# serv_open8_rohm.net
KiCad netlist of a schematic drawn in EAGLE
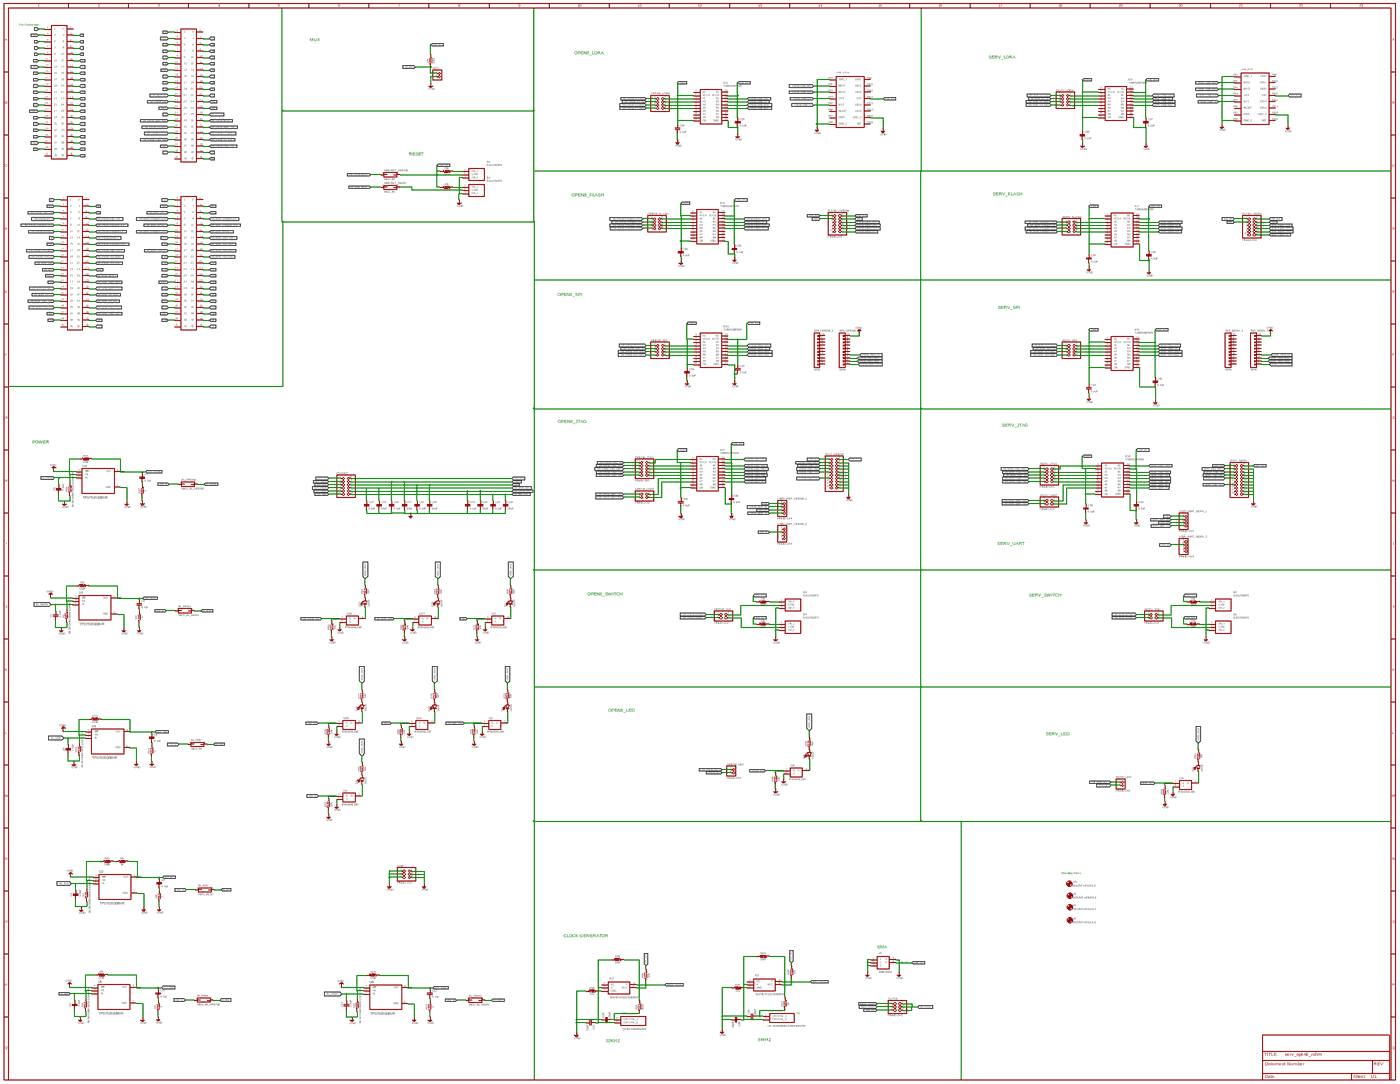
[diagram p0: schematic, sheet 1, overview]
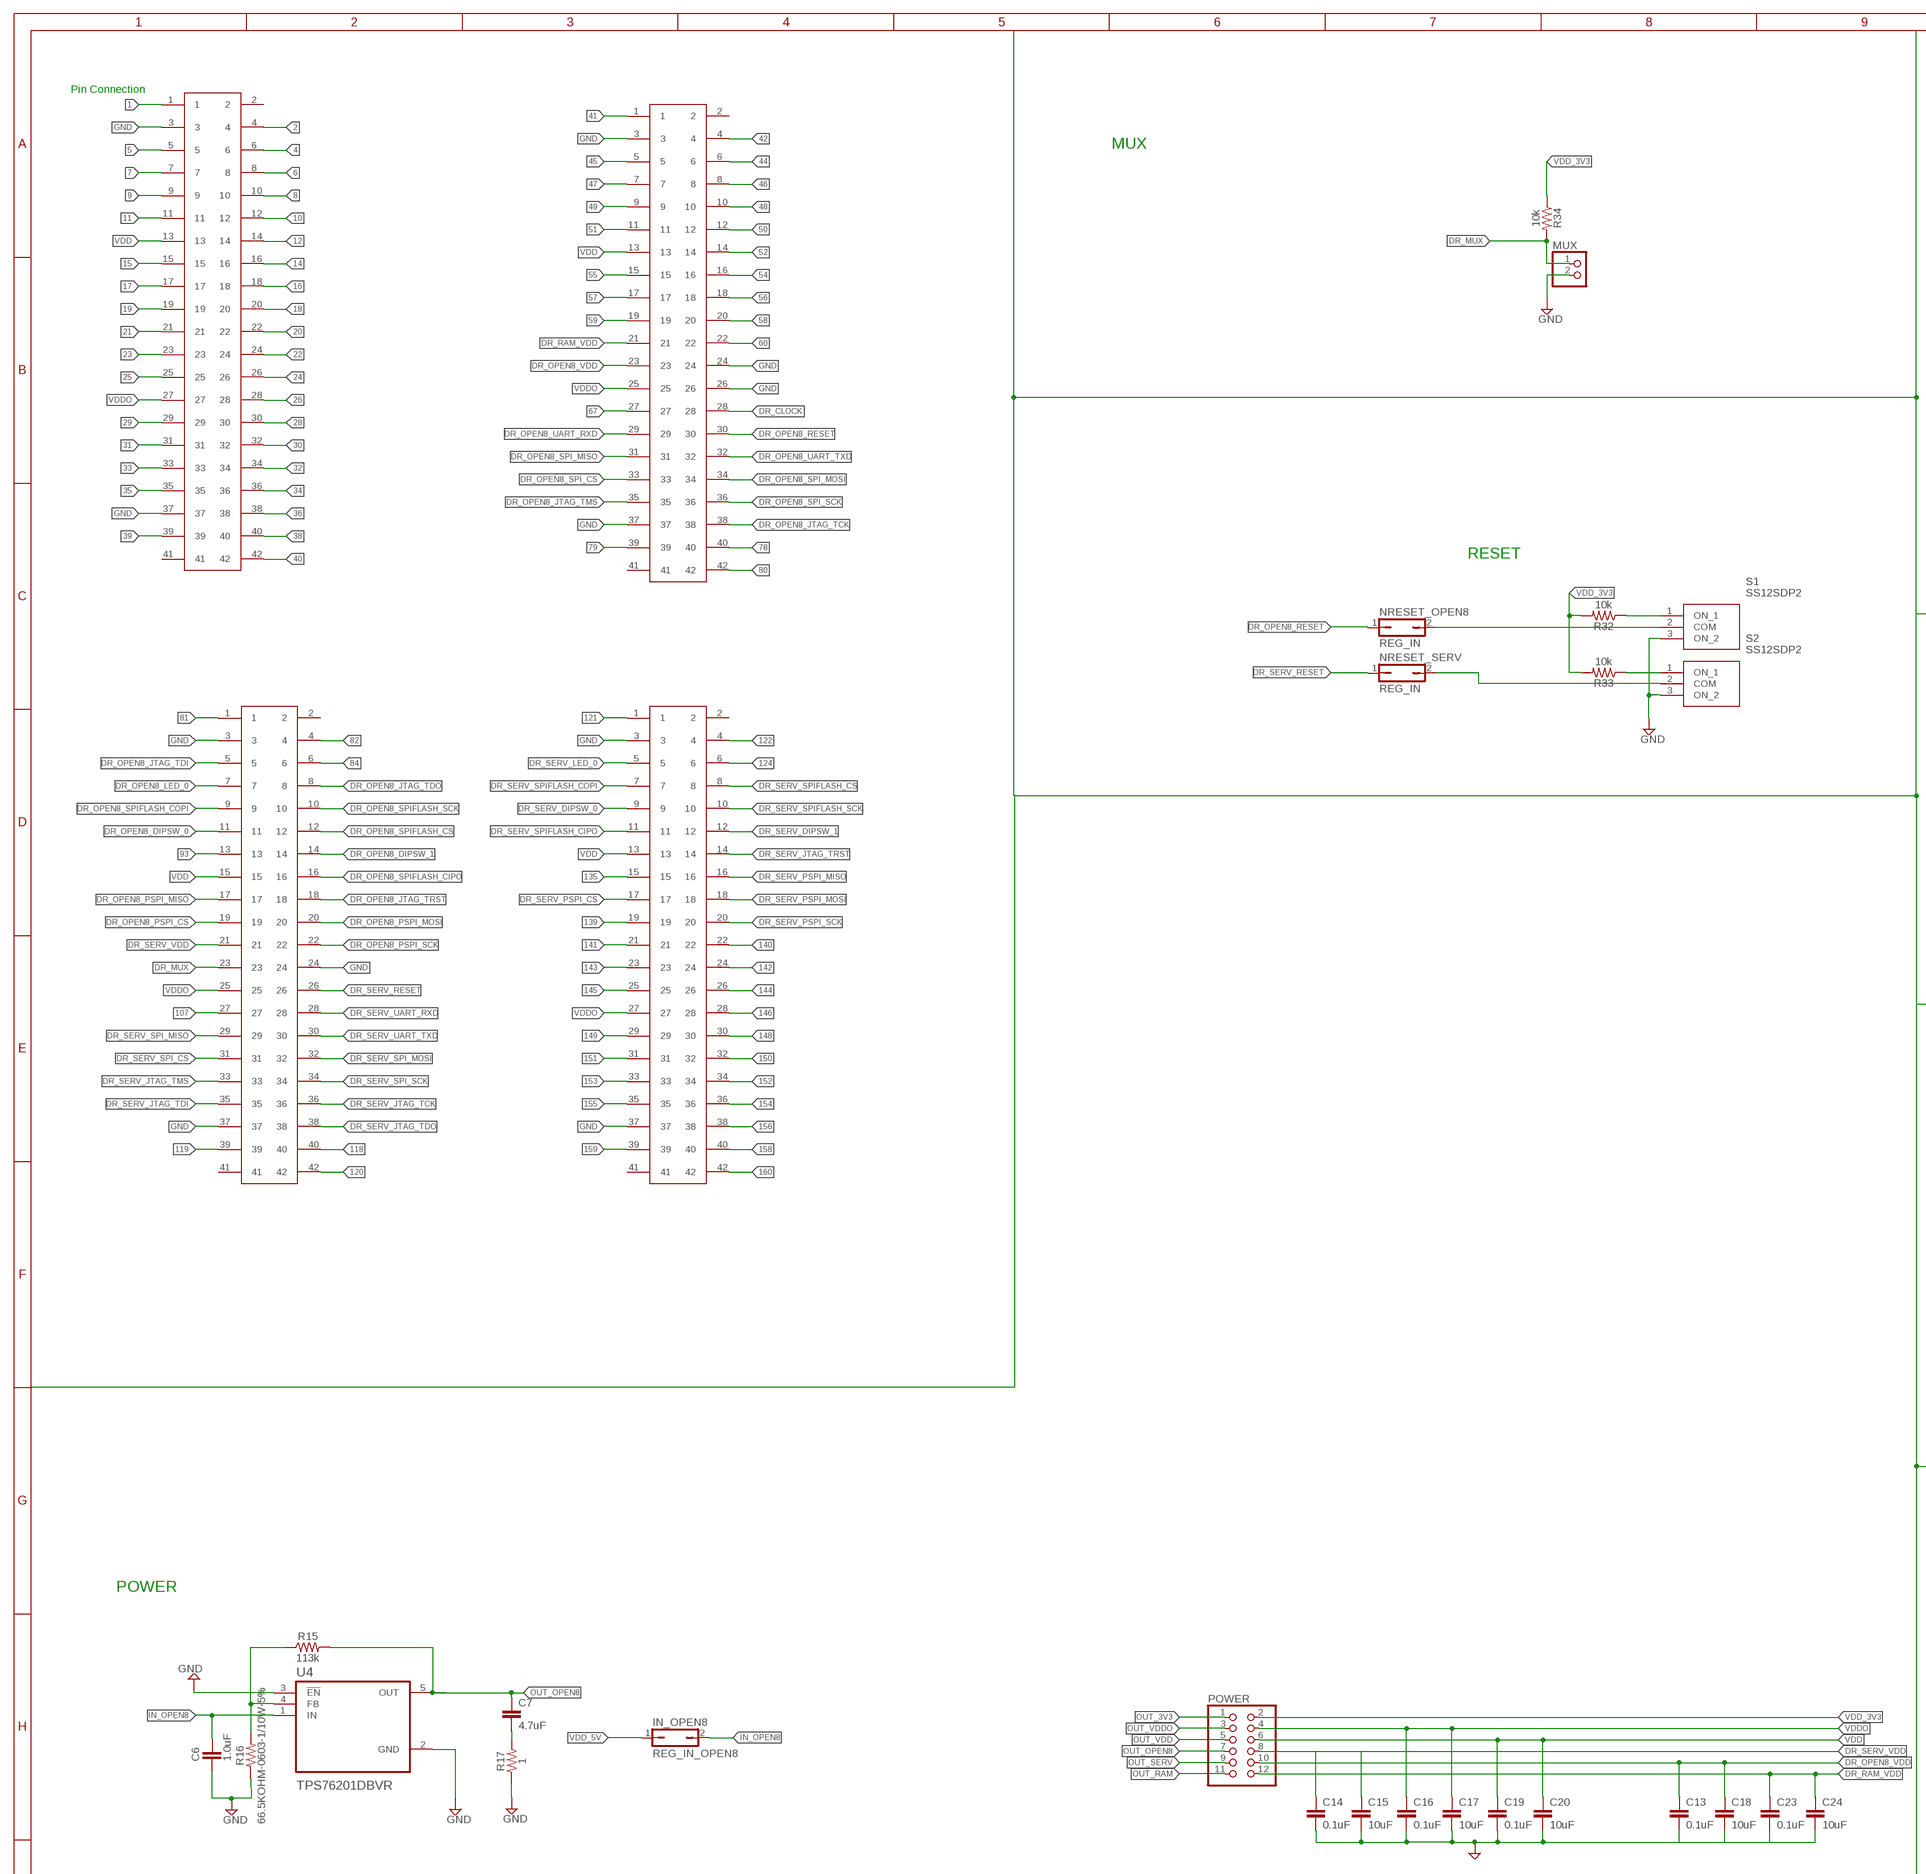
[diagram p1: schematic, sheet 1, part 1 of 6]
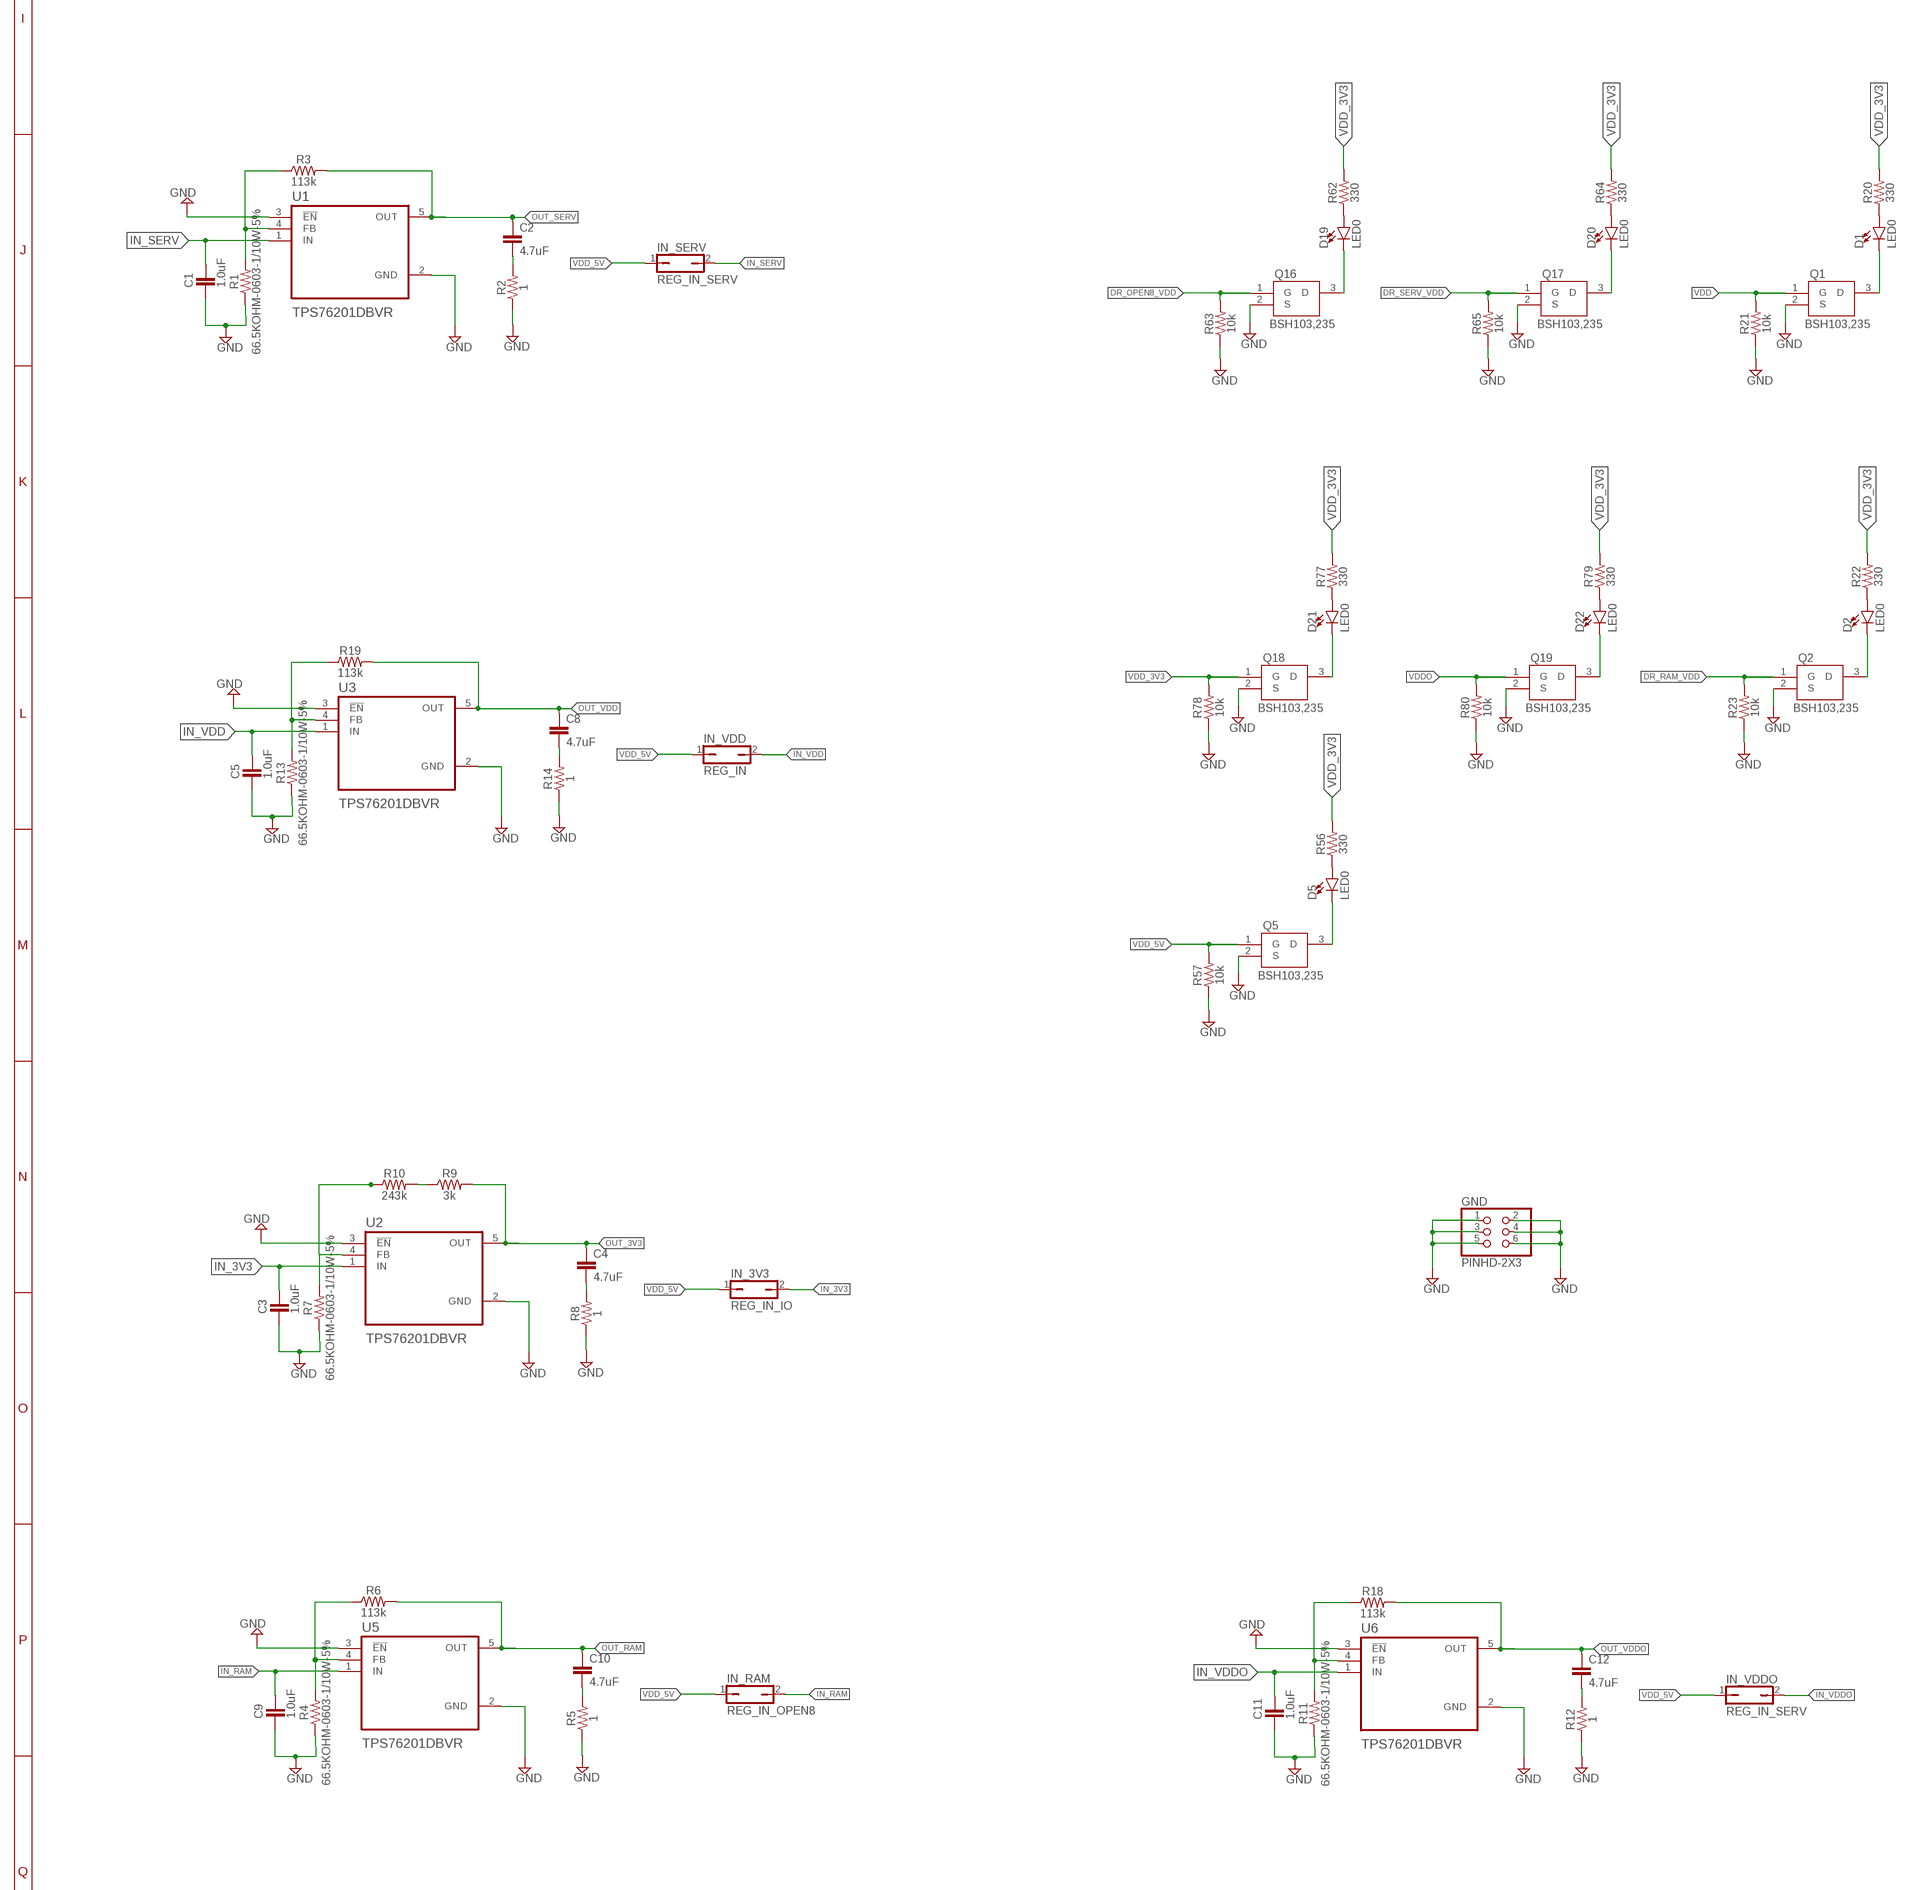
[diagram p2: schematic, sheet 1, part 2 of 6]
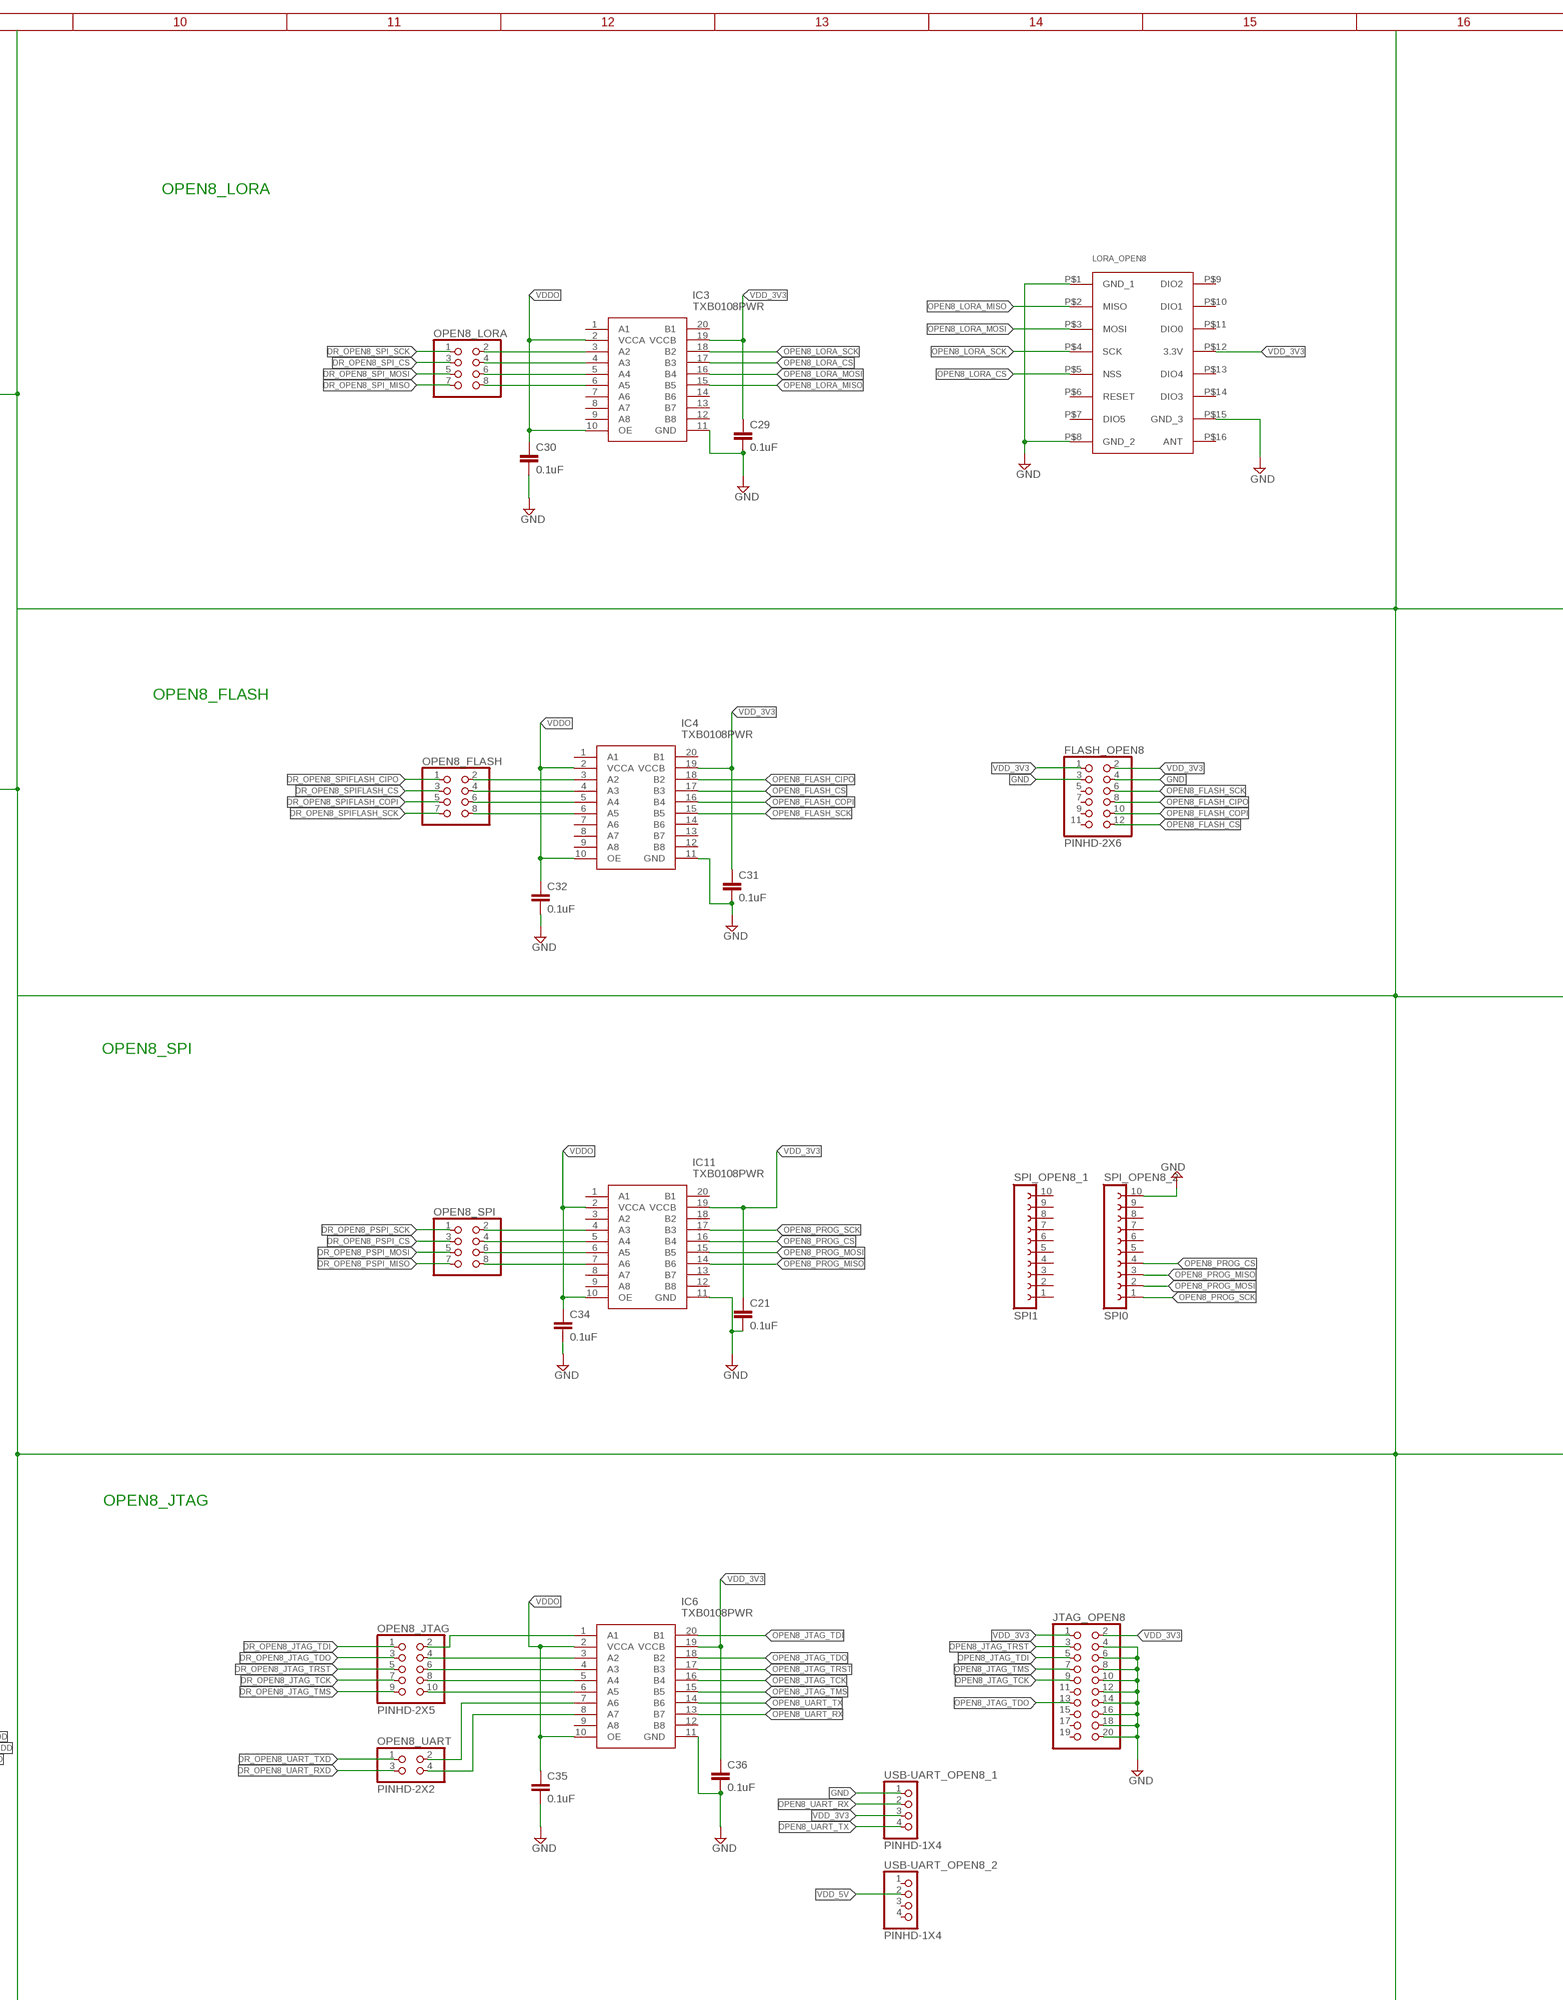
[diagram p3: schematic, sheet 1, part 3 of 6]
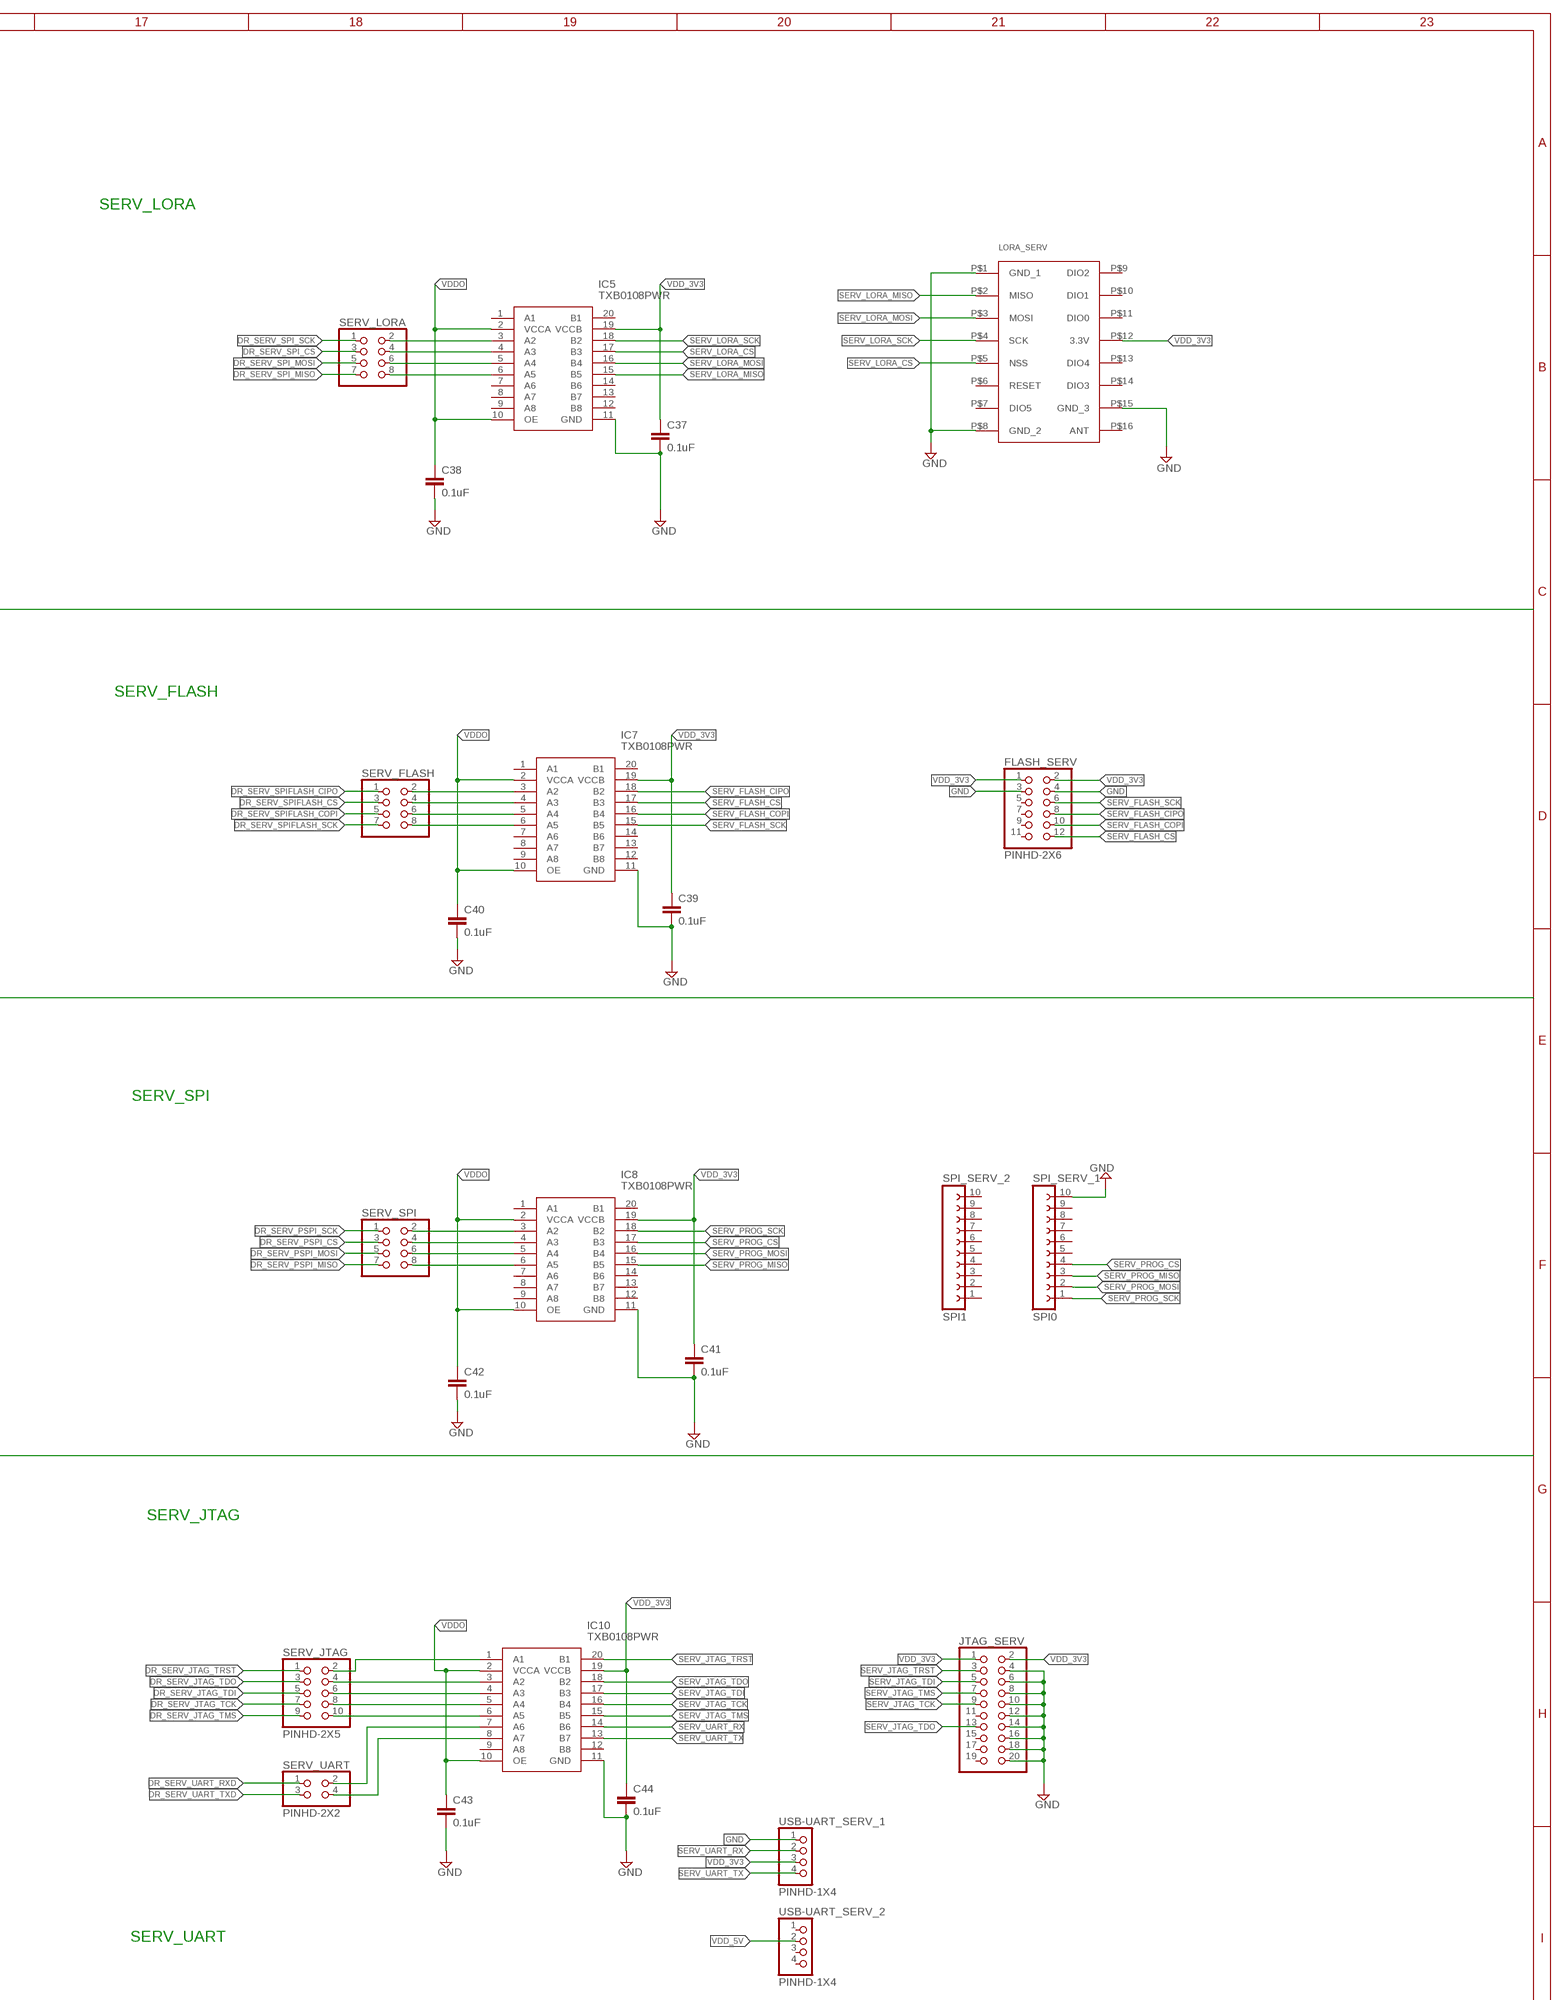
[diagram p4: schematic, sheet 1, part 4 of 6]
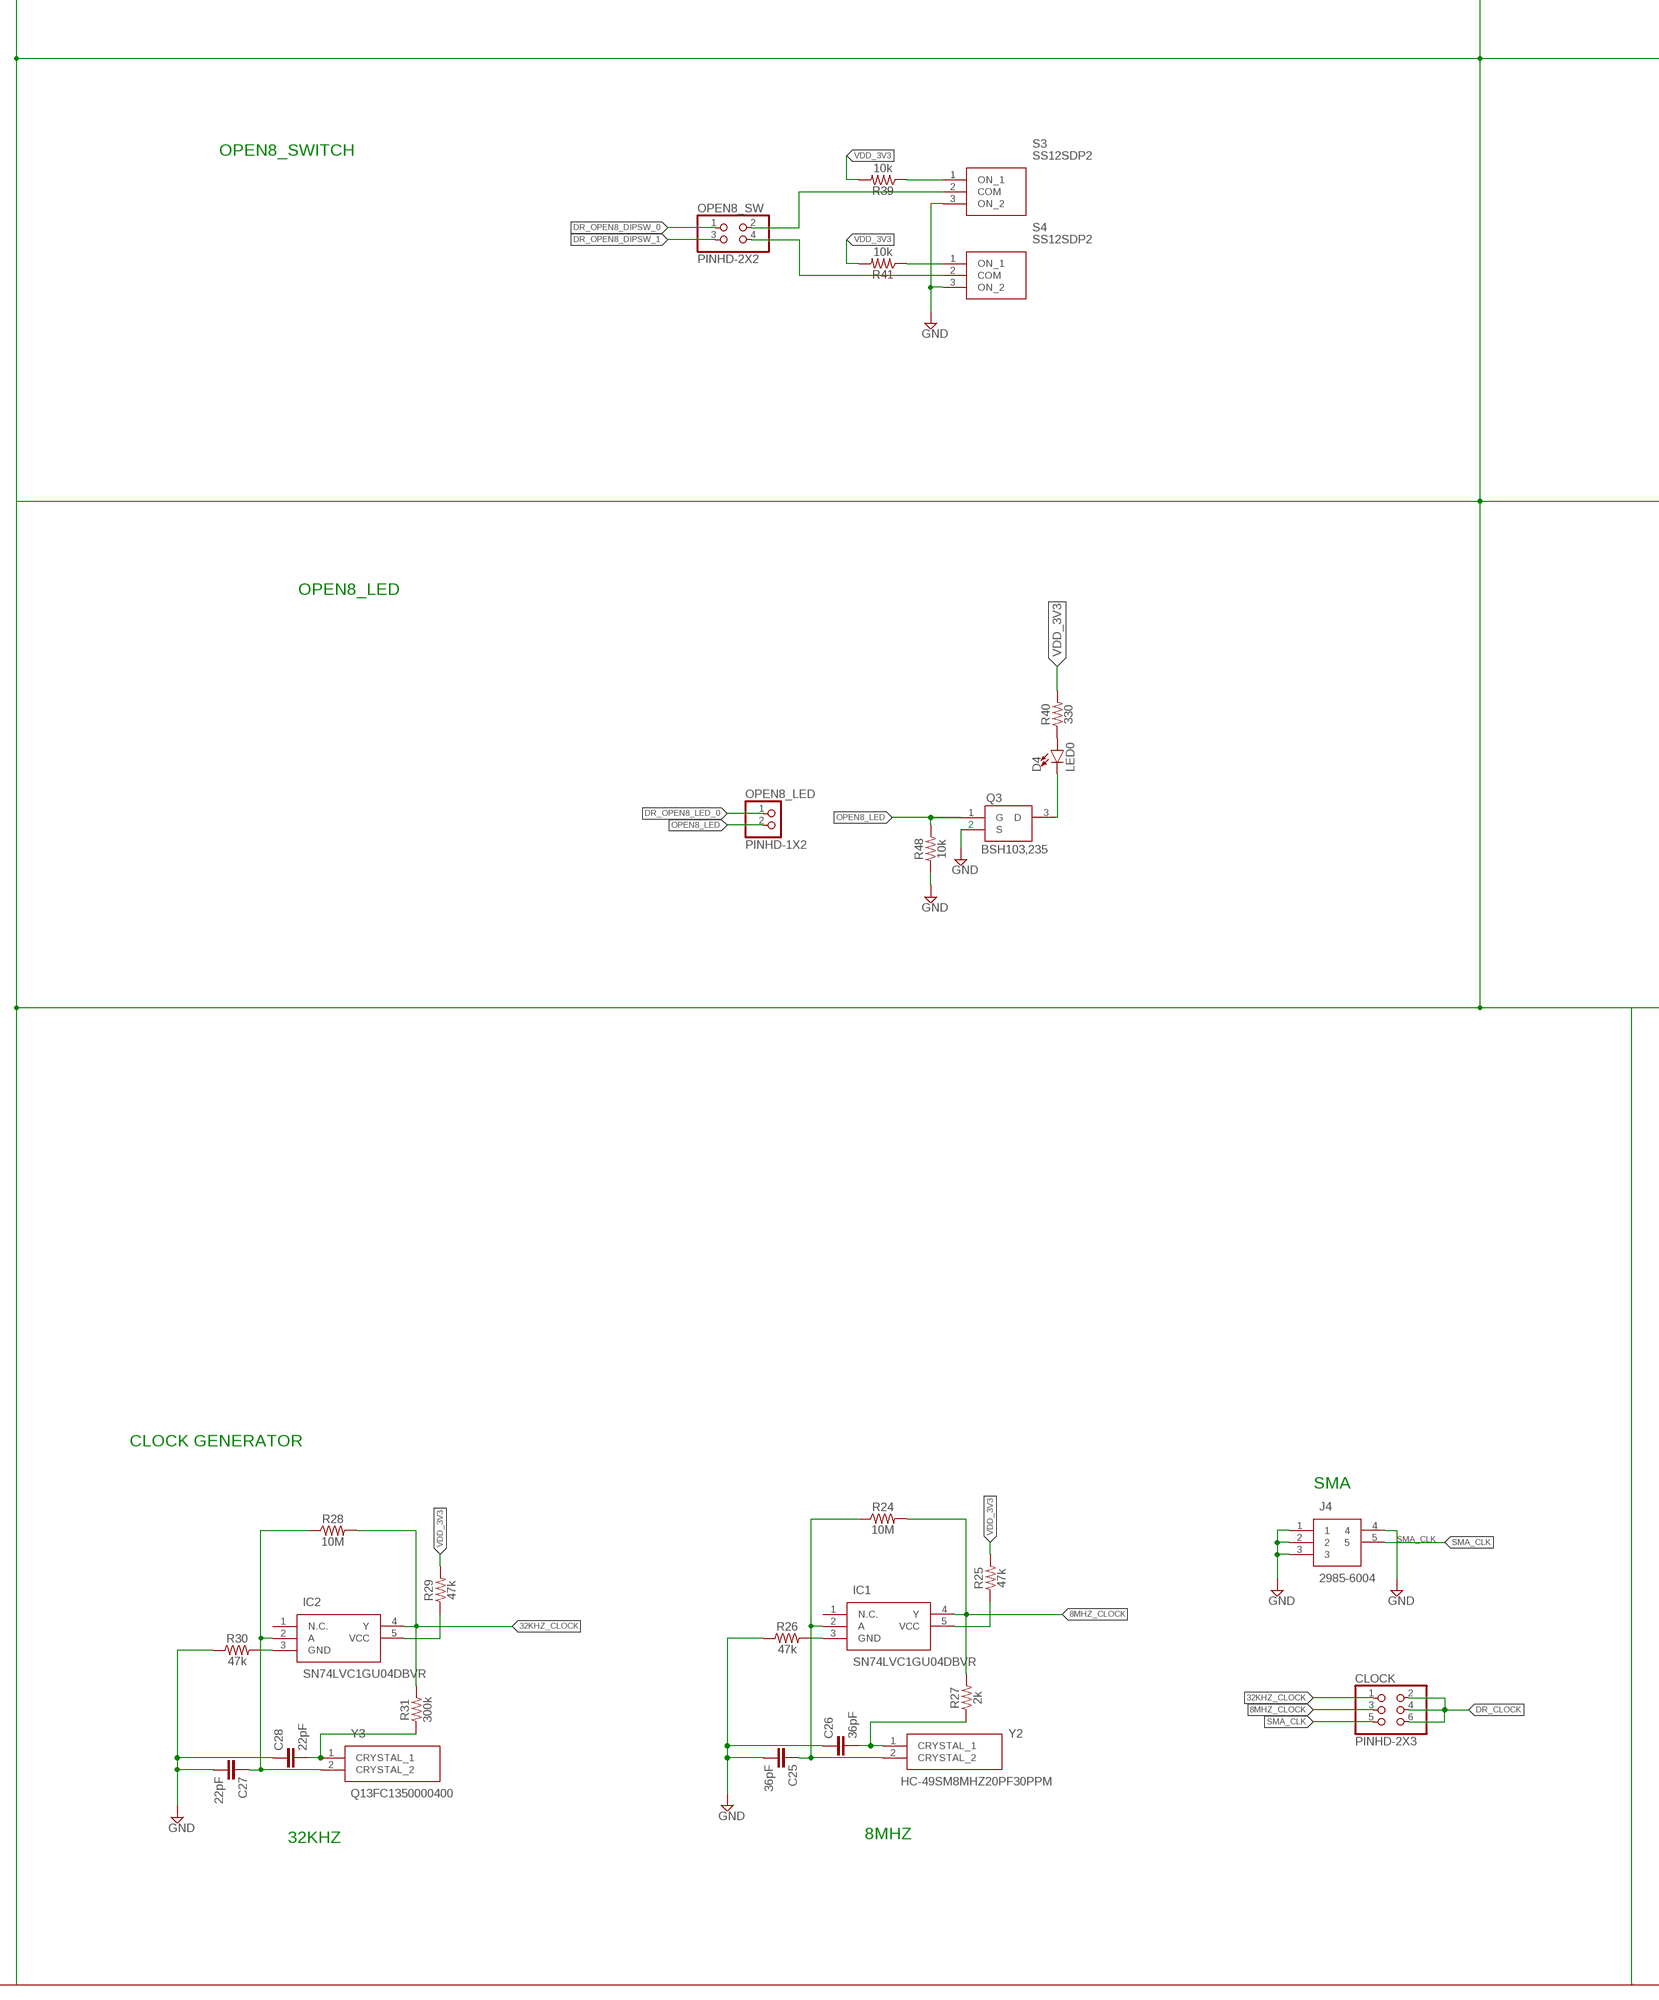
[diagram p5: schematic, sheet 1, part 5 of 6]
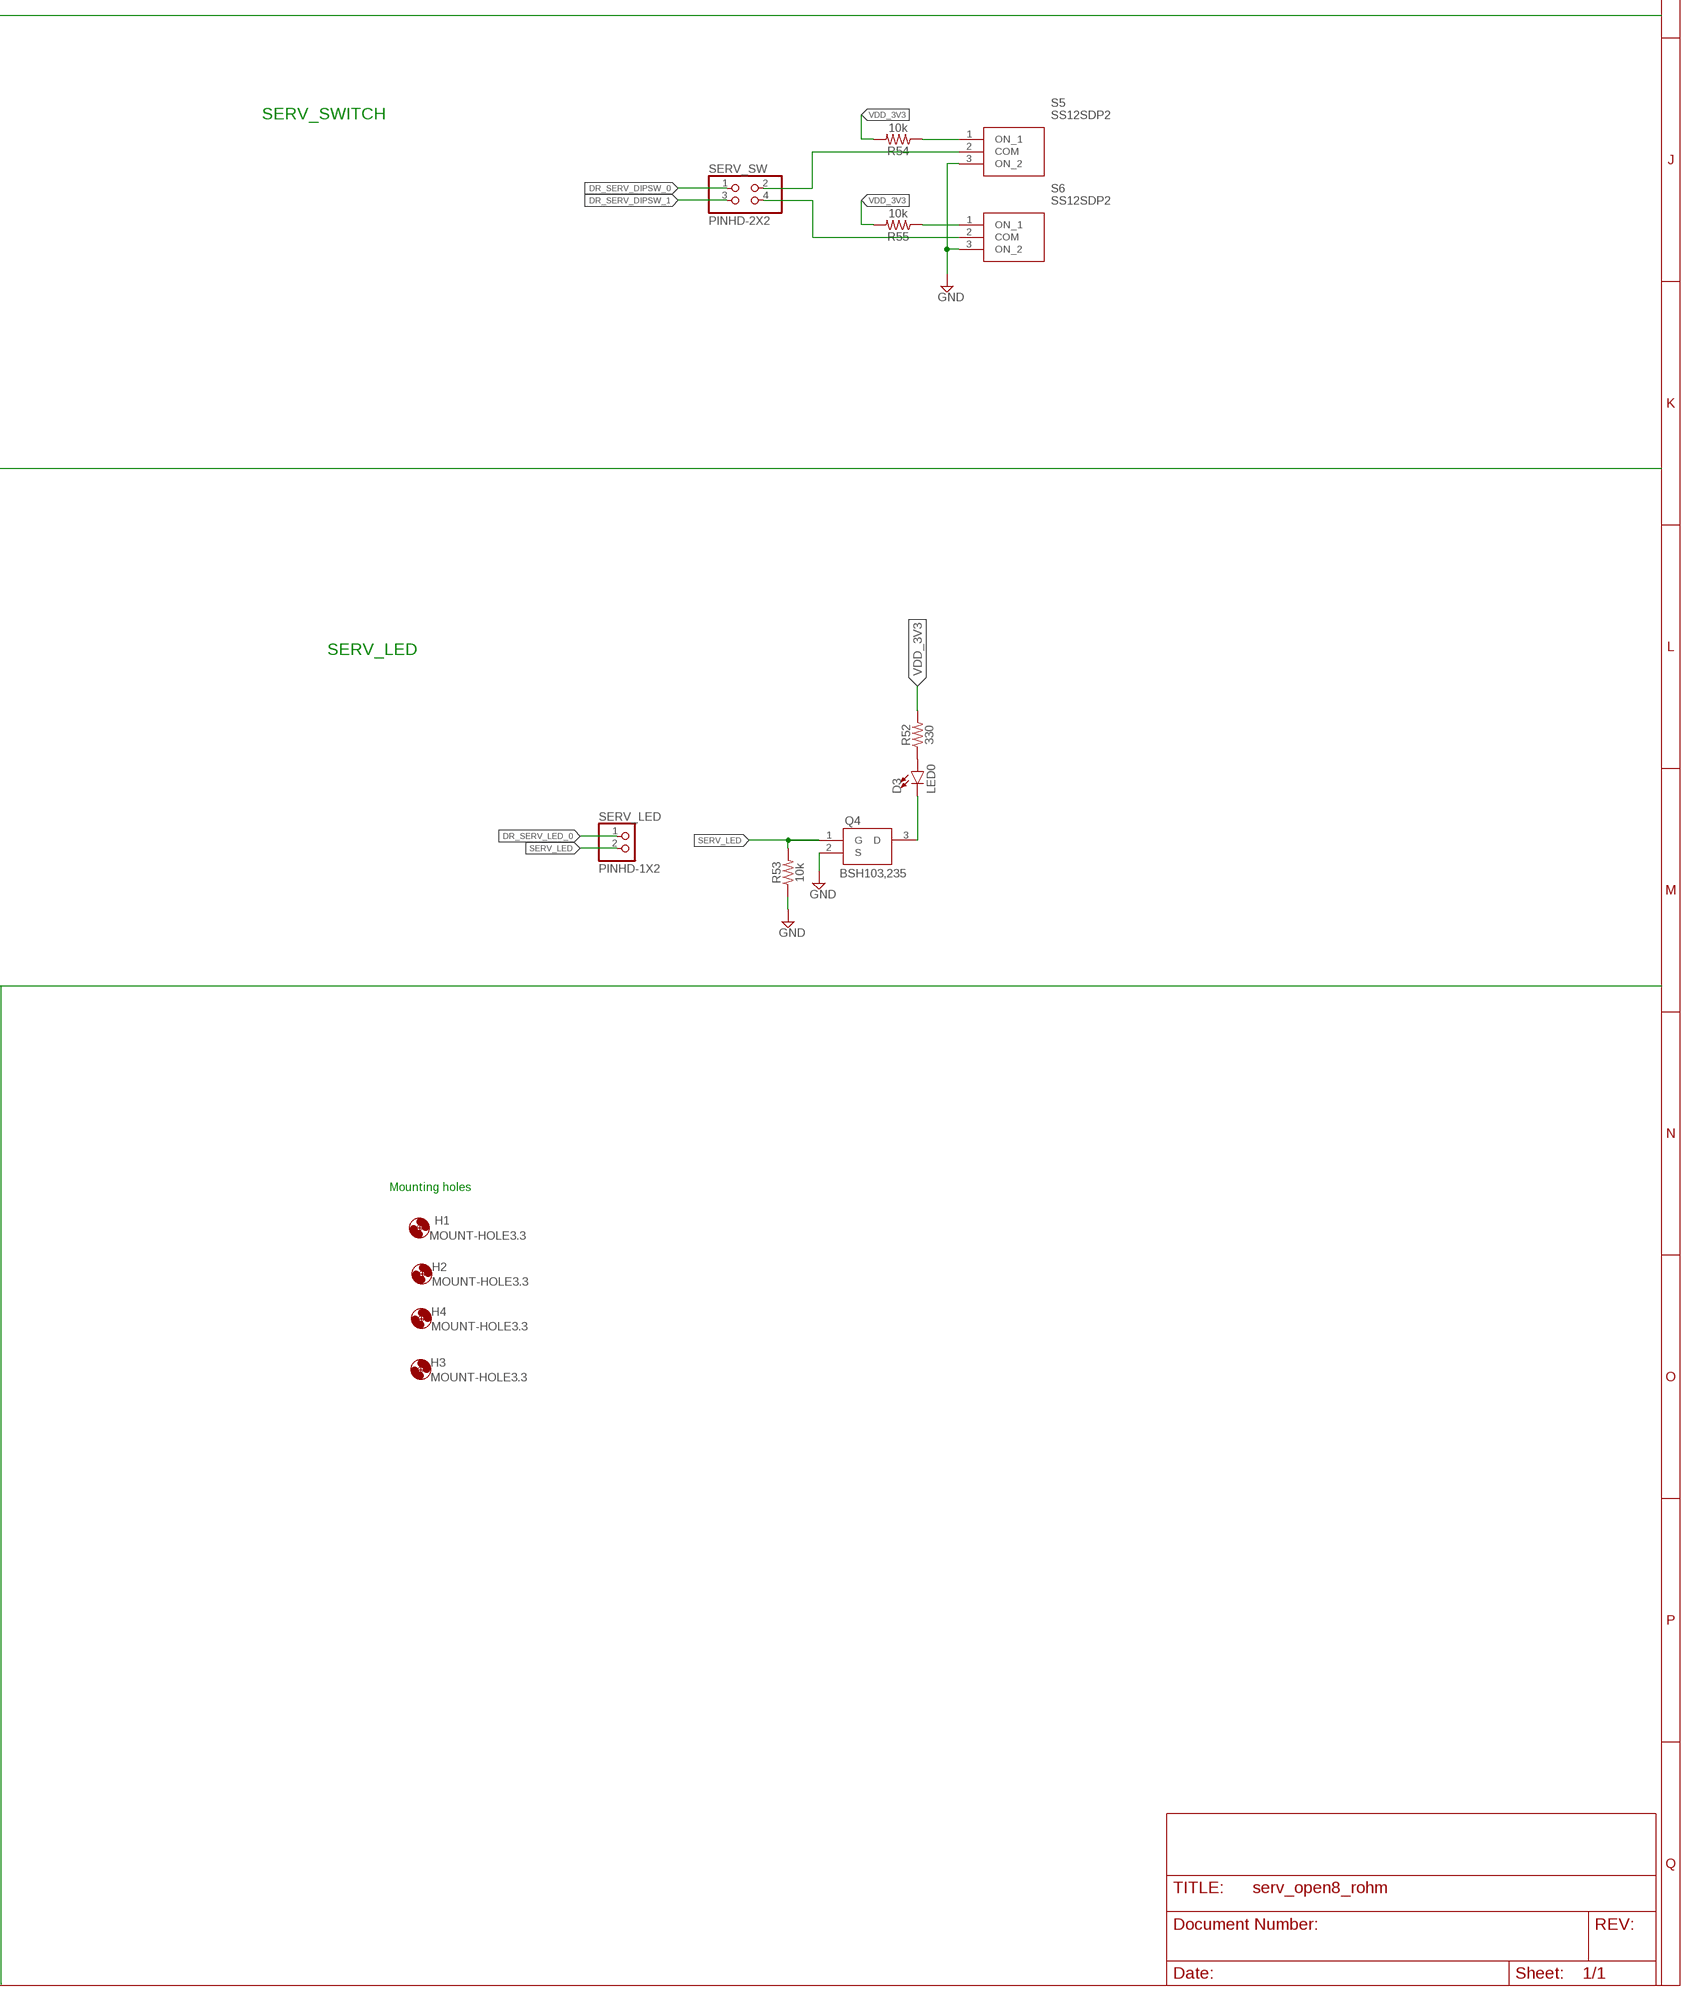
[diagram p6: schematic, sheet 1, part 6 of 6]

(export (version "E")
  (design (tool "Eeschema 10.0.6"))
  (components
    (comp (ref "C1")
      (value "1.0uF")
      (footprint "eagle-import:0603")
      (libsource (lib "eagle-import") (part "1.0UF-0603-16V-10%"))
    )
    (comp (ref "C2")
      (value "4.7uF")
      (footprint "eagle-import:0603")
      (libsource (lib "eagle-import") (part "4.7UF0603"))
    )
    (comp (ref "C3")
      (value "1.0uF")
      (footprint "eagle-import:0603")
      (libsource (lib "eagle-import") (part "1.0UF-0603-16V-10%"))
    )
    (comp (ref "C4")
      (value "4.7uF")
      (footprint "eagle-import:0603")
      (libsource (lib "eagle-import") (part "4.7UF0603"))
    )
    (comp (ref "C5")
      (value "1.0uF")
      (footprint "eagle-import:0603")
      (libsource (lib "eagle-import") (part "1.0UF-0603-16V-10%"))
    )
    (comp (ref "C6")
      (value "1.0uF")
      (footprint "eagle-import:0603")
      (libsource (lib "eagle-import") (part "1.0UF-0603-16V-10%"))
    )
    (comp (ref "C7")
      (value "4.7uF")
      (footprint "eagle-import:0603")
      (libsource (lib "eagle-import") (part "4.7UF0603"))
    )
    (comp (ref "C8")
      (value "4.7uF")
      (footprint "eagle-import:0603")
      (libsource (lib "eagle-import") (part "4.7UF0603"))
    )
    (comp (ref "C9")
      (value "1.0uF")
      (footprint "eagle-import:0603")
      (libsource (lib "eagle-import") (part "1.0UF-0603-16V-10%"))
    )
    (comp (ref "C10")
      (value "4.7uF")
      (footprint "eagle-import:0603")
      (libsource (lib "eagle-import") (part "4.7UF0603"))
    )
    (comp (ref "C11")
      (value "1.0uF")
      (footprint "eagle-import:0603")
      (libsource (lib "eagle-import") (part "1.0UF-0603-16V-10%"))
    )
    (comp (ref "C12")
      (value "4.7uF")
      (footprint "eagle-import:0603")
      (libsource (lib "eagle-import") (part "4.7UF0603"))
    )
    (comp (ref "C13")
      (value "0.1uF")
      (footprint "eagle-import:0603")
      (libsource (lib "eagle-import") (part "0.1UF-0603-25V-5%"))
    )
    (comp (ref "C14")
      (value "0.1uF")
      (footprint "eagle-import:0603")
      (libsource (lib "eagle-import") (part "0.1UF-0603-25V-5%"))
    )
    (comp (ref "C15")
      (value "10uF")
      (footprint "eagle-import:0603")
      (libsource (lib "eagle-import") (part "10UF-0603-6.3V-20%"))
    )
    (comp (ref "C16")
      (value "0.1uF")
      (footprint "eagle-import:0603")
      (libsource (lib "eagle-import") (part "0.1UF-0603-25V-5%"))
    )
    (comp (ref "C17")
      (value "10uF")
      (footprint "eagle-import:0603")
      (libsource (lib "eagle-import") (part "10UF-0603-6.3V-20%"))
    )
    (comp (ref "C18")
      (value "10uF")
      (footprint "eagle-import:0603")
      (libsource (lib "eagle-import") (part "10UF-0603-6.3V-20%"))
    )
    (comp (ref "C19")
      (value "0.1uF")
      (footprint "eagle-import:0603")
      (libsource (lib "eagle-import") (part "0.1UF-0603-25V-5%"))
    )
    (comp (ref "C20")
      (value "10uF")
      (footprint "eagle-import:0603")
      (libsource (lib "eagle-import") (part "10UF-0603-6.3V-20%"))
    )
    (comp (ref "C21")
      (value "0.1uF")
      (footprint "eagle-import:0603")
      (libsource (lib "eagle-import") (part "0.1UF-0603-25V-5%"))
    )
    (comp (ref "C23")
      (value "0.1uF")
      (footprint "eagle-import:0603")
      (libsource (lib "eagle-import") (part "0.1UF-0603-25V-5%"))
    )
    (comp (ref "C24")
      (value "10uF")
      (footprint "eagle-import:0603")
      (libsource (lib "eagle-import") (part "10UF-0603-6.3V-20%"))
    )
    (comp (ref "C25")
      (value "36pF")
      (footprint "eagle-import:0603")
      (libsource (lib "eagle-import") (part "22PF-0603-50V-5%"))
    )
    (comp (ref "C26")
      (value "36pF")
      (footprint "eagle-import:0603")
      (libsource (lib "eagle-import") (part "22PF-0603-50V-5%"))
    )
    (comp (ref "C27")
      (value "22pF")
      (footprint "eagle-import:0603")
      (libsource (lib "eagle-import") (part "22PF-0603-50V-5%"))
    )
    (comp (ref "C28")
      (value "22pF")
      (footprint "eagle-import:0603")
      (libsource (lib "eagle-import") (part "22PF-0603-50V-5%"))
    )
    (comp (ref "C29")
      (value "0.1uF")
      (footprint "eagle-import:0603")
      (libsource (lib "eagle-import") (part "0.1UF-0603-25V-5%"))
    )
    (comp (ref "C30")
      (value "0.1uF")
      (footprint "eagle-import:0603")
      (libsource (lib "eagle-import") (part "0.1UF-0603-25V-5%"))
    )
    (comp (ref "C31")
      (value "0.1uF")
      (footprint "eagle-import:0603")
      (libsource (lib "eagle-import") (part "0.1UF-0603-25V-5%"))
    )
    (comp (ref "C32")
      (value "0.1uF")
      (footprint "eagle-import:0603")
      (libsource (lib "eagle-import") (part "0.1UF-0603-25V-5%"))
    )
    (comp (ref "C34")
      (value "0.1uF")
      (footprint "eagle-import:0603")
      (libsource (lib "eagle-import") (part "0.1UF-0603-25V-5%"))
    )
    (comp (ref "C35")
      (value "0.1uF")
      (footprint "eagle-import:0603")
      (libsource (lib "eagle-import") (part "0.1UF-0603-25V-5%"))
    )
    (comp (ref "C36")
      (value "0.1uF")
      (footprint "eagle-import:0603")
      (libsource (lib "eagle-import") (part "0.1UF-0603-25V-5%"))
    )
    (comp (ref "C37")
      (value "0.1uF")
      (footprint "eagle-import:0603")
      (libsource (lib "eagle-import") (part "0.1UF-0603-25V-5%"))
    )
    (comp (ref "C38")
      (value "0.1uF")
      (footprint "eagle-import:0603")
      (libsource (lib "eagle-import") (part "0.1UF-0603-25V-5%"))
    )
    (comp (ref "C39")
      (value "0.1uF")
      (footprint "eagle-import:0603")
      (libsource (lib "eagle-import") (part "0.1UF-0603-25V-5%"))
    )
    (comp (ref "C40")
      (value "0.1uF")
      (footprint "eagle-import:0603")
      (libsource (lib "eagle-import") (part "0.1UF-0603-25V-5%"))
    )
    (comp (ref "C41")
      (value "0.1uF")
      (footprint "eagle-import:0603")
      (libsource (lib "eagle-import") (part "0.1UF-0603-25V-5%"))
    )
    (comp (ref "C42")
      (value "0.1uF")
      (footprint "eagle-import:0603")
      (libsource (lib "eagle-import") (part "0.1UF-0603-25V-5%"))
    )
    (comp (ref "C43")
      (value "0.1uF")
      (footprint "eagle-import:0603")
      (libsource (lib "eagle-import") (part "0.1UF-0603-25V-5%"))
    )
    (comp (ref "C44")
      (value "0.1uF")
      (footprint "eagle-import:0603")
      (libsource (lib "eagle-import") (part "0.1UF-0603-25V-5%"))
    )
    (comp (ref "CLOCK")
      (value "PINHD-2X3")
      (footprint "eagle-import:2X03")
      (libsource (lib "eagle-import") (part "PINHD-2X3"))
    )
    (comp (ref "D1")
      (value "LED0")
      (footprint "eagle-import:LED-0603")
      (libsource (lib "eagle-import") (part "LED0603"))
    )
    (comp (ref "D2")
      (value "LED0")
      (footprint "eagle-import:LED-0603")
      (libsource (lib "eagle-import") (part "LED0603"))
    )
    (comp (ref "D3")
      (value "LED0")
      (footprint "eagle-import:LED-0603")
      (libsource (lib "eagle-import") (part "LED0603"))
    )
    (comp (ref "D4")
      (value "LED0")
      (footprint "eagle-import:LED-0603")
      (libsource (lib "eagle-import") (part "LED0603"))
    )
    (comp (ref "D5")
      (value "LED0")
      (footprint "eagle-import:LED-0603")
      (libsource (lib "eagle-import") (part "LED0603"))
    )
    (comp (ref "D19")
      (value "LED0")
      (footprint "eagle-import:LED-0603")
      (libsource (lib "eagle-import") (part "LED0603"))
    )
    (comp (ref "D20")
      (value "LED0")
      (footprint "eagle-import:LED-0603")
      (libsource (lib "eagle-import") (part "LED0603"))
    )
    (comp (ref "D21")
      (value "LED0")
      (footprint "eagle-import:LED-0603")
      (libsource (lib "eagle-import") (part "LED0603"))
    )
    (comp (ref "D22")
      (value "LED0")
      (footprint "eagle-import:LED-0603")
      (libsource (lib "eagle-import") (part "LED0603"))
    )
    (comp (ref "FLASH_OPEN8")
      (value "PINHD-2X6")
      (footprint "eagle-import:2X06")
      (libsource (lib "eagle-import") (part "PINHD-2X6"))
    )
    (comp (ref "FLASH_SERV")
      (value "PINHD-2X6")
      (footprint "eagle-import:2X06")
      (libsource (lib "eagle-import") (part "PINHD-2X6"))
    )
    (comp (ref "GND")
      (value "PINHD-2X3")
      (footprint "eagle-import:2X03")
      (libsource (lib "eagle-import") (part "PINHD-2X3"))
    )
    (comp (ref "H1")
      (value "MOUNT-HOLE3.3")
      (footprint "eagle-import:3,3")
      (libsource (lib "eagle-import") (part "MOUNT-HOLE3.3"))
    )
    (comp (ref "H2")
      (value "MOUNT-HOLE3.3")
      (footprint "eagle-import:3,3")
      (libsource (lib "eagle-import") (part "MOUNT-HOLE3.3"))
    )
    (comp (ref "H3")
      (value "MOUNT-HOLE3.3")
      (footprint "eagle-import:3,3")
      (libsource (lib "eagle-import") (part "MOUNT-HOLE3.3"))
    )
    (comp (ref "H4")
      (value "MOUNT-HOLE3.3")
      (footprint "eagle-import:3,3")
      (libsource (lib "eagle-import") (part "MOUNT-HOLE3.3"))
    )
    (comp (ref "IC1")
      (value "SN74LVC1GU04DBVR")
      (footprint "eagle-import:SOT95P280X145-5N")
      (fields (field (name "MOUSER_PART_NUMBER") "595-SN74LVC1GU04DBVR"))
      (libsource (lib "eagle-import") (part "SN74LVC1GU04DBVR"))
    )
    (comp (ref "IC2")
      (value "SN74LVC1GU04DBVR")
      (footprint "eagle-import:SOT95P280X145-5N")
      (fields (field (name "MOUSER_PART_NUMBER") "595-SN74LVC1GU04DBVR"))
      (libsource (lib "eagle-import") (part "SN74LVC1GU04DBVR"))
    )
    (comp (ref "IC3")
      (value "TXB0108PWR")
      (footprint "eagle-import:SOP65P640X120-20N")
      (fields (field (name "MOUSER_PART_NUMBER") "595-TXB0108PWR"))
      (libsource (lib "eagle-import") (part "TXB0108PWR"))
    )
    (comp (ref "IC4")
      (value "TXB0108PWR")
      (footprint "eagle-import:SOP65P640X120-20N")
      (fields (field (name "MOUSER_PART_NUMBER") "595-TXB0108PWR"))
      (libsource (lib "eagle-import") (part "TXB0108PWR"))
    )
    (comp (ref "IC5")
      (value "TXB0108PWR")
      (footprint "eagle-import:SOP65P640X120-20N")
      (fields (field (name "MOUSER_PART_NUMBER") "595-TXB0108PWR"))
      (libsource (lib "eagle-import") (part "TXB0108PWR"))
    )
    (comp (ref "IC6")
      (value "TXB0108PWR")
      (footprint "eagle-import:SOP65P640X120-20N")
      (fields (field (name "MOUSER_PART_NUMBER") "595-TXB0108PWR"))
      (libsource (lib "eagle-import") (part "TXB0108PWR"))
    )
    (comp (ref "IC7")
      (value "TXB0108PWR")
      (footprint "eagle-import:SOP65P640X120-20N")
      (fields (field (name "MOUSER_PART_NUMBER") "595-TXB0108PWR"))
      (libsource (lib "eagle-import") (part "TXB0108PWR"))
    )
    (comp (ref "IC8")
      (value "TXB0108PWR")
      (footprint "eagle-import:SOP65P640X120-20N")
      (fields (field (name "MOUSER_PART_NUMBER") "595-TXB0108PWR"))
      (libsource (lib "eagle-import") (part "TXB0108PWR"))
    )
    (comp (ref "IC10")
      (value "TXB0108PWR")
      (footprint "eagle-import:SOP65P640X120-20N")
      (fields (field (name "MOUSER_PART_NUMBER") "595-TXB0108PWR"))
      (libsource (lib "eagle-import") (part "TXB0108PWR"))
    )
    (comp (ref "IC11")
      (value "TXB0108PWR")
      (footprint "eagle-import:SOP65P640X120-20N")
      (fields (field (name "MOUSER_PART_NUMBER") "595-TXB0108PWR"))
      (libsource (lib "eagle-import") (part "TXB0108PWR"))
    )
    (comp (ref "IN_3V3")
      (value "REG_IN_IO")
      (footprint "eagle-import:JP1")
      (libsource (lib "eagle-import") (part "JP1Q"))
    )
    (comp (ref "IN_OPEN8")
      (value "REG_IN_OPEN8")
      (footprint "eagle-import:JP1")
      (libsource (lib "eagle-import") (part "JP1Q"))
    )
    (comp (ref "IN_RAM")
      (value "REG_IN_OPEN8")
      (footprint "eagle-import:JP1")
      (libsource (lib "eagle-import") (part "JP1Q"))
    )
    (comp (ref "IN_SERV")
      (value "REG_IN_SERV")
      (footprint "eagle-import:JP1")
      (libsource (lib "eagle-import") (part "JP1Q"))
    )
    (comp (ref "IN_VDD")
      (value "REG_IN")
      (footprint "eagle-import:JP1")
      (libsource (lib "eagle-import") (part "JP1Q"))
    )
    (comp (ref "IN_VDDO")
      (value "REG_IN_SERV")
      (footprint "eagle-import:JP1")
      (libsource (lib "eagle-import") (part "JP1Q"))
    )
    (comp (ref "J4")
      (value "2985-6004")
      (footprint "eagle-import:29856004")
      (fields (field (name "MOUSER_PART_NUMBER") "523-2985-6004"))
      (libsource (lib "eagle-import") (part "2985-6004"))
    )
    (comp (ref "JTAG_OPEN8")
      (value "PINHD-2X10")
      (footprint "eagle-import:2X10")
      (libsource (lib "eagle-import") (part "PINHD-2X10"))
    )
    (comp (ref "JTAG_SERV")
      (value "PINHD-2X10")
      (footprint "eagle-import:2X10")
      (libsource (lib "eagle-import") (part "PINHD-2X10"))
    )
    (comp (ref "LORA_OPEN8")
      (value "RFM95W-915S2")
      (footprint "eagle-import:RFM95-915S2")
      (libsource (lib "eagle-import") (part "RFM95W-915S2"))
    )
    (comp (ref "LORA_SERV")
      (value "RFM95W-915S2")
      (footprint "eagle-import:RFM95-915S2")
      (libsource (lib "eagle-import") (part "RFM95W-915S2"))
    )
    (comp (ref "MUX")
      (value "PINHD-1X2")
      (footprint "eagle-import:1X02")
      (libsource (lib "eagle-import") (part "pinhead_325_PINHD-1X2"))
    )
    (comp (ref "NRESET_OPEN8")
      (value "REG_IN")
      (footprint "eagle-import:JP1")
      (libsource (lib "eagle-import") (part "JP1Q"))
    )
    (comp (ref "NRESET_SERV")
      (value "REG_IN")
      (footprint "eagle-import:JP1")
      (libsource (lib "eagle-import") (part "JP1Q"))
    )
    (comp (ref "OPEN8_FLASH")
      (value "PINHD-2X4")
      (footprint "eagle-import:2X04")
      (libsource (lib "eagle-import") (part "PINHD-2X4"))
    )
    (comp (ref "OPEN8_JTAG")
      (value "PINHD-2X5")
      (footprint "eagle-import:2X05")
      (libsource (lib "eagle-import") (part "PINHD-2X5"))
    )
    (comp (ref "OPEN8_LED")
      (value "PINHD-1X2")
      (footprint "eagle-import:1X02")
      (libsource (lib "eagle-import") (part "PINHD-1X2"))
    )
    (comp (ref "OPEN8_LORA")
      (value "PINHD-2X4")
      (footprint "eagle-import:2X04")
      (libsource (lib "eagle-import") (part "PINHD-2X4"))
    )
    (comp (ref "OPEN8_SPI")
      (value "PINHD-2X4")
      (footprint "eagle-import:2X04")
      (libsource (lib "eagle-import") (part "PINHD-2X4"))
    )
    (comp (ref "OPEN8_SW")
      (value "PINHD-2X2")
      (footprint "eagle-import:2X02")
      (libsource (lib "eagle-import") (part "PINHD-2X2"))
    )
    (comp (ref "OPEN8_UART")
      (value "PINHD-2X2")
      (footprint "eagle-import:2X02")
      (libsource (lib "eagle-import") (part "PINHD-2X2"))
    )
    (comp (ref "POWER")
      (value "PINHD-2X6")
      (footprint "eagle-import:2X06")
      (libsource (lib "eagle-import") (part "pinhead_325_PINHD-2X6"))
    )
    (comp (ref "Q1")
      (value "BSH103,235")
      (footprint "eagle-import:SOT95P230X110-3N")
      (fields (field (name "MOUSER_PART_NUMBER") "771-BSH103235"))
      (libsource (lib "eagle-import") (part "BSH103,235"))
    )
    (comp (ref "Q2")
      (value "BSH103,235")
      (footprint "eagle-import:SOT95P230X110-3N")
      (fields (field (name "MOUSER_PART_NUMBER") "771-BSH103235"))
      (libsource (lib "eagle-import") (part "BSH103,235"))
    )
    (comp (ref "Q3")
      (value "BSH103,235")
      (footprint "eagle-import:SOT95P230X110-3N")
      (fields (field (name "MOUSER_PART_NUMBER") "771-BSH103235"))
      (libsource (lib "eagle-import") (part "BSH103,235"))
    )
    (comp (ref "Q4")
      (value "BSH103,235")
      (footprint "eagle-import:SOT95P230X110-3N")
      (fields (field (name "MOUSER_PART_NUMBER") "771-BSH103235"))
      (libsource (lib "eagle-import") (part "BSH103,235"))
    )
    (comp (ref "Q5")
      (value "BSH103,235")
      (footprint "eagle-import:SOT95P230X110-3N")
      (fields (field (name "MOUSER_PART_NUMBER") "771-BSH103235"))
      (libsource (lib "eagle-import") (part "BSH103,235"))
    )
    (comp (ref "Q16")
      (value "BSH103,235")
      (footprint "eagle-import:SOT95P230X110-3N")
      (fields (field (name "MOUSER_PART_NUMBER") "771-BSH103235"))
      (libsource (lib "eagle-import") (part "BSH103,235"))
    )
    (comp (ref "Q17")
      (value "BSH103,235")
      (footprint "eagle-import:SOT95P230X110-3N")
      (fields (field (name "MOUSER_PART_NUMBER") "771-BSH103235"))
      (libsource (lib "eagle-import") (part "BSH103,235"))
    )
    (comp (ref "Q18")
      (value "BSH103,235")
      (footprint "eagle-import:SOT95P230X110-3N")
      (fields (field (name "MOUSER_PART_NUMBER") "771-BSH103235"))
      (libsource (lib "eagle-import") (part "BSH103,235"))
    )
    (comp (ref "Q19")
      (value "BSH103,235")
      (footprint "eagle-import:SOT95P230X110-3N")
      (fields (field (name "MOUSER_PART_NUMBER") "771-BSH103235"))
      (libsource (lib "eagle-import") (part "BSH103,235"))
    )
    (comp (ref "R1")
      (value "66.5KOHM-0603-1/10W-5%")
      (footprint "eagle-import:0603")
      (libsource (lib "eagle-import") (part "62KOHM-0603-1/10W-5%"))
    )
    (comp (ref "R2")
      (value "1")
      (footprint "eagle-import:0603")
      (libsource (lib "eagle-import") (part "1OHM-0603-1/10W-1%"))
    )
    (comp (ref "R3")
      (value "113k")
      (footprint "eagle-import:0603")
      (libsource (lib "eagle-import") (part "43KOHM-0603-1/10W-1%"))
    )
    (comp (ref "R4")
      (value "66.5KOHM-0603-1/10W-5%")
      (footprint "eagle-import:0603")
      (libsource (lib "eagle-import") (part "62KOHM-0603-1/10W-5%"))
    )
    (comp (ref "R5")
      (value "1")
      (footprint "eagle-import:0603")
      (libsource (lib "eagle-import") (part "1OHM-0603-1/10W-1%"))
    )
    (comp (ref "R6")
      (value "113k")
      (footprint "eagle-import:0603")
      (libsource (lib "eagle-import") (part "43KOHM-0603-1/10W-1%"))
    )
    (comp (ref "R7")
      (value "66.5KOHM-0603-1/10W-5%")
      (footprint "eagle-import:0603")
      (libsource (lib "eagle-import") (part "62KOHM-0603-1/10W-5%"))
    )
    (comp (ref "R8")
      (value "1")
      (footprint "eagle-import:0603")
      (libsource (lib "eagle-import") (part "1OHM-0603-1/10W-1%"))
    )
    (comp (ref "R9")
      (value "3k")
      (footprint "eagle-import:0603")
      (libsource (lib "eagle-import") (part "26.7KOHM0603-1/10W-1%"))
    )
    (comp (ref "R10")
      (value "243k")
      (footprint "eagle-import:0603")
      (libsource (lib "eagle-import") (part "220KOHM-0603-1/10W-1%"))
    )
    (comp (ref "R11")
      (value "66.5KOHM-0603-1/10W-5%")
      (footprint "eagle-import:0603")
      (libsource (lib "eagle-import") (part "62KOHM-0603-1/10W-5%"))
    )
    (comp (ref "R12")
      (value "1")
      (footprint "eagle-import:0603")
      (libsource (lib "eagle-import") (part "1OHM-0603-1/10W-1%"))
    )
    (comp (ref "R13")
      (value "66.5KOHM-0603-1/10W-5%")
      (footprint "eagle-import:0603")
      (libsource (lib "eagle-import") (part "62KOHM-0603-1/10W-5%"))
    )
    (comp (ref "R14")
      (value "1")
      (footprint "eagle-import:0603")
      (libsource (lib "eagle-import") (part "1OHM-0603-1/10W-1%"))
    )
    (comp (ref "R15")
      (value "113k")
      (footprint "eagle-import:0603")
      (libsource (lib "eagle-import") (part "43KOHM-0603-1/10W-1%"))
    )
    (comp (ref "R16")
      (value "66.5KOHM-0603-1/10W-5%")
      (footprint "eagle-import:0603")
      (libsource (lib "eagle-import") (part "62KOHM-0603-1/10W-5%"))
    )
    (comp (ref "R17")
      (value "1")
      (footprint "eagle-import:0603")
      (libsource (lib "eagle-import") (part "1OHM-0603-1/10W-1%"))
    )
    (comp (ref "R18")
      (value "113k")
      (footprint "eagle-import:0603")
      (libsource (lib "eagle-import") (part "43KOHM-0603-1/10W-1%"))
    )
    (comp (ref "R19")
      (value "113k")
      (footprint "eagle-import:0603")
      (libsource (lib "eagle-import") (part "43KOHM-0603-1/10W-1%"))
    )
    (comp (ref "R20")
      (value "330")
      (footprint "eagle-import:0603")
      (libsource (lib "eagle-import") (part "330OHM-0603-1/10W-1%"))
    )
    (comp (ref "R21")
      (value "10k")
      (footprint "eagle-import:0603")
      (libsource (lib "eagle-import") (part "10KOHM-0603-1/10W-1%"))
    )
    (comp (ref "R22")
      (value "330")
      (footprint "eagle-import:0603")
      (libsource (lib "eagle-import") (part "330OHM-0603-1/10W-1%"))
    )
    (comp (ref "R23")
      (value "10k")
      (footprint "eagle-import:0603")
      (libsource (lib "eagle-import") (part "10KOHM-0603-1/10W-1%"))
    )
    (comp (ref "R24")
      (value "10M")
      (footprint "eagle-import:0603")
      (libsource (lib "eagle-import") (part "22MOHM-0603-1/10W-10%"))
    )
    (comp (ref "R25")
      (value "47k")
      (footprint "eagle-import:0603")
      (libsource (lib "eagle-import") (part "22MOHM-0603-1/10W-10%"))
    )
    (comp (ref "R26")
      (value "47k")
      (footprint "eagle-import:0603")
      (libsource (lib "eagle-import") (part "22MOHM-0603-1/10W-10%"))
    )
    (comp (ref "R27")
      (value "2k")
      (footprint "eagle-import:0603")
      (libsource (lib "eagle-import") (part "22MOHM-0603-1/10W-10%"))
    )
    (comp (ref "R28")
      (value "10M")
      (footprint "eagle-import:0603")
      (libsource (lib "eagle-import") (part "22MOHM-0603-1/10W-10%"))
    )
    (comp (ref "R29")
      (value "47k")
      (footprint "eagle-import:0603")
      (libsource (lib "eagle-import") (part "22MOHM-0603-1/10W-10%"))
    )
    (comp (ref "R30")
      (value "47k")
      (footprint "eagle-import:0603")
      (libsource (lib "eagle-import") (part "22MOHM-0603-1/10W-10%"))
    )
    (comp (ref "R31")
      (value "300k")
      (footprint "eagle-import:0603")
      (libsource (lib "eagle-import") (part "22MOHM-0603-1/10W-10%"))
    )
    (comp (ref "R32")
      (value "10k")
      (footprint "eagle-import:0603")
      (libsource (lib "eagle-import") (part "10KOHM-0603-1/10W-1%"))
    )
    (comp (ref "R33")
      (value "10k")
      (footprint "eagle-import:0603")
      (libsource (lib "eagle-import") (part "10KOHM-0603-1/10W-1%"))
    )
    (comp (ref "R34")
      (value "10k")
      (footprint "eagle-import:0603")
      (libsource (lib "eagle-import") (part "10KOHM-0603-1/10W-1%"))
    )
    (comp (ref "R39")
      (value "10k")
      (footprint "eagle-import:0603")
      (libsource (lib "eagle-import") (part "10KOHM-0603-1/10W-1%"))
    )
    (comp (ref "R40")
      (value "330")
      (footprint "eagle-import:0603")
      (libsource (lib "eagle-import") (part "330OHM-0603-1/10W-1%"))
    )
    (comp (ref "R41")
      (value "10k")
      (footprint "eagle-import:0603")
      (libsource (lib "eagle-import") (part "10KOHM-0603-1/10W-1%"))
    )
    (comp (ref "R48")
      (value "10k")
      (footprint "eagle-import:0603")
      (libsource (lib "eagle-import") (part "10KOHM-0603-1/10W-1%"))
    )
    (comp (ref "R52")
      (value "330")
      (footprint "eagle-import:0603")
      (libsource (lib "eagle-import") (part "330OHM-0603-1/10W-1%"))
    )
    (comp (ref "R53")
      (value "10k")
      (footprint "eagle-import:0603")
      (libsource (lib "eagle-import") (part "10KOHM-0603-1/10W-1%"))
    )
    (comp (ref "R54")
      (value "10k")
      (footprint "eagle-import:0603")
      (libsource (lib "eagle-import") (part "10KOHM-0603-1/10W-1%"))
    )
    (comp (ref "R55")
      (value "10k")
      (footprint "eagle-import:0603")
      (libsource (lib "eagle-import") (part "10KOHM-0603-1/10W-1%"))
    )
    (comp (ref "R56")
      (value "330")
      (footprint "eagle-import:0603")
      (libsource (lib "eagle-import") (part "330OHM-0603-1/10W-1%"))
    )
    (comp (ref "R57")
      (value "10k")
      (footprint "eagle-import:0603")
      (libsource (lib "eagle-import") (part "10KOHM-0603-1/10W-1%"))
    )
    (comp (ref "R62")
      (value "330")
      (footprint "eagle-import:0603")
      (libsource (lib "eagle-import") (part "330OHM-0603-1/10W-1%"))
    )
    (comp (ref "R63")
      (value "10k")
      (footprint "eagle-import:0603")
      (libsource (lib "eagle-import") (part "10KOHM-0603-1/10W-1%"))
    )
    (comp (ref "R64")
      (value "330")
      (footprint "eagle-import:0603")
      (libsource (lib "eagle-import") (part "330OHM-0603-1/10W-1%"))
    )
    (comp (ref "R65")
      (value "10k")
      (footprint "eagle-import:0603")
      (libsource (lib "eagle-import") (part "10KOHM-0603-1/10W-1%"))
    )
    (comp (ref "R77")
      (value "330")
      (footprint "eagle-import:0603")
      (libsource (lib "eagle-import") (part "330OHM-0603-1/10W-1%"))
    )
    (comp (ref "R78")
      (value "10k")
      (footprint "eagle-import:0603")
      (libsource (lib "eagle-import") (part "10KOHM-0603-1/10W-1%"))
    )
    (comp (ref "R79")
      (value "330")
      (footprint "eagle-import:0603")
      (libsource (lib "eagle-import") (part "330OHM-0603-1/10W-1%"))
    )
    (comp (ref "R80")
      (value "10k")
      (footprint "eagle-import:0603")
      (libsource (lib "eagle-import") (part "10KOHM-0603-1/10W-1%"))
    )
    (comp (ref "S1")
      (value "SS12SDP2")
      (footprint "eagle-import:SS12SDP2")
      (fields (field (name "MOUSER_PART_NUMBER") "633-SS12SDP2"))
      (libsource (lib "eagle-import") (part "SS12SDP2"))
    )
    (comp (ref "S2")
      (value "SS12SDP2")
      (footprint "eagle-import:SS12SDP2")
      (fields (field (name "MOUSER_PART_NUMBER") "633-SS12SDP2"))
      (libsource (lib "eagle-import") (part "SS12SDP2"))
    )
    (comp (ref "S3")
      (value "SS12SDP2")
      (footprint "eagle-import:SS12SDP2")
      (fields (field (name "MOUSER_PART_NUMBER") "633-SS12SDP2"))
      (libsource (lib "eagle-import") (part "SS12SDP2"))
    )
    (comp (ref "S4")
      (value "SS12SDP2")
      (footprint "eagle-import:SS12SDP2")
      (fields (field (name "MOUSER_PART_NUMBER") "633-SS12SDP2"))
      (libsource (lib "eagle-import") (part "SS12SDP2"))
    )
    (comp (ref "S5")
      (value "SS12SDP2")
      (footprint "eagle-import:SS12SDP2")
      (fields (field (name "MOUSER_PART_NUMBER") "633-SS12SDP2"))
      (libsource (lib "eagle-import") (part "SS12SDP2"))
    )
    (comp (ref "S6")
      (value "SS12SDP2")
      (footprint "eagle-import:SS12SDP2")
      (fields (field (name "MOUSER_PART_NUMBER") "633-SS12SDP2"))
      (libsource (lib "eagle-import") (part "SS12SDP2"))
    )
    (comp (ref "SERV_FLASH")
      (value "PINHD-2X4")
      (footprint "eagle-import:2X04")
      (libsource (lib "eagle-import") (part "PINHD-2X4"))
    )
    (comp (ref "SERV_JTAG")
      (value "PINHD-2X5")
      (footprint "eagle-import:2X05")
      (libsource (lib "eagle-import") (part "PINHD-2X5"))
    )
    (comp (ref "SERV_LED")
      (value "PINHD-1X2")
      (footprint "eagle-import:1X02")
      (libsource (lib "eagle-import") (part "PINHD-1X2"))
    )
    (comp (ref "SERV_LORA")
      (value "PINHD-2X4")
      (footprint "eagle-import:2X04")
      (libsource (lib "eagle-import") (part "PINHD-2X4"))
    )
    (comp (ref "SERV_SPI")
      (value "PINHD-2X4")
      (footprint "eagle-import:2X04")
      (libsource (lib "eagle-import") (part "PINHD-2X4"))
    )
    (comp (ref "SERV_SW")
      (value "PINHD-2X2")
      (footprint "eagle-import:2X02")
      (libsource (lib "eagle-import") (part "PINHD-2X2"))
    )
    (comp (ref "SERV_UART")
      (value "PINHD-2X2")
      (footprint "eagle-import:2X02")
      (libsource (lib "eagle-import") (part "PINHD-2X2"))
    )
    (comp (ref "SPI_OPEN8_1")
      (value "SPI1")
      (footprint "eagle-import:FE10")
      (libsource (lib "eagle-import") (part "FE10-1"))
    )
    (comp (ref "SPI_OPEN8_2")
      (value "SPI0")
      (footprint "eagle-import:FE10")
      (libsource (lib "eagle-import") (part "FE10-1"))
    )
    (comp (ref "SPI_SERV_1")
      (value "SPI0")
      (footprint "eagle-import:FE10")
      (libsource (lib "eagle-import") (part "FE10-1"))
    )
    (comp (ref "SPI_SERV_2")
      (value "SPI1")
      (footprint "eagle-import:FE10")
      (libsource (lib "eagle-import") (part "FE10-1"))
    )
    (comp (ref "U$1")
      (value "2X41_HEADER")
      (footprint "eagle-import:2X41_HEADER")
      (libsource (lib "eagle-import") (part "2X41_HEADER"))
    )
    (comp (ref "U$2")
      (value "2X41_HEADER")
      (footprint "eagle-import:2X41_HEADER")
      (libsource (lib "eagle-import") (part "2X41_HEADER"))
    )
    (comp (ref "U$3")
      (value "2X41_HEADER")
      (footprint "eagle-import:2X41_HEADER")
      (libsource (lib "eagle-import") (part "2X41_HEADER"))
    )
    (comp (ref "U$4")
      (value "2X41_HEADER")
      (footprint "eagle-import:2X41_HEADER")
      (libsource (lib "eagle-import") (part "2X41_HEADER"))
    )
    (comp (ref "U1")
      (value "TPS76201DBVR")
      (footprint "eagle-import:SOT95P280X145-5N")
      (fields (field (name "MF") "Texas Instruments"))
      (libsource (lib "eagle-import") (part "TPS76201DBVR"))
    )
    (comp (ref "U2")
      (value "TPS76201DBVR")
      (footprint "eagle-import:SOT95P280X145-5N")
      (fields (field (name "MF") "Texas Instruments"))
      (libsource (lib "eagle-import") (part "TPS76201DBVR"))
    )
    (comp (ref "U3")
      (value "TPS76201DBVR")
      (footprint "eagle-import:SOT95P280X145-5N")
      (fields (field (name "MF") "Texas Instruments"))
      (libsource (lib "eagle-import") (part "TPS76201DBVR"))
    )
    (comp (ref "U4")
      (value "TPS76201DBVR")
      (footprint "eagle-import:SOT95P280X145-5N")
      (fields (field (name "MF") "Texas Instruments"))
      (libsource (lib "eagle-import") (part "TPS76201DBVR"))
    )
    (comp (ref "U5")
      (value "TPS76201DBVR")
      (footprint "eagle-import:SOT95P280X145-5N")
      (fields (field (name "MF") "Texas Instruments"))
      (libsource (lib "eagle-import") (part "TPS76201DBVR"))
    )
    (comp (ref "U6")
      (value "TPS76201DBVR")
      (footprint "eagle-import:SOT95P280X145-5N")
      (fields (field (name "MF") "Texas Instruments"))
      (libsource (lib "eagle-import") (part "TPS76201DBVR"))
    )
    (comp (ref "USB-UART_OPEN8_1")
      (value "PINHD-1X4")
      (footprint "eagle-import:1X04")
      (libsource (lib "eagle-import") (part "PINHD-1X4"))
    )
    (comp (ref "USB-UART_OPEN8_2")
      (value "PINHD-1X4")
      (footprint "eagle-import:1X04")
      (libsource (lib "eagle-import") (part "PINHD-1X4"))
    )
    (comp (ref "USB-UART_SERV_1")
      (value "PINHD-1X4")
      (footprint "eagle-import:1X04")
      (libsource (lib "eagle-import") (part "PINHD-1X4"))
    )
    (comp (ref "USB-UART_SERV_2")
      (value "PINHD-1X4")
      (footprint "eagle-import:1X04")
      (libsource (lib "eagle-import") (part "PINHD-1X4"))
    )
    (comp (ref "Y2")
      (value "HC-49SM8MHZ20PF30PPM")
      (footprint "eagle-import:HC49SM8MHZ20PF30PPM")
      (fields (field (name "MANUFACTURER_PART_NUMBER") "HC-49SM8MHz20pF30ppm"))
      (libsource (lib "eagle-import") (part "HC-49SM8MHZ20PF30PPM"))
    )
    (comp (ref "Y3")
      (value "Q13FC1350000400")
      (footprint "eagle-import:Q13FC1350000400")
      (libsource (lib "eagle-import") (part "Q13FC1350000400"))
    )
  )
  (nets
    (net (code "1") (name "1") (class "Default")
      (node (ref "U$1") (pin "1") (pinfunction "1_1") (pintype "bidirectional"))
    )
    (net (code "2") (name "2") (class "Default")
      (node (ref "U$1") (pin "4") (pinfunction "4_4") (pintype "bidirectional"))
    )
    (net (code "3") (name "4") (class "Default")
      (node (ref "U$1") (pin "6") (pinfunction "6_6") (pintype "bidirectional"))
    )
    (net (code "4") (name "5") (class "Default")
      (node (ref "U$1") (pin "5") (pinfunction "5_5") (pintype "bidirectional"))
    )
    (net (code "5") (name "6") (class "Default")
      (node (ref "U$1") (pin "8") (pinfunction "8_8") (pintype "bidirectional"))
    )
    (net (code "6") (name "7") (class "Default")
      (node (ref "U$1") (pin "7") (pinfunction "7_7") (pintype "bidirectional"))
    )
    (net (code "7") (name "8") (class "Default")
      (node (ref "U$1") (pin "10") (pinfunction "10_10") (pintype "bidirectional"))
    )
    (net (code "8") (name "8MHZ_CLOCK") (class "Default")
      (node (ref "CLOCK") (pin "3") (pinfunction "3_3") (pintype "passive"))
      (node (ref "IC1") (pin "4") (pinfunction "Y_4") (pintype "bidirectional"))
      (node (ref "R24") (pin "2") (pinfunction "2_2") (pintype "passive"))
      (node (ref "R27") (pin "2") (pinfunction "2_2") (pintype "passive"))
    )
    (net (code "9") (name "9") (class "Default")
      (node (ref "U$1") (pin "9") (pinfunction "9_9") (pintype "bidirectional"))
    )
    (net (code "10") (name "10") (class "Default")
      (node (ref "U$1") (pin "12") (pinfunction "12_12") (pintype "bidirectional"))
    )
    (net (code "11") (name "11") (class "Default")
      (node (ref "U$1") (pin "11") (pinfunction "11_11") (pintype "bidirectional"))
    )
    (net (code "12") (name "12") (class "Default")
      (node (ref "U$1") (pin "14") (pinfunction "14_14") (pintype "bidirectional"))
    )
    (net (code "13") (name "14") (class "Default")
      (node (ref "U$1") (pin "16") (pinfunction "16_16") (pintype "bidirectional"))
    )
    (net (code "14") (name "15") (class "Default")
      (node (ref "U$1") (pin "15") (pinfunction "15_15") (pintype "bidirectional"))
    )
    (net (code "15") (name "16") (class "Default")
      (node (ref "U$1") (pin "18") (pinfunction "18_18") (pintype "bidirectional"))
    )
    (net (code "16") (name "17") (class "Default")
      (node (ref "U$1") (pin "17") (pinfunction "17_17") (pintype "bidirectional"))
    )
    (net (code "17") (name "18") (class "Default")
      (node (ref "U$1") (pin "20") (pinfunction "20_20") (pintype "bidirectional"))
    )
    (net (code "18") (name "19") (class "Default")
      (node (ref "U$1") (pin "19") (pinfunction "19_19") (pintype "bidirectional"))
    )
    (net (code "19") (name "20") (class "Default")
      (node (ref "U$1") (pin "22") (pinfunction "22_22") (pintype "bidirectional"))
    )
    (net (code "20") (name "21") (class "Default")
      (node (ref "U$1") (pin "21") (pinfunction "21_21") (pintype "bidirectional"))
    )
    (net (code "21") (name "22") (class "Default")
      (node (ref "U$1") (pin "24") (pinfunction "24_24") (pintype "bidirectional"))
    )
    (net (code "22") (name "23") (class "Default")
      (node (ref "U$1") (pin "23") (pinfunction "23_23") (pintype "bidirectional"))
    )
    (net (code "23") (name "24") (class "Default")
      (node (ref "U$1") (pin "26") (pinfunction "26_26") (pintype "bidirectional"))
    )
    (net (code "24") (name "25") (class "Default")
      (node (ref "U$1") (pin "25") (pinfunction "25_25") (pintype "bidirectional"))
    )
    (net (code "25") (name "26") (class "Default")
      (node (ref "U$1") (pin "28") (pinfunction "28_28") (pintype "bidirectional"))
    )
    (net (code "26") (name "28") (class "Default")
      (node (ref "U$1") (pin "30") (pinfunction "30_30") (pintype "bidirectional"))
    )
    (net (code "27") (name "29") (class "Default")
      (node (ref "U$1") (pin "29") (pinfunction "29_29") (pintype "bidirectional"))
    )
    (net (code "28") (name "30") (class "Default")
      (node (ref "U$1") (pin "32") (pinfunction "32_32") (pintype "bidirectional"))
    )
    (net (code "29") (name "31") (class "Default")
      (node (ref "U$1") (pin "31") (pinfunction "31_31") (pintype "bidirectional"))
    )
    (net (code "30") (name "32") (class "Default")
      (node (ref "U$1") (pin "34") (pinfunction "34_34") (pintype "bidirectional"))
    )
    (net (code "31") (name "32KHZ_CLOCK") (class "Default")
      (node (ref "CLOCK") (pin "1") (pinfunction "1_1") (pintype "passive"))
      (node (ref "IC2") (pin "4") (pinfunction "Y_4") (pintype "bidirectional"))
      (node (ref "R28") (pin "2") (pinfunction "2_2") (pintype "passive"))
      (node (ref "R31") (pin "2") (pinfunction "2_2") (pintype "passive"))
    )
    (net (code "32") (name "33") (class "Default")
      (node (ref "U$1") (pin "33") (pinfunction "33_33") (pintype "bidirectional"))
    )
    (net (code "33") (name "34") (class "Default")
      (node (ref "U$1") (pin "36") (pinfunction "36_36") (pintype "bidirectional"))
    )
    (net (code "34") (name "35") (class "Default")
      (node (ref "U$1") (pin "35") (pinfunction "35_35") (pintype "bidirectional"))
    )
    (net (code "35") (name "36") (class "Default")
      (node (ref "U$1") (pin "38") (pinfunction "38_38") (pintype "bidirectional"))
    )
    (net (code "36") (name "38") (class "Default")
      (node (ref "U$1") (pin "40") (pinfunction "40_40") (pintype "bidirectional"))
    )
    (net (code "37") (name "39") (class "Default")
      (node (ref "U$1") (pin "39") (pinfunction "39_39") (pintype "bidirectional"))
    )
    (net (code "38") (name "40") (class "Default")
      (node (ref "U$1") (pin "42") (pinfunction "42_42") (pintype "bidirectional"))
    )
    (net (code "39") (name "41") (class "Default")
      (node (ref "U$2") (pin "1") (pinfunction "1_1") (pintype "bidirectional"))
    )
    (net (code "40") (name "42") (class "Default")
      (node (ref "U$2") (pin "4") (pinfunction "4_4") (pintype "bidirectional"))
    )
    (net (code "41") (name "44") (class "Default")
      (node (ref "U$2") (pin "6") (pinfunction "6_6") (pintype "bidirectional"))
    )
    (net (code "42") (name "45") (class "Default")
      (node (ref "U$2") (pin "5") (pinfunction "5_5") (pintype "bidirectional"))
    )
    (net (code "43") (name "46") (class "Default")
      (node (ref "U$2") (pin "8") (pinfunction "8_8") (pintype "bidirectional"))
    )
    (net (code "44") (name "47") (class "Default")
      (node (ref "U$2") (pin "7") (pinfunction "7_7") (pintype "bidirectional"))
    )
    (net (code "45") (name "48") (class "Default")
      (node (ref "U$2") (pin "10") (pinfunction "10_10") (pintype "bidirectional"))
    )
    (net (code "46") (name "49") (class "Default")
      (node (ref "U$2") (pin "9") (pinfunction "9_9") (pintype "bidirectional"))
    )
    (net (code "47") (name "50") (class "Default")
      (node (ref "U$2") (pin "12") (pinfunction "12_12") (pintype "bidirectional"))
    )
    (net (code "48") (name "51") (class "Default")
      (node (ref "U$2") (pin "11") (pinfunction "11_11") (pintype "bidirectional"))
    )
    (net (code "49") (name "52") (class "Default")
      (node (ref "U$2") (pin "14") (pinfunction "14_14") (pintype "bidirectional"))
    )
    (net (code "50") (name "54") (class "Default")
      (node (ref "U$2") (pin "16") (pinfunction "16_16") (pintype "bidirectional"))
    )
    (net (code "51") (name "55") (class "Default")
      (node (ref "U$2") (pin "15") (pinfunction "15_15") (pintype "bidirectional"))
    )
    (net (code "52") (name "56") (class "Default")
      (node (ref "U$2") (pin "18") (pinfunction "18_18") (pintype "bidirectional"))
    )
    (net (code "53") (name "57") (class "Default")
      (node (ref "U$2") (pin "17") (pinfunction "17_17") (pintype "bidirectional"))
    )
    (net (code "54") (name "58") (class "Default")
      (node (ref "U$2") (pin "20") (pinfunction "20_20") (pintype "bidirectional"))
    )
    (net (code "55") (name "59") (class "Default")
      (node (ref "U$2") (pin "19") (pinfunction "19_19") (pintype "bidirectional"))
    )
    (net (code "56") (name "60") (class "Default")
      (node (ref "U$2") (pin "22") (pinfunction "22_22") (pintype "bidirectional"))
    )
    (net (code "57") (name "67") (class "Default")
      (node (ref "U$2") (pin "27") (pinfunction "27_27") (pintype "bidirectional"))
    )
    (net (code "58") (name "78") (class "Default")
      (node (ref "U$2") (pin "40") (pinfunction "40_40") (pintype "bidirectional"))
    )
    (net (code "59") (name "79") (class "Default")
      (node (ref "U$2") (pin "39") (pinfunction "39_39") (pintype "bidirectional"))
    )
    (net (code "60") (name "80") (class "Default")
      (node (ref "U$2") (pin "42") (pinfunction "42_42") (pintype "bidirectional"))
    )
    (net (code "61") (name "81") (class "Default")
      (node (ref "U$3") (pin "1") (pinfunction "1_1") (pintype "bidirectional"))
    )
    (net (code "62") (name "82") (class "Default")
      (node (ref "U$3") (pin "4") (pinfunction "4_4") (pintype "bidirectional"))
    )
    (net (code "63") (name "84") (class "Default")
      (node (ref "U$3") (pin "6") (pinfunction "6_6") (pintype "bidirectional"))
    )
    (net (code "64") (name "93") (class "Default")
      (node (ref "U$3") (pin "13") (pinfunction "13_13") (pintype "bidirectional"))
    )
    (net (code "65") (name "107") (class "Default")
      (node (ref "U$3") (pin "27") (pinfunction "27_27") (pintype "bidirectional"))
    )
    (net (code "66") (name "118") (class "Default")
      (node (ref "U$3") (pin "40") (pinfunction "40_40") (pintype "bidirectional"))
    )
    (net (code "67") (name "119") (class "Default")
      (node (ref "U$3") (pin "39") (pinfunction "39_39") (pintype "bidirectional"))
    )
    (net (code "68") (name "120") (class "Default")
      (node (ref "U$3") (pin "42") (pinfunction "42_42") (pintype "bidirectional"))
    )
    (net (code "69") (name "121") (class "Default")
      (node (ref "U$4") (pin "1") (pinfunction "1_1") (pintype "bidirectional"))
    )
    (net (code "70") (name "122") (class "Default")
      (node (ref "U$4") (pin "4") (pinfunction "4_4") (pintype "bidirectional"))
    )
    (net (code "71") (name "124") (class "Default")
      (node (ref "U$4") (pin "6") (pinfunction "6_6") (pintype "bidirectional"))
    )
    (net (code "72") (name "135") (class "Default")
      (node (ref "U$4") (pin "15") (pinfunction "15_15") (pintype "bidirectional"))
    )
    (net (code "73") (name "139") (class "Default")
      (node (ref "U$4") (pin "19") (pinfunction "19_19") (pintype "bidirectional"))
    )
    (net (code "74") (name "140") (class "Default")
      (node (ref "U$4") (pin "22") (pinfunction "22_22") (pintype "bidirectional"))
    )
    (net (code "75") (name "141") (class "Default")
      (node (ref "U$4") (pin "21") (pinfunction "21_21") (pintype "bidirectional"))
    )
    (net (code "76") (name "142") (class "Default")
      (node (ref "U$4") (pin "24") (pinfunction "24_24") (pintype "bidirectional"))
    )
    (net (code "77") (name "143") (class "Default")
      (node (ref "U$4") (pin "23") (pinfunction "23_23") (pintype "bidirectional"))
    )
    (net (code "78") (name "144") (class "Default")
      (node (ref "U$4") (pin "26") (pinfunction "26_26") (pintype "bidirectional"))
    )
    (net (code "79") (name "145") (class "Default")
      (node (ref "U$4") (pin "25") (pinfunction "25_25") (pintype "bidirectional"))
    )
    (net (code "80") (name "146") (class "Default")
      (node (ref "U$4") (pin "28") (pinfunction "28_28") (pintype "bidirectional"))
    )
    (net (code "81") (name "148") (class "Default")
      (node (ref "U$4") (pin "30") (pinfunction "30_30") (pintype "bidirectional"))
    )
    (net (code "82") (name "149") (class "Default")
      (node (ref "U$4") (pin "29") (pinfunction "29_29") (pintype "bidirectional"))
    )
    (net (code "83") (name "150") (class "Default")
      (node (ref "U$4") (pin "32") (pinfunction "32_32") (pintype "bidirectional"))
    )
    (net (code "84") (name "151") (class "Default")
      (node (ref "U$4") (pin "31") (pinfunction "31_31") (pintype "bidirectional"))
    )
    (net (code "85") (name "152") (class "Default")
      (node (ref "U$4") (pin "34") (pinfunction "34_34") (pintype "bidirectional"))
    )
    (net (code "86") (name "153") (class "Default")
      (node (ref "U$4") (pin "33") (pinfunction "33_33") (pintype "bidirectional"))
    )
    (net (code "87") (name "154") (class "Default")
      (node (ref "U$4") (pin "36") (pinfunction "36_36") (pintype "bidirectional"))
    )
    (net (code "88") (name "155") (class "Default")
      (node (ref "U$4") (pin "35") (pinfunction "35_35") (pintype "bidirectional"))
    )
    (net (code "89") (name "156") (class "Default")
      (node (ref "U$4") (pin "38") (pinfunction "38_38") (pintype "bidirectional"))
    )
    (net (code "90") (name "158") (class "Default")
      (node (ref "U$4") (pin "40") (pinfunction "40_40") (pintype "bidirectional"))
    )
    (net (code "91") (name "159") (class "Default")
      (node (ref "U$4") (pin "39") (pinfunction "39_39") (pintype "bidirectional"))
    )
    (net (code "92") (name "160") (class "Default")
      (node (ref "U$4") (pin "42") (pinfunction "42_42") (pintype "bidirectional"))
    )
    (net (code "93") (name "DR_CLOCK") (class "Default")
      (node (ref "CLOCK") (pin "2") (pinfunction "2_2") (pintype "passive"))
      (node (ref "CLOCK") (pin "4") (pinfunction "4_4") (pintype "passive"))
      (node (ref "CLOCK") (pin "6") (pinfunction "6_6") (pintype "passive"))
      (node (ref "U$2") (pin "28") (pinfunction "28_28") (pintype "bidirectional"))
    )
    (net (code "94") (name "DR_MUX") (class "Default")
      (node (ref "MUX") (pin "1") (pinfunction "1_1") (pintype "passive"))
      (node (ref "R34") (pin "2") (pinfunction "2_2") (pintype "passive"))
      (node (ref "U$3") (pin "23") (pinfunction "23_23") (pintype "bidirectional"))
    )
    (net (code "95") (name "DR_OPEN8_DIPSW_0") (class "Default")
      (node (ref "OPEN8_SW") (pin "1") (pinfunction "1_1") (pintype "passive"))
      (node (ref "U$3") (pin "11") (pinfunction "11_11") (pintype "bidirectional"))
    )
    (net (code "96") (name "DR_OPEN8_DIPSW_1") (class "Default")
      (node (ref "OPEN8_SW") (pin "3") (pinfunction "3_3") (pintype "passive"))
      (node (ref "U$3") (pin "14") (pinfunction "14_14") (pintype "bidirectional"))
    )
    (net (code "97") (name "DR_OPEN8_JTAG_TCK") (class "Default")
      (node (ref "OPEN8_JTAG") (pin "7") (pinfunction "7_7") (pintype "passive"))
      (node (ref "U$2") (pin "38") (pinfunction "38_38") (pintype "bidirectional"))
    )
    (net (code "98") (name "DR_OPEN8_JTAG_TDI") (class "Default")
      (node (ref "OPEN8_JTAG") (pin "1") (pinfunction "1_1") (pintype "passive"))
      (node (ref "U$3") (pin "5") (pinfunction "5_5") (pintype "bidirectional"))
    )
    (net (code "99") (name "DR_OPEN8_JTAG_TDO") (class "Default")
      (node (ref "OPEN8_JTAG") (pin "3") (pinfunction "3_3") (pintype "passive"))
      (node (ref "U$3") (pin "8") (pinfunction "8_8") (pintype "bidirectional"))
    )
    (net (code "100") (name "DR_OPEN8_JTAG_TMS") (class "Default")
      (node (ref "OPEN8_JTAG") (pin "9") (pinfunction "9_9") (pintype "passive"))
      (node (ref "U$2") (pin "35") (pinfunction "35_35") (pintype "bidirectional"))
    )
    (net (code "101") (name "DR_OPEN8_JTAG_TRST") (class "Default")
      (node (ref "OPEN8_JTAG") (pin "5") (pinfunction "5_5") (pintype "passive"))
      (node (ref "U$3") (pin "18") (pinfunction "18_18") (pintype "bidirectional"))
    )
    (net (code "102") (name "DR_OPEN8_LED_0") (class "Default")
      (node (ref "OPEN8_LED") (pin "1") (pinfunction "1_1") (pintype "passive"))
      (node (ref "U$3") (pin "7") (pinfunction "7_7") (pintype "bidirectional"))
    )
    (net (code "103") (name "DR_OPEN8_PSPI_CS") (class "Default")
      (node (ref "OPEN8_SPI") (pin "3") (pinfunction "3_3") (pintype "passive"))
      (node (ref "U$3") (pin "19") (pinfunction "19_19") (pintype "bidirectional"))
    )
    (net (code "104") (name "DR_OPEN8_PSPI_MISO") (class "Default")
      (node (ref "OPEN8_SPI") (pin "7") (pinfunction "7_7") (pintype "passive"))
      (node (ref "U$3") (pin "17") (pinfunction "17_17") (pintype "bidirectional"))
    )
    (net (code "105") (name "DR_OPEN8_PSPI_MOSI") (class "Default")
      (node (ref "OPEN8_SPI") (pin "5") (pinfunction "5_5") (pintype "passive"))
      (node (ref "U$3") (pin "20") (pinfunction "20_20") (pintype "bidirectional"))
    )
    (net (code "106") (name "DR_OPEN8_PSPI_SCK") (class "Default")
      (node (ref "OPEN8_SPI") (pin "1") (pinfunction "1_1") (pintype "passive"))
      (node (ref "U$3") (pin "22") (pinfunction "22_22") (pintype "bidirectional"))
    )
    (net (code "107") (name "DR_OPEN8_RESET") (class "Default")
      (node (ref "NRESET_OPEN8") (pin "1") (pinfunction "1_1") (pintype "passive"))
      (node (ref "U$2") (pin "30") (pinfunction "30_30") (pintype "bidirectional"))
    )
    (net (code "108") (name "DR_OPEN8_SPIFLASH_CIPO") (class "Default")
      (node (ref "OPEN8_FLASH") (pin "1") (pinfunction "1_1") (pintype "passive"))
      (node (ref "U$3") (pin "16") (pinfunction "16_16") (pintype "bidirectional"))
    )
    (net (code "109") (name "DR_OPEN8_SPIFLASH_COPI") (class "Default")
      (node (ref "OPEN8_FLASH") (pin "5") (pinfunction "5_5") (pintype "passive"))
      (node (ref "U$3") (pin "9") (pinfunction "9_9") (pintype "bidirectional"))
    )
    (net (code "110") (name "DR_OPEN8_SPIFLASH_CS") (class "Default")
      (node (ref "OPEN8_FLASH") (pin "3") (pinfunction "3_3") (pintype "passive"))
      (node (ref "U$3") (pin "12") (pinfunction "12_12") (pintype "bidirectional"))
    )
    (net (code "111") (name "DR_OPEN8_SPIFLASH_SCK") (class "Default")
      (node (ref "OPEN8_FLASH") (pin "7") (pinfunction "7_7") (pintype "passive"))
      (node (ref "U$3") (pin "10") (pinfunction "10_10") (pintype "bidirectional"))
    )
    (net (code "112") (name "DR_OPEN8_SPI_CS") (class "Default")
      (node (ref "OPEN8_LORA") (pin "3") (pinfunction "3_3") (pintype "passive"))
      (node (ref "U$2") (pin "33") (pinfunction "33_33") (pintype "bidirectional"))
    )
    (net (code "113") (name "DR_OPEN8_SPI_MISO") (class "Default")
      (node (ref "OPEN8_LORA") (pin "7") (pinfunction "7_7") (pintype "passive"))
      (node (ref "U$2") (pin "31") (pinfunction "31_31") (pintype "bidirectional"))
    )
    (net (code "114") (name "DR_OPEN8_SPI_MOSI") (class "Default")
      (node (ref "OPEN8_LORA") (pin "5") (pinfunction "5_5") (pintype "passive"))
      (node (ref "U$2") (pin "34") (pinfunction "34_34") (pintype "bidirectional"))
    )
    (net (code "115") (name "DR_OPEN8_SPI_SCK") (class "Default")
      (node (ref "OPEN8_LORA") (pin "1") (pinfunction "1_1") (pintype "passive"))
      (node (ref "U$2") (pin "36") (pinfunction "36_36") (pintype "bidirectional"))
    )
    (net (code "116") (name "DR_OPEN8_UART_RXD") (class "Default")
      (node (ref "OPEN8_UART") (pin "3") (pinfunction "3_3") (pintype "passive"))
      (node (ref "U$2") (pin "29") (pinfunction "29_29") (pintype "bidirectional"))
    )
    (net (code "117") (name "DR_OPEN8_UART_TXD") (class "Default")
      (node (ref "OPEN8_UART") (pin "1") (pinfunction "1_1") (pintype "passive"))
      (node (ref "U$2") (pin "32") (pinfunction "32_32") (pintype "bidirectional"))
    )
    (net (code "118") (name "DR_OPEN8_VDD") (class "Default")
      (node (ref "C13") (pin "1") (pinfunction "1_1") (pintype "passive"))
      (node (ref "C18") (pin "1") (pinfunction "1_1") (pintype "passive"))
      (node (ref "POWER") (pin "10") (pinfunction "10_10") (pintype "passive"))
      (node (ref "Q16") (pin "1") (pinfunction "G_1") (pintype "bidirectional"))
      (node (ref "R63") (pin "2") (pinfunction "2_2") (pintype "passive"))
      (node (ref "U$2") (pin "23") (pinfunction "23_23") (pintype "bidirectional"))
    )
    (net (code "119") (name "DR_RAM_VDD") (class "Default")
      (node (ref "C23") (pin "1") (pinfunction "1_1") (pintype "passive"))
      (node (ref "C24") (pin "1") (pinfunction "1_1") (pintype "passive"))
      (node (ref "POWER") (pin "12") (pinfunction "12_12") (pintype "passive"))
      (node (ref "Q2") (pin "1") (pinfunction "G_1") (pintype "bidirectional"))
      (node (ref "R23") (pin "2") (pinfunction "2_2") (pintype "passive"))
      (node (ref "U$2") (pin "21") (pinfunction "21_21") (pintype "bidirectional"))
    )
    (net (code "120") (name "DR_SERV_DIPSW_0") (class "Default")
      (node (ref "SERV_SW") (pin "1") (pinfunction "1_1") (pintype "passive"))
      (node (ref "U$4") (pin "9") (pinfunction "9_9") (pintype "bidirectional"))
    )
    (net (code "121") (name "DR_SERV_DIPSW_1") (class "Default")
      (node (ref "SERV_SW") (pin "3") (pinfunction "3_3") (pintype "passive"))
      (node (ref "U$4") (pin "12") (pinfunction "12_12") (pintype "bidirectional"))
    )
    (net (code "122") (name "DR_SERV_JTAG_TCK") (class "Default")
      (node (ref "SERV_JTAG") (pin "7") (pinfunction "7_7") (pintype "passive"))
      (node (ref "U$3") (pin "36") (pinfunction "36_36") (pintype "bidirectional"))
    )
    (net (code "123") (name "DR_SERV_JTAG_TDI") (class "Default")
      (node (ref "SERV_JTAG") (pin "5") (pinfunction "5_5") (pintype "passive"))
      (node (ref "U$3") (pin "35") (pinfunction "35_35") (pintype "bidirectional"))
    )
    (net (code "124") (name "DR_SERV_JTAG_TDO") (class "Default")
      (node (ref "SERV_JTAG") (pin "3") (pinfunction "3_3") (pintype "passive"))
      (node (ref "U$3") (pin "38") (pinfunction "38_38") (pintype "bidirectional"))
    )
    (net (code "125") (name "DR_SERV_JTAG_TMS") (class "Default")
      (node (ref "SERV_JTAG") (pin "9") (pinfunction "9_9") (pintype "passive"))
      (node (ref "U$3") (pin "33") (pinfunction "33_33") (pintype "bidirectional"))
    )
    (net (code "126") (name "DR_SERV_JTAG_TRST") (class "Default")
      (node (ref "SERV_JTAG") (pin "1") (pinfunction "1_1") (pintype "passive"))
      (node (ref "U$4") (pin "14") (pinfunction "14_14") (pintype "bidirectional"))
    )
    (net (code "127") (name "DR_SERV_LED_0") (class "Default")
      (node (ref "SERV_LED") (pin "1") (pinfunction "1_1") (pintype "passive"))
      (node (ref "U$4") (pin "5") (pinfunction "5_5") (pintype "bidirectional"))
    )
    (net (code "128") (name "DR_SERV_PSPI_CS") (class "Default")
      (node (ref "SERV_SPI") (pin "3") (pinfunction "3_3") (pintype "passive"))
      (node (ref "U$4") (pin "17") (pinfunction "17_17") (pintype "bidirectional"))
    )
    (net (code "129") (name "DR_SERV_PSPI_MISO") (class "Default")
      (node (ref "SERV_SPI") (pin "7") (pinfunction "7_7") (pintype "passive"))
      (node (ref "U$4") (pin "16") (pinfunction "16_16") (pintype "bidirectional"))
    )
    (net (code "130") (name "DR_SERV_PSPI_MOSI") (class "Default")
      (node (ref "SERV_SPI") (pin "5") (pinfunction "5_5") (pintype "passive"))
      (node (ref "U$4") (pin "18") (pinfunction "18_18") (pintype "bidirectional"))
    )
    (net (code "131") (name "DR_SERV_PSPI_SCK") (class "Default")
      (node (ref "SERV_SPI") (pin "1") (pinfunction "1_1") (pintype "passive"))
      (node (ref "U$4") (pin "20") (pinfunction "20_20") (pintype "bidirectional"))
    )
    (net (code "132") (name "DR_SERV_RESET") (class "Default")
      (node (ref "NRESET_SERV") (pin "1") (pinfunction "1_1") (pintype "passive"))
      (node (ref "U$3") (pin "26") (pinfunction "26_26") (pintype "bidirectional"))
    )
    (net (code "133") (name "DR_SERV_SPIFLASH_CIPO") (class "Default")
      (node (ref "SERV_FLASH") (pin "1") (pinfunction "1_1") (pintype "passive"))
      (node (ref "U$4") (pin "11") (pinfunction "11_11") (pintype "bidirectional"))
    )
    (net (code "134") (name "DR_SERV_SPIFLASH_COPI") (class "Default")
      (node (ref "SERV_FLASH") (pin "5") (pinfunction "5_5") (pintype "passive"))
      (node (ref "U$4") (pin "7") (pinfunction "7_7") (pintype "bidirectional"))
    )
    (net (code "135") (name "DR_SERV_SPIFLASH_CS") (class "Default")
      (node (ref "SERV_FLASH") (pin "3") (pinfunction "3_3") (pintype "passive"))
      (node (ref "U$4") (pin "8") (pinfunction "8_8") (pintype "bidirectional"))
    )
    (net (code "136") (name "DR_SERV_SPIFLASH_SCK") (class "Default")
      (node (ref "SERV_FLASH") (pin "7") (pinfunction "7_7") (pintype "passive"))
      (node (ref "U$4") (pin "10") (pinfunction "10_10") (pintype "bidirectional"))
    )
    (net (code "137") (name "DR_SERV_SPI_CS") (class "Default")
      (node (ref "SERV_LORA") (pin "3") (pinfunction "3_3") (pintype "passive"))
      (node (ref "U$3") (pin "31") (pinfunction "31_31") (pintype "bidirectional"))
    )
    (net (code "138") (name "DR_SERV_SPI_MISO") (class "Default")
      (node (ref "SERV_LORA") (pin "7") (pinfunction "7_7") (pintype "passive"))
      (node (ref "U$3") (pin "29") (pinfunction "29_29") (pintype "bidirectional"))
    )
    (net (code "139") (name "DR_SERV_SPI_MOSI") (class "Default")
      (node (ref "SERV_LORA") (pin "5") (pinfunction "5_5") (pintype "passive"))
      (node (ref "U$3") (pin "32") (pinfunction "32_32") (pintype "bidirectional"))
    )
    (net (code "140") (name "DR_SERV_SPI_SCK") (class "Default")
      (node (ref "SERV_LORA") (pin "1") (pinfunction "1_1") (pintype "passive"))
      (node (ref "U$3") (pin "34") (pinfunction "34_34") (pintype "bidirectional"))
    )
    (net (code "141") (name "DR_SERV_UART_RXD") (class "Default")
      (node (ref "SERV_UART") (pin "1") (pinfunction "1_1") (pintype "passive"))
      (node (ref "U$3") (pin "28") (pinfunction "28_28") (pintype "bidirectional"))
    )
    (net (code "142") (name "DR_SERV_UART_TXD") (class "Default")
      (node (ref "SERV_UART") (pin "3") (pinfunction "3_3") (pintype "passive"))
      (node (ref "U$3") (pin "30") (pinfunction "30_30") (pintype "bidirectional"))
    )
    (net (code "143") (name "DR_SERV_VDD") (class "Default")
      (node (ref "C14") (pin "1") (pinfunction "1_1") (pintype "passive"))
      (node (ref "C15") (pin "1") (pinfunction "1_1") (pintype "passive"))
      (node (ref "POWER") (pin "8") (pinfunction "8_8") (pintype "passive"))
      (node (ref "Q17") (pin "1") (pinfunction "G_1") (pintype "bidirectional"))
      (node (ref "R65") (pin "2") (pinfunction "2_2") (pintype "passive"))
      (node (ref "U$3") (pin "21") (pinfunction "21_21") (pintype "bidirectional"))
    )
    (net (code "144") (name "GND") (class "Default")
      (node (ref "C1") (pin "2") (pinfunction "2_2") (pintype "passive"))
      (node (ref "C11") (pin "2") (pinfunction "2_2") (pintype "passive"))
      (node (ref "C13") (pin "2") (pinfunction "2_2") (pintype "passive"))
      (node (ref "C14") (pin "2") (pinfunction "2_2") (pintype "passive"))
      (node (ref "C15") (pin "2") (pinfunction "2_2") (pintype "passive"))
      (node (ref "C16") (pin "2") (pinfunction "2_2") (pintype "passive"))
      (node (ref "C17") (pin "2") (pinfunction "2_2") (pintype "passive"))
      (node (ref "C18") (pin "2") (pinfunction "2_2") (pintype "passive"))
      (node (ref "C19") (pin "2") (pinfunction "2_2") (pintype "passive"))
      (node (ref "C20") (pin "2") (pinfunction "2_2") (pintype "passive"))
      (node (ref "C21") (pin "2") (pinfunction "2_2") (pintype "passive"))
      (node (ref "C23") (pin "2") (pinfunction "2_2") (pintype "passive"))
      (node (ref "C24") (pin "2") (pinfunction "2_2") (pintype "passive"))
      (node (ref "C25") (pin "2") (pinfunction "2_2") (pintype "passive"))
      (node (ref "C26") (pin "1") (pinfunction "1_1") (pintype "passive"))
      (node (ref "C27") (pin "2") (pinfunction "2_2") (pintype "passive"))
      (node (ref "C28") (pin "1") (pinfunction "1_1") (pintype "passive"))
      (node (ref "C29") (pin "2") (pinfunction "2_2") (pintype "passive"))
      (node (ref "C3") (pin "2") (pinfunction "2_2") (pintype "passive"))
      (node (ref "C30") (pin "2") (pinfunction "2_2") (pintype "passive"))
      (node (ref "C31") (pin "2") (pinfunction "2_2") (pintype "passive"))
      (node (ref "C32") (pin "2") (pinfunction "2_2") (pintype "passive"))
      (node (ref "C34") (pin "2") (pinfunction "2_2") (pintype "passive"))
      (node (ref "C35") (pin "2") (pinfunction "2_2") (pintype "passive"))
      (node (ref "C36") (pin "2") (pinfunction "2_2") (pintype "passive"))
      (node (ref "C37") (pin "2") (pinfunction "2_2") (pintype "passive"))
      (node (ref "C38") (pin "2") (pinfunction "2_2") (pintype "passive"))
      (node (ref "C39") (pin "2") (pinfunction "2_2") (pintype "passive"))
      (node (ref "C40") (pin "2") (pinfunction "2_2") (pintype "passive"))
      (node (ref "C41") (pin "2") (pinfunction "2_2") (pintype "passive"))
      (node (ref "C42") (pin "2") (pinfunction "2_2") (pintype "passive"))
      (node (ref "C43") (pin "2") (pinfunction "2_2") (pintype "passive"))
      (node (ref "C44") (pin "2") (pinfunction "2_2") (pintype "passive"))
      (node (ref "C5") (pin "2") (pinfunction "2_2") (pintype "passive"))
      (node (ref "C6") (pin "2") (pinfunction "2_2") (pintype "passive"))
      (node (ref "C9") (pin "2") (pinfunction "2_2") (pintype "passive"))
      (node (ref "FLASH_OPEN8") (pin "3") (pinfunction "3_3") (pintype "passive"))
      (node (ref "FLASH_OPEN8") (pin "4") (pinfunction "4_4") (pintype "passive"))
      (node (ref "FLASH_SERV") (pin "3") (pinfunction "3_3") (pintype "passive"))
      (node (ref "FLASH_SERV") (pin "4") (pinfunction "4_4") (pintype "passive"))
      (node (ref "GND") (pin "1") (pinfunction "1_1") (pintype "passive"))
      (node (ref "GND") (pin "2") (pinfunction "2_2") (pintype "passive"))
      (node (ref "GND") (pin "3") (pinfunction "3_3") (pintype "passive"))
      (node (ref "GND") (pin "4") (pinfunction "4_4") (pintype "passive"))
      (node (ref "GND") (pin "5") (pinfunction "5_5") (pintype "passive"))
      (node (ref "GND") (pin "6") (pinfunction "6_6") (pintype "passive"))
      (node (ref "IC10") (pin "11") (pinfunction "GND_11") (pintype "bidirectional"))
      (node (ref "IC11") (pin "11") (pinfunction "GND_11") (pintype "bidirectional"))
      (node (ref "IC3") (pin "11") (pinfunction "GND_11") (pintype "bidirectional"))
      (node (ref "IC4") (pin "11") (pinfunction "GND_11") (pintype "bidirectional"))
      (node (ref "IC5") (pin "11") (pinfunction "GND_11") (pintype "bidirectional"))
      (node (ref "IC6") (pin "11") (pinfunction "GND_11") (pintype "bidirectional"))
      (node (ref "IC7") (pin "11") (pinfunction "GND_11") (pintype "bidirectional"))
      (node (ref "IC8") (pin "11") (pinfunction "GND_11") (pintype "bidirectional"))
      (node (ref "J4") (pin "1") (pinfunction "1_1") (pintype "bidirectional"))
      (node (ref "J4") (pin "2") (pinfunction "2_2") (pintype "bidirectional"))
      (node (ref "J4") (pin "3") (pinfunction "3_3") (pintype "bidirectional"))
      (node (ref "J4") (pin "4") (pinfunction "4_4") (pintype "bidirectional"))
      (node (ref "JTAG_OPEN8") (pin "10") (pinfunction "10_10") (pintype "passive"))
      (node (ref "JTAG_OPEN8") (pin "12") (pinfunction "12_12") (pintype "passive"))
      (node (ref "JTAG_OPEN8") (pin "14") (pinfunction "14_14") (pintype "passive"))
      (node (ref "JTAG_OPEN8") (pin "16") (pinfunction "16_16") (pintype "passive"))
      (node (ref "JTAG_OPEN8") (pin "18") (pinfunction "18_18") (pintype "passive"))
      (node (ref "JTAG_OPEN8") (pin "20") (pinfunction "20_20") (pintype "passive"))
      (node (ref "JTAG_OPEN8") (pin "4") (pinfunction "4_4") (pintype "passive"))
      (node (ref "JTAG_OPEN8") (pin "6") (pinfunction "6_6") (pintype "passive"))
      (node (ref "JTAG_OPEN8") (pin "8") (pinfunction "8_8") (pintype "passive"))
      (node (ref "JTAG_SERV") (pin "10") (pinfunction "10_10") (pintype "passive"))
      (node (ref "JTAG_SERV") (pin "12") (pinfunction "12_12") (pintype "passive"))
      (node (ref "JTAG_SERV") (pin "14") (pinfunction "14_14") (pintype "passive"))
      (node (ref "JTAG_SERV") (pin "16") (pinfunction "16_16") (pintype "passive"))
      (node (ref "JTAG_SERV") (pin "18") (pinfunction "18_18") (pintype "passive"))
      (node (ref "JTAG_SERV") (pin "20") (pinfunction "20_20") (pintype "passive"))
      (node (ref "JTAG_SERV") (pin "4") (pinfunction "4_4") (pintype "passive"))
      (node (ref "JTAG_SERV") (pin "6") (pinfunction "6_6") (pintype "passive"))
      (node (ref "JTAG_SERV") (pin "8") (pinfunction "8_8") (pintype "passive"))
      (node (ref "LORA_OPEN8") (pin "P$1") (pinfunction "GND_1_P$1") (pintype "bidirectional"))
      (node (ref "LORA_OPEN8") (pin "P$15") (pinfunction "GND_3_P$15") (pintype "bidirectional"))
      (node (ref "LORA_OPEN8") (pin "P$8") (pinfunction "GND_2_P$8") (pintype "bidirectional"))
      (node (ref "LORA_SERV") (pin "P$1") (pinfunction "GND_1_P$1") (pintype "bidirectional"))
      (node (ref "LORA_SERV") (pin "P$15") (pinfunction "GND_3_P$15") (pintype "bidirectional"))
      (node (ref "LORA_SERV") (pin "P$8") (pinfunction "GND_2_P$8") (pintype "bidirectional"))
      (node (ref "MUX") (pin "2") (pinfunction "2_2") (pintype "passive"))
      (node (ref "Q1") (pin "2") (pinfunction "S_2") (pintype "bidirectional"))
      (node (ref "Q16") (pin "2") (pinfunction "S_2") (pintype "bidirectional"))
      (node (ref "Q17") (pin "2") (pinfunction "S_2") (pintype "bidirectional"))
      (node (ref "Q18") (pin "2") (pinfunction "S_2") (pintype "bidirectional"))
      (node (ref "Q19") (pin "2") (pinfunction "S_2") (pintype "bidirectional"))
      (node (ref "Q2") (pin "2") (pinfunction "S_2") (pintype "bidirectional"))
      (node (ref "Q3") (pin "2") (pinfunction "S_2") (pintype "bidirectional"))
      (node (ref "Q4") (pin "2") (pinfunction "S_2") (pintype "bidirectional"))
      (node (ref "Q5") (pin "2") (pinfunction "S_2") (pintype "bidirectional"))
      (node (ref "R1") (pin "1") (pinfunction "1_1") (pintype "passive"))
      (node (ref "R11") (pin "1") (pinfunction "1_1") (pintype "passive"))
      (node (ref "R12") (pin "1") (pinfunction "1_1") (pintype "passive"))
      (node (ref "R13") (pin "1") (pinfunction "1_1") (pintype "passive"))
      (node (ref "R14") (pin "1") (pinfunction "1_1") (pintype "passive"))
      (node (ref "R16") (pin "1") (pinfunction "1_1") (pintype "passive"))
      (node (ref "R17") (pin "1") (pinfunction "1_1") (pintype "passive"))
      (node (ref "R2") (pin "1") (pinfunction "1_1") (pintype "passive"))
      (node (ref "R21") (pin "1") (pinfunction "1_1") (pintype "passive"))
      (node (ref "R23") (pin "1") (pinfunction "1_1") (pintype "passive"))
      (node (ref "R26") (pin "1") (pinfunction "1_1") (pintype "passive"))
      (node (ref "R30") (pin "1") (pinfunction "1_1") (pintype "passive"))
      (node (ref "R4") (pin "1") (pinfunction "1_1") (pintype "passive"))
      (node (ref "R48") (pin "1") (pinfunction "1_1") (pintype "passive"))
      (node (ref "R5") (pin "1") (pinfunction "1_1") (pintype "passive"))
      (node (ref "R53") (pin "1") (pinfunction "1_1") (pintype "passive"))
      (node (ref "R57") (pin "1") (pinfunction "1_1") (pintype "passive"))
      (node (ref "R63") (pin "1") (pinfunction "1_1") (pintype "passive"))
      (node (ref "R65") (pin "1") (pinfunction "1_1") (pintype "passive"))
      (node (ref "R7") (pin "1") (pinfunction "1_1") (pintype "passive"))
      (node (ref "R78") (pin "1") (pinfunction "1_1") (pintype "passive"))
      (node (ref "R8") (pin "1") (pinfunction "1_1") (pintype "passive"))
      (node (ref "R80") (pin "1") (pinfunction "1_1") (pintype "passive"))
      (node (ref "S1") (pin "3") (pinfunction "ON_2_3") (pintype "bidirectional"))
      (node (ref "S2") (pin "3") (pinfunction "ON_2_3") (pintype "bidirectional"))
      (node (ref "S3") (pin "3") (pinfunction "ON_2_3") (pintype "bidirectional"))
      (node (ref "S4") (pin "3") (pinfunction "ON_2_3") (pintype "bidirectional"))
      (node (ref "S5") (pin "3") (pinfunction "ON_2_3") (pintype "bidirectional"))
      (node (ref "S6") (pin "3") (pinfunction "ON_2_3") (pintype "bidirectional"))
      (node (ref "SPI_OPEN8_2") (pin "10") (pinfunction "10_10") (pintype "passive"))
      (node (ref "SPI_SERV_1") (pin "10") (pinfunction "10_10") (pintype "passive"))
      (node (ref "U$1") (pin "3") (pinfunction "3_3") (pintype "bidirectional"))
      (node (ref "U$1") (pin "37") (pinfunction "37_37") (pintype "bidirectional"))
      (node (ref "U$2") (pin "24") (pinfunction "24_24") (pintype "bidirectional"))
      (node (ref "U$2") (pin "26") (pinfunction "26_26") (pintype "bidirectional"))
      (node (ref "U$2") (pin "3") (pinfunction "3_3") (pintype "bidirectional"))
      (node (ref "U$2") (pin "37") (pinfunction "37_37") (pintype "bidirectional"))
      (node (ref "U$3") (pin "24") (pinfunction "24_24") (pintype "bidirectional"))
      (node (ref "U$3") (pin "3") (pinfunction "3_3") (pintype "bidirectional"))
      (node (ref "U$3") (pin "37") (pinfunction "37_37") (pintype "bidirectional"))
      (node (ref "U$4") (pin "3") (pinfunction "3_3") (pintype "bidirectional"))
      (node (ref "U$4") (pin "37") (pinfunction "37_37") (pintype "bidirectional"))
      (node (ref "U1") (pin "2") (pinfunction "GND_2") (pintype "power_in"))
      (node (ref "U1") (pin "3") (pinfunction "~{EN}_3") (pintype "input"))
      (node (ref "U2") (pin "2") (pinfunction "GND_2") (pintype "power_in"))
      (node (ref "U2") (pin "3") (pinfunction "~{EN}_3") (pintype "input"))
      (node (ref "U3") (pin "2") (pinfunction "GND_2") (pintype "power_in"))
      (node (ref "U3") (pin "3") (pinfunction "~{EN}_3") (pintype "input"))
      (node (ref "U4") (pin "2") (pinfunction "GND_2") (pintype "power_in"))
      (node (ref "U4") (pin "3") (pinfunction "~{EN}_3") (pintype "input"))
      (node (ref "U5") (pin "2") (pinfunction "GND_2") (pintype "power_in"))
      (node (ref "U5") (pin "3") (pinfunction "~{EN}_3") (pintype "input"))
      (node (ref "U6") (pin "2") (pinfunction "GND_2") (pintype "power_in"))
      (node (ref "U6") (pin "3") (pinfunction "~{EN}_3") (pintype "input"))
      (node (ref "USB-UART_OPEN8_1") (pin "1") (pinfunction "1_1") (pintype "passive"))
      (node (ref "USB-UART_SERV_1") (pin "1") (pinfunction "1_1") (pintype "passive"))
    )
    (net (code "145") (name "IN_3V3") (class "Default")
      (node (ref "C3") (pin "1") (pinfunction "1_1") (pintype "passive"))
      (node (ref "IN_3V3") (pin "2") (pinfunction "2_2") (pintype "passive"))
      (node (ref "U2") (pin "1") (pinfunction "IN_1") (pintype "input"))
    )
    (net (code "146") (name "IN_OPEN8") (class "Default")
      (node (ref "C6") (pin "1") (pinfunction "1_1") (pintype "passive"))
      (node (ref "IN_OPEN8") (pin "2") (pinfunction "2_2") (pintype "passive"))
      (node (ref "U4") (pin "1") (pinfunction "IN_1") (pintype "input"))
    )
    (net (code "147") (name "IN_RAM") (class "Default")
      (node (ref "C9") (pin "1") (pinfunction "1_1") (pintype "passive"))
      (node (ref "IN_RAM") (pin "2") (pinfunction "2_2") (pintype "passive"))
      (node (ref "U5") (pin "1") (pinfunction "IN_1") (pintype "input"))
    )
    (net (code "148") (name "IN_SERV") (class "Default")
      (node (ref "C1") (pin "1") (pinfunction "1_1") (pintype "passive"))
      (node (ref "IN_SERV") (pin "2") (pinfunction "2_2") (pintype "passive"))
      (node (ref "U1") (pin "1") (pinfunction "IN_1") (pintype "input"))
    )
    (net (code "149") (name "IN_VDD") (class "Default")
      (node (ref "C5") (pin "1") (pinfunction "1_1") (pintype "passive"))
      (node (ref "IN_VDD") (pin "2") (pinfunction "2_2") (pintype "passive"))
      (node (ref "U3") (pin "1") (pinfunction "IN_1") (pintype "input"))
    )
    (net (code "150") (name "IN_VDDO") (class "Default")
      (node (ref "C11") (pin "1") (pinfunction "1_1") (pintype "passive"))
      (node (ref "IN_VDDO") (pin "2") (pinfunction "2_2") (pintype "passive"))
      (node (ref "U6") (pin "1") (pinfunction "IN_1") (pintype "input"))
    )
    (net (code "151") (name "Net-(C2-Pad2)") (class "Default")
      (node (ref "C2") (pin "2") (pinfunction "2_2") (pintype "passive"))
      (node (ref "R2") (pin "2") (pinfunction "2_2") (pintype "passive"))
    )
    (net (code "152") (name "Net-(C4-Pad2)") (class "Default")
      (node (ref "C4") (pin "2") (pinfunction "2_2") (pintype "passive"))
      (node (ref "R8") (pin "2") (pinfunction "2_2") (pintype "passive"))
    )
    (net (code "153") (name "Net-(C7-Pad2)") (class "Default")
      (node (ref "C7") (pin "2") (pinfunction "2_2") (pintype "passive"))
      (node (ref "R17") (pin "2") (pinfunction "2_2") (pintype "passive"))
    )
    (net (code "154") (name "Net-(C8-Pad2)") (class "Default")
      (node (ref "C8") (pin "2") (pinfunction "2_2") (pintype "passive"))
      (node (ref "R14") (pin "2") (pinfunction "2_2") (pintype "passive"))
    )
    (net (code "155") (name "Net-(C10-Pad2)") (class "Default")
      (node (ref "C10") (pin "2") (pinfunction "2_2") (pintype "passive"))
      (node (ref "R5") (pin "2") (pinfunction "2_2") (pintype "passive"))
    )
    (net (code "156") (name "Net-(C12-Pad2)") (class "Default")
      (node (ref "C12") (pin "2") (pinfunction "2_2") (pintype "passive"))
      (node (ref "R12") (pin "2") (pinfunction "2_2") (pintype "passive"))
    )
    (net (code "157") (name "Net-(D1-PadA)") (class "Default")
      (node (ref "D1") (pin "A") (pinfunction "A_A") (pintype "passive"))
      (node (ref "R20") (pin "1") (pinfunction "1_1") (pintype "passive"))
    )
    (net (code "158") (name "Net-(D2-PadA)") (class "Default")
      (node (ref "D2") (pin "A") (pinfunction "A_A") (pintype "passive"))
      (node (ref "R22") (pin "1") (pinfunction "1_1") (pintype "passive"))
    )
    (net (code "159") (name "Net-(D3-PadA)") (class "Default")
      (node (ref "D3") (pin "A") (pinfunction "A_A") (pintype "passive"))
      (node (ref "R52") (pin "1") (pinfunction "1_1") (pintype "passive"))
    )
    (net (code "160") (name "Net-(D4-PadA)") (class "Default")
      (node (ref "D4") (pin "A") (pinfunction "A_A") (pintype "passive"))
      (node (ref "R40") (pin "1") (pinfunction "1_1") (pintype "passive"))
    )
    (net (code "161") (name "Net-(D5-PadA)") (class "Default")
      (node (ref "D5") (pin "A") (pinfunction "A_A") (pintype "passive"))
      (node (ref "R56") (pin "1") (pinfunction "1_1") (pintype "passive"))
    )
    (net (code "162") (name "Net-(D19-PadA)") (class "Default")
      (node (ref "D19") (pin "A") (pinfunction "A_A") (pintype "passive"))
      (node (ref "R62") (pin "1") (pinfunction "1_1") (pintype "passive"))
    )
    (net (code "163") (name "Net-(D20-PadA)") (class "Default")
      (node (ref "D20") (pin "A") (pinfunction "A_A") (pintype "passive"))
      (node (ref "R64") (pin "1") (pinfunction "1_1") (pintype "passive"))
    )
    (net (code "164") (name "Net-(D21-PadA)") (class "Default")
      (node (ref "D21") (pin "A") (pinfunction "A_A") (pintype "passive"))
      (node (ref "R77") (pin "1") (pinfunction "1_1") (pintype "passive"))
    )
    (net (code "165") (name "Net-(D22-PadA)") (class "Default")
      (node (ref "D22") (pin "A") (pinfunction "A_A") (pintype "passive"))
      (node (ref "R79") (pin "1") (pinfunction "1_1") (pintype "passive"))
    )
    (net (code "166") (name "Net-(IC1-A)") (class "Default")
      (node (ref "C25") (pin "1") (pinfunction "1_1") (pintype "passive"))
      (node (ref "IC1") (pin "2") (pinfunction "A_2") (pintype "bidirectional"))
      (node (ref "R24") (pin "1") (pinfunction "1_1") (pintype "passive"))
      (node (ref "Y2") (pin "2") (pinfunction "CRYSTAL_2_2") (pintype "bidirectional"))
    )
    (net (code "167") (name "Net-(IC1-GND)") (class "Default")
      (node (ref "IC1") (pin "3") (pinfunction "GND_3") (pintype "power_in"))
      (node (ref "R26") (pin "2") (pinfunction "2_2") (pintype "passive"))
    )
    (net (code "168") (name "Net-(IC1-VCC)") (class "Default")
      (node (ref "IC1") (pin "5") (pinfunction "VCC_5") (pintype "power_in"))
      (node (ref "R25") (pin "1") (pinfunction "1_1") (pintype "passive"))
    )
    (net (code "169") (name "Net-(IC2-A)") (class "Default")
      (node (ref "C27") (pin "1") (pinfunction "1_1") (pintype "passive"))
      (node (ref "IC2") (pin "2") (pinfunction "A_2") (pintype "bidirectional"))
      (node (ref "R28") (pin "1") (pinfunction "1_1") (pintype "passive"))
      (node (ref "Y3") (pin "2") (pinfunction "CRYSTAL_2_2") (pintype "bidirectional"))
    )
    (net (code "170") (name "Net-(IC2-GND)") (class "Default")
      (node (ref "IC2") (pin "3") (pinfunction "GND_3") (pintype "power_in"))
      (node (ref "R30") (pin "2") (pinfunction "2_2") (pintype "passive"))
    )
    (net (code "171") (name "Net-(IC2-VCC)") (class "Default")
      (node (ref "IC2") (pin "5") (pinfunction "VCC_5") (pintype "power_in"))
      (node (ref "R29") (pin "1") (pinfunction "1_1") (pintype "passive"))
    )
    (net (code "172") (name "Net-(IC3-A2)") (class "Default")
      (node (ref "IC3") (pin "3") (pinfunction "A2_3") (pintype "bidirectional"))
      (node (ref "OPEN8_LORA") (pin "2") (pinfunction "2_2") (pintype "passive"))
    )
    (net (code "173") (name "Net-(IC3-A3)") (class "Default")
      (node (ref "IC3") (pin "4") (pinfunction "A3_4") (pintype "bidirectional"))
      (node (ref "OPEN8_LORA") (pin "4") (pinfunction "4_4") (pintype "passive"))
    )
    (net (code "174") (name "Net-(IC3-A4)") (class "Default")
      (node (ref "IC3") (pin "5") (pinfunction "A4_5") (pintype "bidirectional"))
      (node (ref "OPEN8_LORA") (pin "6") (pinfunction "6_6") (pintype "passive"))
    )
    (net (code "175") (name "Net-(IC3-A5)") (class "Default")
      (node (ref "IC3") (pin "6") (pinfunction "A5_6") (pintype "bidirectional"))
      (node (ref "OPEN8_LORA") (pin "8") (pinfunction "8_8") (pintype "passive"))
    )
    (net (code "176") (name "Net-(IC4-A2)") (class "Default")
      (node (ref "IC4") (pin "3") (pinfunction "A2_3") (pintype "bidirectional"))
      (node (ref "OPEN8_FLASH") (pin "2") (pinfunction "2_2") (pintype "passive"))
    )
    (net (code "177") (name "Net-(IC4-A3)") (class "Default")
      (node (ref "IC4") (pin "4") (pinfunction "A3_4") (pintype "bidirectional"))
      (node (ref "OPEN8_FLASH") (pin "4") (pinfunction "4_4") (pintype "passive"))
    )
    (net (code "178") (name "Net-(IC4-A4)") (class "Default")
      (node (ref "IC4") (pin "5") (pinfunction "A4_5") (pintype "bidirectional"))
      (node (ref "OPEN8_FLASH") (pin "6") (pinfunction "6_6") (pintype "passive"))
    )
    (net (code "179") (name "Net-(IC4-A5)") (class "Default")
      (node (ref "IC4") (pin "6") (pinfunction "A5_6") (pintype "bidirectional"))
      (node (ref "OPEN8_FLASH") (pin "8") (pinfunction "8_8") (pintype "passive"))
    )
    (net (code "180") (name "Net-(IC5-A2)") (class "Default")
      (node (ref "IC5") (pin "3") (pinfunction "A2_3") (pintype "bidirectional"))
      (node (ref "SERV_LORA") (pin "2") (pinfunction "2_2") (pintype "passive"))
    )
    (net (code "181") (name "Net-(IC5-A3)") (class "Default")
      (node (ref "IC5") (pin "4") (pinfunction "A3_4") (pintype "bidirectional"))
      (node (ref "SERV_LORA") (pin "4") (pinfunction "4_4") (pintype "passive"))
    )
    (net (code "182") (name "Net-(IC5-A4)") (class "Default")
      (node (ref "IC5") (pin "5") (pinfunction "A4_5") (pintype "bidirectional"))
      (node (ref "SERV_LORA") (pin "6") (pinfunction "6_6") (pintype "passive"))
    )
    (net (code "183") (name "Net-(IC5-A5)") (class "Default")
      (node (ref "IC5") (pin "6") (pinfunction "A5_6") (pintype "bidirectional"))
      (node (ref "SERV_LORA") (pin "8") (pinfunction "8_8") (pintype "passive"))
    )
    (net (code "184") (name "Net-(IC6-A1)") (class "Default")
      (node (ref "IC6") (pin "1") (pinfunction "A1_1") (pintype "bidirectional"))
      (node (ref "OPEN8_JTAG") (pin "2") (pinfunction "2_2") (pintype "passive"))
    )
    (net (code "185") (name "Net-(IC6-A2)") (class "Default")
      (node (ref "IC6") (pin "3") (pinfunction "A2_3") (pintype "bidirectional"))
      (node (ref "OPEN8_JTAG") (pin "4") (pinfunction "4_4") (pintype "passive"))
    )
    (net (code "186") (name "Net-(IC6-A3)") (class "Default")
      (node (ref "IC6") (pin "4") (pinfunction "A3_4") (pintype "bidirectional"))
      (node (ref "OPEN8_JTAG") (pin "6") (pinfunction "6_6") (pintype "passive"))
    )
    (net (code "187") (name "Net-(IC6-A4)") (class "Default")
      (node (ref "IC6") (pin "5") (pinfunction "A4_5") (pintype "bidirectional"))
      (node (ref "OPEN8_JTAG") (pin "8") (pinfunction "8_8") (pintype "passive"))
    )
    (net (code "188") (name "Net-(IC6-A5)") (class "Default")
      (node (ref "IC6") (pin "6") (pinfunction "A5_6") (pintype "bidirectional"))
      (node (ref "OPEN8_JTAG") (pin "10") (pinfunction "10_10") (pintype "passive"))
    )
    (net (code "189") (name "Net-(IC6-A6)") (class "Default")
      (node (ref "IC6") (pin "7") (pinfunction "A6_7") (pintype "bidirectional"))
      (node (ref "OPEN8_UART") (pin "2") (pinfunction "2_2") (pintype "passive"))
    )
    (net (code "190") (name "Net-(IC6-A7)") (class "Default")
      (node (ref "IC6") (pin "8") (pinfunction "A7_8") (pintype "bidirectional"))
      (node (ref "OPEN8_UART") (pin "4") (pinfunction "4_4") (pintype "passive"))
    )
    (net (code "191") (name "Net-(IC7-A2)") (class "Default")
      (node (ref "IC7") (pin "3") (pinfunction "A2_3") (pintype "bidirectional"))
      (node (ref "SERV_FLASH") (pin "2") (pinfunction "2_2") (pintype "passive"))
    )
    (net (code "192") (name "Net-(IC7-A3)") (class "Default")
      (node (ref "IC7") (pin "4") (pinfunction "A3_4") (pintype "bidirectional"))
      (node (ref "SERV_FLASH") (pin "4") (pinfunction "4_4") (pintype "passive"))
    )
    (net (code "193") (name "Net-(IC7-A4)") (class "Default")
      (node (ref "IC7") (pin "5") (pinfunction "A4_5") (pintype "bidirectional"))
      (node (ref "SERV_FLASH") (pin "6") (pinfunction "6_6") (pintype "passive"))
    )
    (net (code "194") (name "Net-(IC7-A5)") (class "Default")
      (node (ref "IC7") (pin "6") (pinfunction "A5_6") (pintype "bidirectional"))
      (node (ref "SERV_FLASH") (pin "8") (pinfunction "8_8") (pintype "passive"))
    )
    (net (code "195") (name "Net-(IC8-A2)") (class "Default")
      (node (ref "IC8") (pin "3") (pinfunction "A2_3") (pintype "bidirectional"))
      (node (ref "SERV_SPI") (pin "2") (pinfunction "2_2") (pintype "passive"))
    )
    (net (code "196") (name "Net-(IC8-A3)") (class "Default")
      (node (ref "IC8") (pin "4") (pinfunction "A3_4") (pintype "bidirectional"))
      (node (ref "SERV_SPI") (pin "4") (pinfunction "4_4") (pintype "passive"))
    )
    (net (code "197") (name "Net-(IC8-A4)") (class "Default")
      (node (ref "IC8") (pin "5") (pinfunction "A4_5") (pintype "bidirectional"))
      (node (ref "SERV_SPI") (pin "6") (pinfunction "6_6") (pintype "passive"))
    )
    (net (code "198") (name "Net-(IC8-A5)") (class "Default")
      (node (ref "IC8") (pin "6") (pinfunction "A5_6") (pintype "bidirectional"))
      (node (ref "SERV_SPI") (pin "8") (pinfunction "8_8") (pintype "passive"))
    )
    (net (code "199") (name "Net-(IC10-A1)") (class "Default")
      (node (ref "IC10") (pin "1") (pinfunction "A1_1") (pintype "bidirectional"))
      (node (ref "SERV_JTAG") (pin "2") (pinfunction "2_2") (pintype "passive"))
    )
    (net (code "200") (name "Net-(IC10-A2)") (class "Default")
      (node (ref "IC10") (pin "3") (pinfunction "A2_3") (pintype "bidirectional"))
      (node (ref "SERV_JTAG") (pin "4") (pinfunction "4_4") (pintype "passive"))
    )
    (net (code "201") (name "Net-(IC10-A3)") (class "Default")
      (node (ref "IC10") (pin "4") (pinfunction "A3_4") (pintype "bidirectional"))
      (node (ref "SERV_JTAG") (pin "6") (pinfunction "6_6") (pintype "passive"))
    )
    (net (code "202") (name "Net-(IC10-A4)") (class "Default")
      (node (ref "IC10") (pin "5") (pinfunction "A4_5") (pintype "bidirectional"))
      (node (ref "SERV_JTAG") (pin "8") (pinfunction "8_8") (pintype "passive"))
    )
    (net (code "203") (name "Net-(IC10-A5)") (class "Default")
      (node (ref "IC10") (pin "6") (pinfunction "A5_6") (pintype "bidirectional"))
      (node (ref "SERV_JTAG") (pin "10") (pinfunction "10_10") (pintype "passive"))
    )
    (net (code "204") (name "Net-(IC10-A6)") (class "Default")
      (node (ref "IC10") (pin "7") (pinfunction "A6_7") (pintype "bidirectional"))
      (node (ref "SERV_UART") (pin "2") (pinfunction "2_2") (pintype "passive"))
    )
    (net (code "205") (name "Net-(IC10-A7)") (class "Default")
      (node (ref "IC10") (pin "8") (pinfunction "A7_8") (pintype "bidirectional"))
      (node (ref "SERV_UART") (pin "4") (pinfunction "4_4") (pintype "passive"))
    )
    (net (code "206") (name "Net-(IC11-A3)") (class "Default")
      (node (ref "IC11") (pin "4") (pinfunction "A3_4") (pintype "bidirectional"))
      (node (ref "OPEN8_SPI") (pin "2") (pinfunction "2_2") (pintype "passive"))
    )
    (net (code "207") (name "Net-(IC11-A4)") (class "Default")
      (node (ref "IC11") (pin "5") (pinfunction "A4_5") (pintype "bidirectional"))
      (node (ref "OPEN8_SPI") (pin "4") (pinfunction "4_4") (pintype "passive"))
    )
    (net (code "208") (name "Net-(IC11-A5)") (class "Default")
      (node (ref "IC11") (pin "6") (pinfunction "A5_6") (pintype "bidirectional"))
      (node (ref "OPEN8_SPI") (pin "6") (pinfunction "6_6") (pintype "passive"))
    )
    (net (code "209") (name "Net-(IC11-A6)") (class "Default")
      (node (ref "IC11") (pin "7") (pinfunction "A6_7") (pintype "bidirectional"))
      (node (ref "OPEN8_SPI") (pin "8") (pinfunction "8_8") (pintype "passive"))
    )
    (net (code "210") (name "Net-(Q1-D)") (class "Default")
      (node (ref "D1") (pin "C") (pinfunction "C_C") (pintype "passive"))
      (node (ref "Q1") (pin "3") (pinfunction "D_3") (pintype "bidirectional"))
    )
    (net (code "211") (name "Net-(Q2-D)") (class "Default")
      (node (ref "D2") (pin "C") (pinfunction "C_C") (pintype "passive"))
      (node (ref "Q2") (pin "3") (pinfunction "D_3") (pintype "bidirectional"))
    )
    (net (code "212") (name "Net-(Q3-D)") (class "Default")
      (node (ref "D4") (pin "C") (pinfunction "C_C") (pintype "passive"))
      (node (ref "Q3") (pin "3") (pinfunction "D_3") (pintype "bidirectional"))
    )
    (net (code "213") (name "Net-(Q4-D)") (class "Default")
      (node (ref "D3") (pin "C") (pinfunction "C_C") (pintype "passive"))
      (node (ref "Q4") (pin "3") (pinfunction "D_3") (pintype "bidirectional"))
    )
    (net (code "214") (name "Net-(Q5-D)") (class "Default")
      (node (ref "D5") (pin "C") (pinfunction "C_C") (pintype "passive"))
      (node (ref "Q5") (pin "3") (pinfunction "D_3") (pintype "bidirectional"))
    )
    (net (code "215") (name "Net-(Q16-D)") (class "Default")
      (node (ref "D19") (pin "C") (pinfunction "C_C") (pintype "passive"))
      (node (ref "Q16") (pin "3") (pinfunction "D_3") (pintype "bidirectional"))
    )
    (net (code "216") (name "Net-(Q17-D)") (class "Default")
      (node (ref "D20") (pin "C") (pinfunction "C_C") (pintype "passive"))
      (node (ref "Q17") (pin "3") (pinfunction "D_3") (pintype "bidirectional"))
    )
    (net (code "217") (name "Net-(Q18-D)") (class "Default")
      (node (ref "D21") (pin "C") (pinfunction "C_C") (pintype "passive"))
      (node (ref "Q18") (pin "3") (pinfunction "D_3") (pintype "bidirectional"))
    )
    (net (code "218") (name "Net-(Q19-D)") (class "Default")
      (node (ref "D22") (pin "C") (pinfunction "C_C") (pintype "passive"))
      (node (ref "Q19") (pin "3") (pinfunction "D_3") (pintype "bidirectional"))
    )
    (net (code "219") (name "Net-(R10-Pad2)") (class "Default")
      (node (ref "R10") (pin "2") (pinfunction "2_2") (pintype "passive"))
      (node (ref "R9") (pin "1") (pinfunction "1_1") (pintype "passive"))
    )
    (net (code "220") (name "Net-(S1-COM)") (class "Default")
      (node (ref "NRESET_OPEN8") (pin "2") (pinfunction "2_2") (pintype "passive"))
      (node (ref "S1") (pin "2") (pinfunction "COM_2") (pintype "bidirectional"))
    )
    (net (code "221") (name "Net-(S1-ON_1)") (class "Default")
      (node (ref "R32") (pin "1") (pinfunction "1_1") (pintype "passive"))
      (node (ref "S1") (pin "1") (pinfunction "ON_1_1") (pintype "bidirectional"))
    )
    (net (code "222") (name "Net-(S2-COM)") (class "Default")
      (node (ref "NRESET_SERV") (pin "2") (pinfunction "2_2") (pintype "passive"))
      (node (ref "S2") (pin "2") (pinfunction "COM_2") (pintype "bidirectional"))
    )
    (net (code "223") (name "Net-(S2-ON_1)") (class "Default")
      (node (ref "R33") (pin "1") (pinfunction "1_1") (pintype "passive"))
      (node (ref "S2") (pin "1") (pinfunction "ON_1_1") (pintype "bidirectional"))
    )
    (net (code "224") (name "Net-(S3-COM)") (class "Default")
      (node (ref "OPEN8_SW") (pin "2") (pinfunction "2_2") (pintype "passive"))
      (node (ref "S3") (pin "2") (pinfunction "COM_2") (pintype "bidirectional"))
    )
    (net (code "225") (name "Net-(S3-ON_1)") (class "Default")
      (node (ref "R39") (pin "1") (pinfunction "1_1") (pintype "passive"))
      (node (ref "S3") (pin "1") (pinfunction "ON_1_1") (pintype "bidirectional"))
    )
    (net (code "226") (name "Net-(S4-COM)") (class "Default")
      (node (ref "OPEN8_SW") (pin "4") (pinfunction "4_4") (pintype "passive"))
      (node (ref "S4") (pin "2") (pinfunction "COM_2") (pintype "bidirectional"))
    )
    (net (code "227") (name "Net-(S4-ON_1)") (class "Default")
      (node (ref "R41") (pin "1") (pinfunction "1_1") (pintype "passive"))
      (node (ref "S4") (pin "1") (pinfunction "ON_1_1") (pintype "bidirectional"))
    )
    (net (code "228") (name "Net-(S5-COM)") (class "Default")
      (node (ref "S5") (pin "2") (pinfunction "COM_2") (pintype "bidirectional"))
      (node (ref "SERV_SW") (pin "2") (pinfunction "2_2") (pintype "passive"))
    )
    (net (code "229") (name "Net-(S5-ON_1)") (class "Default")
      (node (ref "R54") (pin "1") (pinfunction "1_1") (pintype "passive"))
      (node (ref "S5") (pin "1") (pinfunction "ON_1_1") (pintype "bidirectional"))
    )
    (net (code "230") (name "Net-(S6-COM)") (class "Default")
      (node (ref "S6") (pin "2") (pinfunction "COM_2") (pintype "bidirectional"))
      (node (ref "SERV_SW") (pin "4") (pinfunction "4_4") (pintype "passive"))
    )
    (net (code "231") (name "Net-(S6-ON_1)") (class "Default")
      (node (ref "R55") (pin "1") (pinfunction "1_1") (pintype "passive"))
      (node (ref "S6") (pin "1") (pinfunction "ON_1_1") (pintype "bidirectional"))
    )
    (net (code "232") (name "Net-(U1-FB)") (class "Default")
      (node (ref "R1") (pin "2") (pinfunction "2_2") (pintype "passive"))
      (node (ref "R3") (pin "1") (pinfunction "1_1") (pintype "passive"))
      (node (ref "U1") (pin "4") (pinfunction "FB_4") (pintype "input"))
    )
    (net (code "233") (name "Net-(U2-FB)") (class "Default")
      (node (ref "R10") (pin "1") (pinfunction "1_1") (pintype "passive"))
      (node (ref "R7") (pin "2") (pinfunction "2_2") (pintype "passive"))
      (node (ref "U2") (pin "4") (pinfunction "FB_4") (pintype "input"))
    )
    (net (code "234") (name "Net-(U3-FB)") (class "Default")
      (node (ref "R13") (pin "2") (pinfunction "2_2") (pintype "passive"))
      (node (ref "R19") (pin "1") (pinfunction "1_1") (pintype "passive"))
      (node (ref "U3") (pin "4") (pinfunction "FB_4") (pintype "input"))
    )
    (net (code "235") (name "Net-(U4-FB)") (class "Default")
      (node (ref "R15") (pin "1") (pinfunction "1_1") (pintype "passive"))
      (node (ref "R16") (pin "2") (pinfunction "2_2") (pintype "passive"))
      (node (ref "U4") (pin "4") (pinfunction "FB_4") (pintype "input"))
    )
    (net (code "236") (name "Net-(U5-FB)") (class "Default")
      (node (ref "R4") (pin "2") (pinfunction "2_2") (pintype "passive"))
      (node (ref "R6") (pin "1") (pinfunction "1_1") (pintype "passive"))
      (node (ref "U5") (pin "4") (pinfunction "FB_4") (pintype "input"))
    )
    (net (code "237") (name "Net-(U6-FB)") (class "Default")
      (node (ref "R11") (pin "2") (pinfunction "2_2") (pintype "passive"))
      (node (ref "R18") (pin "1") (pinfunction "1_1") (pintype "passive"))
      (node (ref "U6") (pin "4") (pinfunction "FB_4") (pintype "input"))
    )
    (net (code "238") (name "Net-(Y2-CRYSTAL_1)") (class "Default")
      (node (ref "C26") (pin "2") (pinfunction "2_2") (pintype "passive"))
      (node (ref "R27") (pin "1") (pinfunction "1_1") (pintype "passive"))
      (node (ref "Y2") (pin "1") (pinfunction "CRYSTAL_1_1") (pintype "bidirectional"))
    )
    (net (code "239") (name "Net-(Y3-CRYSTAL_1)") (class "Default")
      (node (ref "C28") (pin "2") (pinfunction "2_2") (pintype "passive"))
      (node (ref "R31") (pin "1") (pinfunction "1_1") (pintype "passive"))
      (node (ref "Y3") (pin "1") (pinfunction "CRYSTAL_1_1") (pintype "bidirectional"))
    )
    (net (code "240") (name "OPEN8_FLASH_CIPO") (class "Default")
      (node (ref "FLASH_OPEN8") (pin "8") (pinfunction "8_8") (pintype "passive"))
      (node (ref "IC4") (pin "18") (pinfunction "B2_18") (pintype "bidirectional"))
    )
    (net (code "241") (name "OPEN8_FLASH_COPI") (class "Default")
      (node (ref "FLASH_OPEN8") (pin "10") (pinfunction "10_10") (pintype "passive"))
      (node (ref "IC4") (pin "16") (pinfunction "B4_16") (pintype "bidirectional"))
    )
    (net (code "242") (name "OPEN8_FLASH_CS") (class "Default")
      (node (ref "FLASH_OPEN8") (pin "12") (pinfunction "12_12") (pintype "passive"))
      (node (ref "IC4") (pin "17") (pinfunction "B3_17") (pintype "bidirectional"))
    )
    (net (code "243") (name "OPEN8_FLASH_SCK") (class "Default")
      (node (ref "FLASH_OPEN8") (pin "6") (pinfunction "6_6") (pintype "passive"))
      (node (ref "IC4") (pin "15") (pinfunction "B5_15") (pintype "bidirectional"))
    )
    (net (code "244") (name "OPEN8_JTAG_TCK") (class "Default")
      (node (ref "IC6") (pin "16") (pinfunction "B4_16") (pintype "bidirectional"))
      (node (ref "JTAG_OPEN8") (pin "9") (pinfunction "9_9") (pintype "passive"))
    )
    (net (code "245") (name "OPEN8_JTAG_TDI") (class "Default")
      (node (ref "IC6") (pin "20") (pinfunction "B1_20") (pintype "bidirectional"))
      (node (ref "JTAG_OPEN8") (pin "5") (pinfunction "5_5") (pintype "passive"))
    )
    (net (code "246") (name "OPEN8_JTAG_TDO") (class "Default")
      (node (ref "IC6") (pin "18") (pinfunction "B2_18") (pintype "bidirectional"))
      (node (ref "JTAG_OPEN8") (pin "13") (pinfunction "13_13") (pintype "passive"))
    )
    (net (code "247") (name "OPEN8_JTAG_TMS") (class "Default")
      (node (ref "IC6") (pin "15") (pinfunction "B5_15") (pintype "bidirectional"))
      (node (ref "JTAG_OPEN8") (pin "7") (pinfunction "7_7") (pintype "passive"))
    )
    (net (code "248") (name "OPEN8_JTAG_TRST") (class "Default")
      (node (ref "IC6") (pin "17") (pinfunction "B3_17") (pintype "bidirectional"))
      (node (ref "JTAG_OPEN8") (pin "3") (pinfunction "3_3") (pintype "passive"))
    )
    (net (code "249") (name "OPEN8_LED") (class "Default")
      (node (ref "OPEN8_LED") (pin "2") (pinfunction "2_2") (pintype "passive"))
      (node (ref "Q3") (pin "1") (pinfunction "G_1") (pintype "bidirectional"))
      (node (ref "R48") (pin "2") (pinfunction "2_2") (pintype "passive"))
    )
    (net (code "250") (name "OPEN8_LORA_CS") (class "Default")
      (node (ref "IC3") (pin "17") (pinfunction "B3_17") (pintype "bidirectional"))
      (node (ref "LORA_OPEN8") (pin "P$5") (pinfunction "NSS_P$5") (pintype "bidirectional"))
    )
    (net (code "251") (name "OPEN8_LORA_MISO") (class "Default")
      (node (ref "IC3") (pin "15") (pinfunction "B5_15") (pintype "bidirectional"))
      (node (ref "LORA_OPEN8") (pin "P$2") (pinfunction "MISO_P$2") (pintype "bidirectional"))
    )
    (net (code "252") (name "OPEN8_LORA_MOSI") (class "Default")
      (node (ref "IC3") (pin "16") (pinfunction "B4_16") (pintype "bidirectional"))
      (node (ref "LORA_OPEN8") (pin "P$3") (pinfunction "MOSI_P$3") (pintype "bidirectional"))
    )
    (net (code "253") (name "OPEN8_LORA_SCK") (class "Default")
      (node (ref "IC3") (pin "18") (pinfunction "B2_18") (pintype "bidirectional"))
      (node (ref "LORA_OPEN8") (pin "P$4") (pinfunction "SCK_P$4") (pintype "bidirectional"))
    )
    (net (code "254") (name "OPEN8_PROG_CS") (class "Default")
      (node (ref "IC11") (pin "16") (pinfunction "B4_16") (pintype "bidirectional"))
      (node (ref "SPI_OPEN8_2") (pin "4") (pinfunction "4_4") (pintype "passive"))
    )
    (net (code "255") (name "OPEN8_PROG_MISO") (class "Default")
      (node (ref "IC11") (pin "14") (pinfunction "B6_14") (pintype "bidirectional"))
      (node (ref "SPI_OPEN8_2") (pin "3") (pinfunction "3_3") (pintype "passive"))
    )
    (net (code "256") (name "OPEN8_PROG_MOSI") (class "Default")
      (node (ref "IC11") (pin "15") (pinfunction "B5_15") (pintype "bidirectional"))
      (node (ref "SPI_OPEN8_2") (pin "2") (pinfunction "2_2") (pintype "passive"))
    )
    (net (code "257") (name "OPEN8_PROG_SCK") (class "Default")
      (node (ref "IC11") (pin "17") (pinfunction "B3_17") (pintype "bidirectional"))
      (node (ref "SPI_OPEN8_2") (pin "1") (pinfunction "1_1") (pintype "passive"))
    )
    (net (code "258") (name "OPEN8_UART_RX") (class "Default")
      (node (ref "IC6") (pin "13") (pinfunction "B7_13") (pintype "bidirectional"))
      (node (ref "USB-UART_OPEN8_1") (pin "2") (pinfunction "2_2") (pintype "passive"))
    )
    (net (code "259") (name "OPEN8_UART_TX") (class "Default")
      (node (ref "IC6") (pin "14") (pinfunction "B6_14") (pintype "bidirectional"))
      (node (ref "USB-UART_OPEN8_1") (pin "4") (pinfunction "4_4") (pintype "passive"))
    )
    (net (code "260") (name "OUT_3V3") (class "Default")
      (node (ref "C4") (pin "1") (pinfunction "1_1") (pintype "passive"))
      (node (ref "POWER") (pin "1") (pinfunction "1_1") (pintype "passive"))
      (node (ref "R9") (pin "2") (pinfunction "2_2") (pintype "passive"))
      (node (ref "U2") (pin "5") (pinfunction "OUT_5") (pintype "output"))
    )
    (net (code "261") (name "OUT_OPEN8") (class "Default")
      (node (ref "C7") (pin "1") (pinfunction "1_1") (pintype "passive"))
      (node (ref "POWER") (pin "7") (pinfunction "7_7") (pintype "passive"))
      (node (ref "R15") (pin "2") (pinfunction "2_2") (pintype "passive"))
      (node (ref "U4") (pin "5") (pinfunction "OUT_5") (pintype "output"))
    )
    (net (code "262") (name "OUT_RAM") (class "Default")
      (node (ref "C10") (pin "1") (pinfunction "1_1") (pintype "passive"))
      (node (ref "POWER") (pin "11") (pinfunction "11_11") (pintype "passive"))
      (node (ref "R6") (pin "2") (pinfunction "2_2") (pintype "passive"))
      (node (ref "U5") (pin "5") (pinfunction "OUT_5") (pintype "output"))
    )
    (net (code "263") (name "OUT_SERV") (class "Default")
      (node (ref "C2") (pin "1") (pinfunction "1_1") (pintype "passive"))
      (node (ref "POWER") (pin "9") (pinfunction "9_9") (pintype "passive"))
      (node (ref "R3") (pin "2") (pinfunction "2_2") (pintype "passive"))
      (node (ref "U1") (pin "5") (pinfunction "OUT_5") (pintype "output"))
    )
    (net (code "264") (name "OUT_VDD") (class "Default")
      (node (ref "C8") (pin "1") (pinfunction "1_1") (pintype "passive"))
      (node (ref "POWER") (pin "5") (pinfunction "5_5") (pintype "passive"))
      (node (ref "R19") (pin "2") (pinfunction "2_2") (pintype "passive"))
      (node (ref "U3") (pin "5") (pinfunction "OUT_5") (pintype "output"))
    )
    (net (code "265") (name "OUT_VDDO") (class "Default")
      (node (ref "C12") (pin "1") (pinfunction "1_1") (pintype "passive"))
      (node (ref "POWER") (pin "3") (pinfunction "3_3") (pintype "passive"))
      (node (ref "R18") (pin "2") (pinfunction "2_2") (pintype "passive"))
      (node (ref "U6") (pin "5") (pinfunction "OUT_5") (pintype "output"))
    )
    (net (code "266") (name "SERV_FLASH_CIPO") (class "Default")
      (node (ref "FLASH_SERV") (pin "8") (pinfunction "8_8") (pintype "passive"))
      (node (ref "IC7") (pin "18") (pinfunction "B2_18") (pintype "bidirectional"))
    )
    (net (code "267") (name "SERV_FLASH_COPI") (class "Default")
      (node (ref "FLASH_SERV") (pin "10") (pinfunction "10_10") (pintype "passive"))
      (node (ref "IC7") (pin "16") (pinfunction "B4_16") (pintype "bidirectional"))
    )
    (net (code "268") (name "SERV_FLASH_CS") (class "Default")
      (node (ref "FLASH_SERV") (pin "12") (pinfunction "12_12") (pintype "passive"))
      (node (ref "IC7") (pin "17") (pinfunction "B3_17") (pintype "bidirectional"))
    )
    (net (code "269") (name "SERV_FLASH_SCK") (class "Default")
      (node (ref "FLASH_SERV") (pin "6") (pinfunction "6_6") (pintype "passive"))
      (node (ref "IC7") (pin "15") (pinfunction "B5_15") (pintype "bidirectional"))
    )
    (net (code "270") (name "SERV_JTAG_TCK") (class "Default")
      (node (ref "IC10") (pin "16") (pinfunction "B4_16") (pintype "bidirectional"))
      (node (ref "JTAG_SERV") (pin "9") (pinfunction "9_9") (pintype "passive"))
    )
    (net (code "271") (name "SERV_JTAG_TDI") (class "Default")
      (node (ref "IC10") (pin "17") (pinfunction "B3_17") (pintype "bidirectional"))
      (node (ref "JTAG_SERV") (pin "5") (pinfunction "5_5") (pintype "passive"))
    )
    (net (code "272") (name "SERV_JTAG_TDO") (class "Default")
      (node (ref "IC10") (pin "18") (pinfunction "B2_18") (pintype "bidirectional"))
      (node (ref "JTAG_SERV") (pin "13") (pinfunction "13_13") (pintype "passive"))
    )
    (net (code "273") (name "SERV_JTAG_TMS") (class "Default")
      (node (ref "IC10") (pin "15") (pinfunction "B5_15") (pintype "bidirectional"))
      (node (ref "JTAG_SERV") (pin "7") (pinfunction "7_7") (pintype "passive"))
    )
    (net (code "274") (name "SERV_JTAG_TRST") (class "Default")
      (node (ref "IC10") (pin "20") (pinfunction "B1_20") (pintype "bidirectional"))
      (node (ref "JTAG_SERV") (pin "3") (pinfunction "3_3") (pintype "passive"))
    )
    (net (code "275") (name "SERV_LED") (class "Default")
      (node (ref "Q4") (pin "1") (pinfunction "G_1") (pintype "bidirectional"))
      (node (ref "R53") (pin "2") (pinfunction "2_2") (pintype "passive"))
      (node (ref "SERV_LED") (pin "2") (pinfunction "2_2") (pintype "passive"))
    )
    (net (code "276") (name "SERV_LORA_CS") (class "Default")
      (node (ref "IC5") (pin "17") (pinfunction "B3_17") (pintype "bidirectional"))
      (node (ref "LORA_SERV") (pin "P$5") (pinfunction "NSS_P$5") (pintype "bidirectional"))
    )
    (net (code "277") (name "SERV_LORA_MISO") (class "Default")
      (node (ref "IC5") (pin "15") (pinfunction "B5_15") (pintype "bidirectional"))
      (node (ref "LORA_SERV") (pin "P$2") (pinfunction "MISO_P$2") (pintype "bidirectional"))
    )
    (net (code "278") (name "SERV_LORA_MOSI") (class "Default")
      (node (ref "IC5") (pin "16") (pinfunction "B4_16") (pintype "bidirectional"))
      (node (ref "LORA_SERV") (pin "P$3") (pinfunction "MOSI_P$3") (pintype "bidirectional"))
    )
    (net (code "279") (name "SERV_LORA_SCK") (class "Default")
      (node (ref "IC5") (pin "18") (pinfunction "B2_18") (pintype "bidirectional"))
      (node (ref "LORA_SERV") (pin "P$4") (pinfunction "SCK_P$4") (pintype "bidirectional"))
    )
    (net (code "280") (name "SERV_PROG_CS") (class "Default")
      (node (ref "IC8") (pin "17") (pinfunction "B3_17") (pintype "bidirectional"))
      (node (ref "SPI_SERV_1") (pin "4") (pinfunction "4_4") (pintype "passive"))
    )
    (net (code "281") (name "SERV_PROG_MISO") (class "Default")
      (node (ref "IC8") (pin "15") (pinfunction "B5_15") (pintype "bidirectional"))
      (node (ref "SPI_SERV_1") (pin "3") (pinfunction "3_3") (pintype "passive"))
    )
    (net (code "282") (name "SERV_PROG_MOSI") (class "Default")
      (node (ref "IC8") (pin "16") (pinfunction "B4_16") (pintype "bidirectional"))
      (node (ref "SPI_SERV_1") (pin "2") (pinfunction "2_2") (pintype "passive"))
    )
    (net (code "283") (name "SERV_PROG_SCK") (class "Default")
      (node (ref "IC8") (pin "18") (pinfunction "B2_18") (pintype "bidirectional"))
      (node (ref "SPI_SERV_1") (pin "1") (pinfunction "1_1") (pintype "passive"))
    )
    (net (code "284") (name "SERV_UART_RX") (class "Default")
      (node (ref "IC10") (pin "14") (pinfunction "B6_14") (pintype "bidirectional"))
      (node (ref "USB-UART_SERV_1") (pin "2") (pinfunction "2_2") (pintype "passive"))
    )
    (net (code "285") (name "SERV_UART_TX") (class "Default")
      (node (ref "IC10") (pin "13") (pinfunction "B7_13") (pintype "bidirectional"))
      (node (ref "USB-UART_SERV_1") (pin "4") (pinfunction "4_4") (pintype "passive"))
    )
    (net (code "286") (name "SMA_CLK") (class "Default")
      (node (ref "CLOCK") (pin "5") (pinfunction "5_5") (pintype "passive"))
      (node (ref "J4") (pin "5") (pinfunction "5_5") (pintype "bidirectional"))
    )
    (net (code "287") (name "VDD") (class "Default")
      (node (ref "C19") (pin "1") (pinfunction "1_1") (pintype "passive"))
      (node (ref "C20") (pin "1") (pinfunction "1_1") (pintype "passive"))
      (node (ref "POWER") (pin "6") (pinfunction "6_6") (pintype "passive"))
      (node (ref "Q1") (pin "1") (pinfunction "G_1") (pintype "bidirectional"))
      (node (ref "R21") (pin "2") (pinfunction "2_2") (pintype "passive"))
      (node (ref "U$1") (pin "13") (pinfunction "13_13") (pintype "bidirectional"))
      (node (ref "U$2") (pin "13") (pinfunction "13_13") (pintype "bidirectional"))
      (node (ref "U$3") (pin "15") (pinfunction "15_15") (pintype "bidirectional"))
      (node (ref "U$4") (pin "13") (pinfunction "13_13") (pintype "bidirectional"))
    )
    (net (code "288") (name "VDDO") (class "Default")
      (node (ref "C16") (pin "1") (pinfunction "1_1") (pintype "passive"))
      (node (ref "C17") (pin "1") (pinfunction "1_1") (pintype "passive"))
      (node (ref "C30") (pin "1") (pinfunction "1_1") (pintype "passive"))
      (node (ref "C32") (pin "1") (pinfunction "1_1") (pintype "passive"))
      (node (ref "C34") (pin "1") (pinfunction "1_1") (pintype "passive"))
      (node (ref "C35") (pin "1") (pinfunction "1_1") (pintype "passive"))
      (node (ref "C38") (pin "1") (pinfunction "1_1") (pintype "passive"))
      (node (ref "C40") (pin "1") (pinfunction "1_1") (pintype "passive"))
      (node (ref "C42") (pin "1") (pinfunction "1_1") (pintype "passive"))
      (node (ref "C43") (pin "1") (pinfunction "1_1") (pintype "passive"))
      (node (ref "IC10") (pin "10") (pinfunction "OE_10") (pintype "bidirectional"))
      (node (ref "IC10") (pin "2") (pinfunction "VCCA_2") (pintype "bidirectional"))
      (node (ref "IC11") (pin "10") (pinfunction "OE_10") (pintype "bidirectional"))
      (node (ref "IC11") (pin "2") (pinfunction "VCCA_2") (pintype "bidirectional"))
      (node (ref "IC3") (pin "10") (pinfunction "OE_10") (pintype "bidirectional"))
      (node (ref "IC3") (pin "2") (pinfunction "VCCA_2") (pintype "bidirectional"))
      (node (ref "IC4") (pin "10") (pinfunction "OE_10") (pintype "bidirectional"))
      (node (ref "IC4") (pin "2") (pinfunction "VCCA_2") (pintype "bidirectional"))
      (node (ref "IC5") (pin "10") (pinfunction "OE_10") (pintype "bidirectional"))
      (node (ref "IC5") (pin "2") (pinfunction "VCCA_2") (pintype "bidirectional"))
      (node (ref "IC6") (pin "10") (pinfunction "OE_10") (pintype "bidirectional"))
      (node (ref "IC6") (pin "2") (pinfunction "VCCA_2") (pintype "bidirectional"))
      (node (ref "IC7") (pin "10") (pinfunction "OE_10") (pintype "bidirectional"))
      (node (ref "IC7") (pin "2") (pinfunction "VCCA_2") (pintype "bidirectional"))
      (node (ref "IC8") (pin "10") (pinfunction "OE_10") (pintype "bidirectional"))
      (node (ref "IC8") (pin "2") (pinfunction "VCCA_2") (pintype "bidirectional"))
      (node (ref "POWER") (pin "4") (pinfunction "4_4") (pintype "passive"))
      (node (ref "Q19") (pin "1") (pinfunction "G_1") (pintype "bidirectional"))
      (node (ref "R80") (pin "2") (pinfunction "2_2") (pintype "passive"))
      (node (ref "U$1") (pin "27") (pinfunction "27_27") (pintype "bidirectional"))
      (node (ref "U$2") (pin "25") (pinfunction "25_25") (pintype "bidirectional"))
      (node (ref "U$3") (pin "25") (pinfunction "25_25") (pintype "bidirectional"))
      (node (ref "U$4") (pin "27") (pinfunction "27_27") (pintype "bidirectional"))
    )
    (net (code "289") (name "VDD_3V3") (class "Default")
      (node (ref "C21") (pin "1") (pinfunction "1_1") (pintype "passive"))
      (node (ref "C29") (pin "1") (pinfunction "1_1") (pintype "passive"))
      (node (ref "C31") (pin "1") (pinfunction "1_1") (pintype "passive"))
      (node (ref "C36") (pin "1") (pinfunction "1_1") (pintype "passive"))
      (node (ref "C37") (pin "1") (pinfunction "1_1") (pintype "passive"))
      (node (ref "C39") (pin "1") (pinfunction "1_1") (pintype "passive"))
      (node (ref "C41") (pin "1") (pinfunction "1_1") (pintype "passive"))
      (node (ref "C44") (pin "1") (pinfunction "1_1") (pintype "passive"))
      (node (ref "FLASH_OPEN8") (pin "1") (pinfunction "1_1") (pintype "passive"))
      (node (ref "FLASH_OPEN8") (pin "2") (pinfunction "2_2") (pintype "passive"))
      (node (ref "FLASH_SERV") (pin "1") (pinfunction "1_1") (pintype "passive"))
      (node (ref "FLASH_SERV") (pin "2") (pinfunction "2_2") (pintype "passive"))
      (node (ref "IC10") (pin "19") (pinfunction "VCCB_19") (pintype "bidirectional"))
      (node (ref "IC11") (pin "19") (pinfunction "VCCB_19") (pintype "bidirectional"))
      (node (ref "IC3") (pin "19") (pinfunction "VCCB_19") (pintype "bidirectional"))
      (node (ref "IC4") (pin "19") (pinfunction "VCCB_19") (pintype "bidirectional"))
      (node (ref "IC5") (pin "19") (pinfunction "VCCB_19") (pintype "bidirectional"))
      (node (ref "IC6") (pin "19") (pinfunction "VCCB_19") (pintype "bidirectional"))
      (node (ref "IC7") (pin "19") (pinfunction "VCCB_19") (pintype "bidirectional"))
      (node (ref "IC8") (pin "19") (pinfunction "VCCB_19") (pintype "bidirectional"))
      (node (ref "JTAG_OPEN8") (pin "1") (pinfunction "1_1") (pintype "passive"))
      (node (ref "JTAG_OPEN8") (pin "2") (pinfunction "2_2") (pintype "passive"))
      (node (ref "JTAG_SERV") (pin "1") (pinfunction "1_1") (pintype "passive"))
      (node (ref "JTAG_SERV") (pin "2") (pinfunction "2_2") (pintype "passive"))
      (node (ref "LORA_OPEN8") (pin "P$12") (pinfunction "3.3V_P$12") (pintype "bidirectional"))
      (node (ref "LORA_SERV") (pin "P$12") (pinfunction "3.3V_P$12") (pintype "bidirectional"))
      (node (ref "POWER") (pin "2") (pinfunction "2_2") (pintype "passive"))
      (node (ref "Q18") (pin "1") (pinfunction "G_1") (pintype "bidirectional"))
      (node (ref "R20") (pin "2") (pinfunction "2_2") (pintype "passive"))
      (node (ref "R22") (pin "2") (pinfunction "2_2") (pintype "passive"))
      (node (ref "R25") (pin "2") (pinfunction "2_2") (pintype "passive"))
      (node (ref "R29") (pin "2") (pinfunction "2_2") (pintype "passive"))
      (node (ref "R32") (pin "2") (pinfunction "2_2") (pintype "passive"))
      (node (ref "R33") (pin "2") (pinfunction "2_2") (pintype "passive"))
      (node (ref "R34") (pin "1") (pinfunction "1_1") (pintype "passive"))
      (node (ref "R39") (pin "2") (pinfunction "2_2") (pintype "passive"))
      (node (ref "R40") (pin "2") (pinfunction "2_2") (pintype "passive"))
      (node (ref "R41") (pin "2") (pinfunction "2_2") (pintype "passive"))
      (node (ref "R52") (pin "2") (pinfunction "2_2") (pintype "passive"))
      (node (ref "R54") (pin "2") (pinfunction "2_2") (pintype "passive"))
      (node (ref "R55") (pin "2") (pinfunction "2_2") (pintype "passive"))
      (node (ref "R56") (pin "2") (pinfunction "2_2") (pintype "passive"))
      (node (ref "R62") (pin "2") (pinfunction "2_2") (pintype "passive"))
      (node (ref "R64") (pin "2") (pinfunction "2_2") (pintype "passive"))
      (node (ref "R77") (pin "2") (pinfunction "2_2") (pintype "passive"))
      (node (ref "R78") (pin "2") (pinfunction "2_2") (pintype "passive"))
      (node (ref "R79") (pin "2") (pinfunction "2_2") (pintype "passive"))
      (node (ref "USB-UART_OPEN8_1") (pin "3") (pinfunction "3_3") (pintype "passive"))
      (node (ref "USB-UART_SERV_1") (pin "3") (pinfunction "3_3") (pintype "passive"))
    )
    (net (code "290") (name "VDD_5V") (class "Default")
      (node (ref "IN_3V3") (pin "1") (pinfunction "1_1") (pintype "passive"))
      (node (ref "IN_OPEN8") (pin "1") (pinfunction "1_1") (pintype "passive"))
      (node (ref "IN_RAM") (pin "1") (pinfunction "1_1") (pintype "passive"))
      (node (ref "IN_SERV") (pin "1") (pinfunction "1_1") (pintype "passive"))
      (node (ref "IN_VDD") (pin "1") (pinfunction "1_1") (pintype "passive"))
      (node (ref "IN_VDDO") (pin "1") (pinfunction "1_1") (pintype "passive"))
      (node (ref "Q5") (pin "1") (pinfunction "G_1") (pintype "bidirectional"))
      (node (ref "R57") (pin "2") (pinfunction "2_2") (pintype "passive"))
      (node (ref "USB-UART_OPEN8_2") (pin "2") (pinfunction "2_2") (pintype "passive"))
      (node (ref "USB-UART_SERV_2") (pin "2") (pinfunction "2_2") (pintype "passive"))
    )
    (net (code "291") (name "unconnected-(FLASH_OPEN8-Pad5)") (class "Default")
      (node (ref "FLASH_OPEN8") (pin "5") (pinfunction "5_5") (pintype "passive"))
    )
    (net (code "292") (name "unconnected-(FLASH_OPEN8-Pad7)") (class "Default")
      (node (ref "FLASH_OPEN8") (pin "7") (pinfunction "7_7") (pintype "passive"))
    )
    (net (code "293") (name "unconnected-(FLASH_OPEN8-Pad9)") (class "Default")
      (node (ref "FLASH_OPEN8") (pin "9") (pinfunction "9_9") (pintype "passive"))
    )
    (net (code "294") (name "unconnected-(FLASH_OPEN8-Pad11)") (class "Default")
      (node (ref "FLASH_OPEN8") (pin "11") (pinfunction "11_11") (pintype "passive"))
    )
    (net (code "295") (name "unconnected-(FLASH_SERV-Pad5)") (class "Default")
      (node (ref "FLASH_SERV") (pin "5") (pinfunction "5_5") (pintype "passive"))
    )
    (net (code "296") (name "unconnected-(FLASH_SERV-Pad7)") (class "Default")
      (node (ref "FLASH_SERV") (pin "7") (pinfunction "7_7") (pintype "passive"))
    )
    (net (code "297") (name "unconnected-(FLASH_SERV-Pad9)") (class "Default")
      (node (ref "FLASH_SERV") (pin "9") (pinfunction "9_9") (pintype "passive"))
    )
    (net (code "298") (name "unconnected-(FLASH_SERV-Pad11)") (class "Default")
      (node (ref "FLASH_SERV") (pin "11") (pinfunction "11_11") (pintype "passive"))
    )
    (net (code "299") (name "unconnected-(IC1-N.C.-Pad1)") (class "Default")
      (node (ref "IC1") (pin "1") (pinfunction "N.C._1") (pintype "no_connect"))
    )
    (net (code "300") (name "unconnected-(IC2-N.C.-Pad1)") (class "Default")
      (node (ref "IC2") (pin "1") (pinfunction "N.C._1") (pintype "no_connect"))
    )
    (net (code "301") (name "unconnected-(IC3-A1-Pad1)") (class "Default")
      (node (ref "IC3") (pin "1") (pinfunction "A1_1") (pintype "bidirectional"))
    )
    (net (code "302") (name "unconnected-(IC3-A6-Pad7)") (class "Default")
      (node (ref "IC3") (pin "7") (pinfunction "A6_7") (pintype "bidirectional"))
    )
    (net (code "303") (name "unconnected-(IC3-A7-Pad8)") (class "Default")
      (node (ref "IC3") (pin "8") (pinfunction "A7_8") (pintype "bidirectional"))
    )
    (net (code "304") (name "unconnected-(IC3-A8-Pad9)") (class "Default")
      (node (ref "IC3") (pin "9") (pinfunction "A8_9") (pintype "bidirectional"))
    )
    (net (code "305") (name "unconnected-(IC3-B1-Pad20)") (class "Default")
      (node (ref "IC3") (pin "20") (pinfunction "B1_20") (pintype "bidirectional"))
    )
    (net (code "306") (name "unconnected-(IC3-B6-Pad14)") (class "Default")
      (node (ref "IC3") (pin "14") (pinfunction "B6_14") (pintype "bidirectional"))
    )
    (net (code "307") (name "unconnected-(IC3-B7-Pad13)") (class "Default")
      (node (ref "IC3") (pin "13") (pinfunction "B7_13") (pintype "bidirectional"))
    )
    (net (code "308") (name "unconnected-(IC3-B8-Pad12)") (class "Default")
      (node (ref "IC3") (pin "12") (pinfunction "B8_12") (pintype "bidirectional"))
    )
    (net (code "309") (name "unconnected-(IC4-A1-Pad1)") (class "Default")
      (node (ref "IC4") (pin "1") (pinfunction "A1_1") (pintype "bidirectional"))
    )
    (net (code "310") (name "unconnected-(IC4-A6-Pad7)") (class "Default")
      (node (ref "IC4") (pin "7") (pinfunction "A6_7") (pintype "bidirectional"))
    )
    (net (code "311") (name "unconnected-(IC4-A7-Pad8)") (class "Default")
      (node (ref "IC4") (pin "8") (pinfunction "A7_8") (pintype "bidirectional"))
    )
    (net (code "312") (name "unconnected-(IC4-A8-Pad9)") (class "Default")
      (node (ref "IC4") (pin "9") (pinfunction "A8_9") (pintype "bidirectional"))
    )
    (net (code "313") (name "unconnected-(IC4-B1-Pad20)") (class "Default")
      (node (ref "IC4") (pin "20") (pinfunction "B1_20") (pintype "bidirectional"))
    )
    (net (code "314") (name "unconnected-(IC4-B6-Pad14)") (class "Default")
      (node (ref "IC4") (pin "14") (pinfunction "B6_14") (pintype "bidirectional"))
    )
    (net (code "315") (name "unconnected-(IC4-B7-Pad13)") (class "Default")
      (node (ref "IC4") (pin "13") (pinfunction "B7_13") (pintype "bidirectional"))
    )
    (net (code "316") (name "unconnected-(IC4-B8-Pad12)") (class "Default")
      (node (ref "IC4") (pin "12") (pinfunction "B8_12") (pintype "bidirectional"))
    )
    (net (code "317") (name "unconnected-(IC5-A1-Pad1)") (class "Default")
      (node (ref "IC5") (pin "1") (pinfunction "A1_1") (pintype "bidirectional"))
    )
    (net (code "318") (name "unconnected-(IC5-A6-Pad7)") (class "Default")
      (node (ref "IC5") (pin "7") (pinfunction "A6_7") (pintype "bidirectional"))
    )
    (net (code "319") (name "unconnected-(IC5-A7-Pad8)") (class "Default")
      (node (ref "IC5") (pin "8") (pinfunction "A7_8") (pintype "bidirectional"))
    )
    (net (code "320") (name "unconnected-(IC5-A8-Pad9)") (class "Default")
      (node (ref "IC5") (pin "9") (pinfunction "A8_9") (pintype "bidirectional"))
    )
    (net (code "321") (name "unconnected-(IC5-B1-Pad20)") (class "Default")
      (node (ref "IC5") (pin "20") (pinfunction "B1_20") (pintype "bidirectional"))
    )
    (net (code "322") (name "unconnected-(IC5-B6-Pad14)") (class "Default")
      (node (ref "IC5") (pin "14") (pinfunction "B6_14") (pintype "bidirectional"))
    )
    (net (code "323") (name "unconnected-(IC5-B7-Pad13)") (class "Default")
      (node (ref "IC5") (pin "13") (pinfunction "B7_13") (pintype "bidirectional"))
    )
    (net (code "324") (name "unconnected-(IC5-B8-Pad12)") (class "Default")
      (node (ref "IC5") (pin "12") (pinfunction "B8_12") (pintype "bidirectional"))
    )
    (net (code "325") (name "unconnected-(IC6-A8-Pad9)") (class "Default")
      (node (ref "IC6") (pin "9") (pinfunction "A8_9") (pintype "bidirectional"))
    )
    (net (code "326") (name "unconnected-(IC6-B8-Pad12)") (class "Default")
      (node (ref "IC6") (pin "12") (pinfunction "B8_12") (pintype "bidirectional"))
    )
    (net (code "327") (name "unconnected-(IC7-A1-Pad1)") (class "Default")
      (node (ref "IC7") (pin "1") (pinfunction "A1_1") (pintype "bidirectional"))
    )
    (net (code "328") (name "unconnected-(IC7-A6-Pad7)") (class "Default")
      (node (ref "IC7") (pin "7") (pinfunction "A6_7") (pintype "bidirectional"))
    )
    (net (code "329") (name "unconnected-(IC7-A7-Pad8)") (class "Default")
      (node (ref "IC7") (pin "8") (pinfunction "A7_8") (pintype "bidirectional"))
    )
    (net (code "330") (name "unconnected-(IC7-A8-Pad9)") (class "Default")
      (node (ref "IC7") (pin "9") (pinfunction "A8_9") (pintype "bidirectional"))
    )
    (net (code "331") (name "unconnected-(IC7-B1-Pad20)") (class "Default")
      (node (ref "IC7") (pin "20") (pinfunction "B1_20") (pintype "bidirectional"))
    )
    (net (code "332") (name "unconnected-(IC7-B6-Pad14)") (class "Default")
      (node (ref "IC7") (pin "14") (pinfunction "B6_14") (pintype "bidirectional"))
    )
    (net (code "333") (name "unconnected-(IC7-B7-Pad13)") (class "Default")
      (node (ref "IC7") (pin "13") (pinfunction "B7_13") (pintype "bidirectional"))
    )
    (net (code "334") (name "unconnected-(IC7-B8-Pad12)") (class "Default")
      (node (ref "IC7") (pin "12") (pinfunction "B8_12") (pintype "bidirectional"))
    )
    (net (code "335") (name "unconnected-(IC8-A1-Pad1)") (class "Default")
      (node (ref "IC8") (pin "1") (pinfunction "A1_1") (pintype "bidirectional"))
    )
    (net (code "336") (name "unconnected-(IC8-A6-Pad7)") (class "Default")
      (node (ref "IC8") (pin "7") (pinfunction "A6_7") (pintype "bidirectional"))
    )
    (net (code "337") (name "unconnected-(IC8-A7-Pad8)") (class "Default")
      (node (ref "IC8") (pin "8") (pinfunction "A7_8") (pintype "bidirectional"))
    )
    (net (code "338") (name "unconnected-(IC8-A8-Pad9)") (class "Default")
      (node (ref "IC8") (pin "9") (pinfunction "A8_9") (pintype "bidirectional"))
    )
    (net (code "339") (name "unconnected-(IC8-B1-Pad20)") (class "Default")
      (node (ref "IC8") (pin "20") (pinfunction "B1_20") (pintype "bidirectional"))
    )
    (net (code "340") (name "unconnected-(IC8-B6-Pad14)") (class "Default")
      (node (ref "IC8") (pin "14") (pinfunction "B6_14") (pintype "bidirectional"))
    )
    (net (code "341") (name "unconnected-(IC8-B7-Pad13)") (class "Default")
      (node (ref "IC8") (pin "13") (pinfunction "B7_13") (pintype "bidirectional"))
    )
    (net (code "342") (name "unconnected-(IC8-B8-Pad12)") (class "Default")
      (node (ref "IC8") (pin "12") (pinfunction "B8_12") (pintype "bidirectional"))
    )
    (net (code "343") (name "unconnected-(IC10-A8-Pad9)") (class "Default")
      (node (ref "IC10") (pin "9") (pinfunction "A8_9") (pintype "bidirectional"))
    )
    (net (code "344") (name "unconnected-(IC10-B8-Pad12)") (class "Default")
      (node (ref "IC10") (pin "12") (pinfunction "B8_12") (pintype "bidirectional"))
    )
    (net (code "345") (name "unconnected-(IC11-A1-Pad1)") (class "Default")
      (node (ref "IC11") (pin "1") (pinfunction "A1_1") (pintype "bidirectional"))
    )
    (net (code "346") (name "unconnected-(IC11-A2-Pad3)") (class "Default")
      (node (ref "IC11") (pin "3") (pinfunction "A2_3") (pintype "bidirectional"))
    )
    (net (code "347") (name "unconnected-(IC11-A7-Pad8)") (class "Default")
      (node (ref "IC11") (pin "8") (pinfunction "A7_8") (pintype "bidirectional"))
    )
    (net (code "348") (name "unconnected-(IC11-A8-Pad9)") (class "Default")
      (node (ref "IC11") (pin "9") (pinfunction "A8_9") (pintype "bidirectional"))
    )
    (net (code "349") (name "unconnected-(IC11-B1-Pad20)") (class "Default")
      (node (ref "IC11") (pin "20") (pinfunction "B1_20") (pintype "bidirectional"))
    )
    (net (code "350") (name "unconnected-(IC11-B2-Pad18)") (class "Default")
      (node (ref "IC11") (pin "18") (pinfunction "B2_18") (pintype "bidirectional"))
    )
    (net (code "351") (name "unconnected-(IC11-B7-Pad13)") (class "Default")
      (node (ref "IC11") (pin "13") (pinfunction "B7_13") (pintype "bidirectional"))
    )
    (net (code "352") (name "unconnected-(IC11-B8-Pad12)") (class "Default")
      (node (ref "IC11") (pin "12") (pinfunction "B8_12") (pintype "bidirectional"))
    )
    (net (code "353") (name "unconnected-(JTAG_OPEN8-Pad11)") (class "Default")
      (node (ref "JTAG_OPEN8") (pin "11") (pinfunction "11_11") (pintype "passive"))
    )
    (net (code "354") (name "unconnected-(JTAG_OPEN8-Pad15)") (class "Default")
      (node (ref "JTAG_OPEN8") (pin "15") (pinfunction "15_15") (pintype "passive"))
    )
    (net (code "355") (name "unconnected-(JTAG_OPEN8-Pad17)") (class "Default")
      (node (ref "JTAG_OPEN8") (pin "17") (pinfunction "17_17") (pintype "passive"))
    )
    (net (code "356") (name "unconnected-(JTAG_OPEN8-Pad19)") (class "Default")
      (node (ref "JTAG_OPEN8") (pin "19") (pinfunction "19_19") (pintype "passive"))
    )
    (net (code "357") (name "unconnected-(JTAG_SERV-Pad11)") (class "Default")
      (node (ref "JTAG_SERV") (pin "11") (pinfunction "11_11") (pintype "passive"))
    )
    (net (code "358") (name "unconnected-(JTAG_SERV-Pad15)") (class "Default")
      (node (ref "JTAG_SERV") (pin "15") (pinfunction "15_15") (pintype "passive"))
    )
    (net (code "359") (name "unconnected-(JTAG_SERV-Pad17)") (class "Default")
      (node (ref "JTAG_SERV") (pin "17") (pinfunction "17_17") (pintype "passive"))
    )
    (net (code "360") (name "unconnected-(JTAG_SERV-Pad19)") (class "Default")
      (node (ref "JTAG_SERV") (pin "19") (pinfunction "19_19") (pintype "passive"))
    )
    (net (code "361") (name "unconnected-(LORA_OPEN8-ANT-PadP$16)") (class "Default")
      (node (ref "LORA_OPEN8") (pin "P$16") (pinfunction "ANT_P$16") (pintype "bidirectional"))
    )
    (net (code "362") (name "unconnected-(LORA_OPEN8-DIO0-PadP$11)") (class "Default")
      (node (ref "LORA_OPEN8") (pin "P$11") (pinfunction "DIO0_P$11") (pintype "bidirectional"))
    )
    (net (code "363") (name "unconnected-(LORA_OPEN8-DIO1-PadP$10)") (class "Default")
      (node (ref "LORA_OPEN8") (pin "P$10") (pinfunction "DIO1_P$10") (pintype "bidirectional"))
    )
    (net (code "364") (name "unconnected-(LORA_OPEN8-DIO2-PadP$9)") (class "Default")
      (node (ref "LORA_OPEN8") (pin "P$9") (pinfunction "DIO2_P$9") (pintype "bidirectional"))
    )
    (net (code "365") (name "unconnected-(LORA_OPEN8-DIO3-PadP$14)") (class "Default")
      (node (ref "LORA_OPEN8") (pin "P$14") (pinfunction "DIO3_P$14") (pintype "bidirectional"))
    )
    (net (code "366") (name "unconnected-(LORA_OPEN8-DIO4-PadP$13)") (class "Default")
      (node (ref "LORA_OPEN8") (pin "P$13") (pinfunction "DIO4_P$13") (pintype "bidirectional"))
    )
    (net (code "367") (name "unconnected-(LORA_OPEN8-DIO5-PadP$7)") (class "Default")
      (node (ref "LORA_OPEN8") (pin "P$7") (pinfunction "DIO5_P$7") (pintype "bidirectional"))
    )
    (net (code "368") (name "unconnected-(LORA_OPEN8-RESET-PadP$6)") (class "Default")
      (node (ref "LORA_OPEN8") (pin "P$6") (pinfunction "RESET_P$6") (pintype "bidirectional"))
    )
    (net (code "369") (name "unconnected-(LORA_SERV-ANT-PadP$16)") (class "Default")
      (node (ref "LORA_SERV") (pin "P$16") (pinfunction "ANT_P$16") (pintype "bidirectional"))
    )
    (net (code "370") (name "unconnected-(LORA_SERV-DIO0-PadP$11)") (class "Default")
      (node (ref "LORA_SERV") (pin "P$11") (pinfunction "DIO0_P$11") (pintype "bidirectional"))
    )
    (net (code "371") (name "unconnected-(LORA_SERV-DIO1-PadP$10)") (class "Default")
      (node (ref "LORA_SERV") (pin "P$10") (pinfunction "DIO1_P$10") (pintype "bidirectional"))
    )
    (net (code "372") (name "unconnected-(LORA_SERV-DIO2-PadP$9)") (class "Default")
      (node (ref "LORA_SERV") (pin "P$9") (pinfunction "DIO2_P$9") (pintype "bidirectional"))
    )
    (net (code "373") (name "unconnected-(LORA_SERV-DIO3-PadP$14)") (class "Default")
      (node (ref "LORA_SERV") (pin "P$14") (pinfunction "DIO3_P$14") (pintype "bidirectional"))
    )
    (net (code "374") (name "unconnected-(LORA_SERV-DIO4-PadP$13)") (class "Default")
      (node (ref "LORA_SERV") (pin "P$13") (pinfunction "DIO4_P$13") (pintype "bidirectional"))
    )
    (net (code "375") (name "unconnected-(LORA_SERV-DIO5-PadP$7)") (class "Default")
      (node (ref "LORA_SERV") (pin "P$7") (pinfunction "DIO5_P$7") (pintype "bidirectional"))
    )
    (net (code "376") (name "unconnected-(LORA_SERV-RESET-PadP$6)") (class "Default")
      (node (ref "LORA_SERV") (pin "P$6") (pinfunction "RESET_P$6") (pintype "bidirectional"))
    )
    (net (code "377") (name "unconnected-(SPI_OPEN8_1-Pad1)") (class "Default")
      (node (ref "SPI_OPEN8_1") (pin "1") (pinfunction "1_1") (pintype "passive"))
    )
    (net (code "378") (name "unconnected-(SPI_OPEN8_1-Pad2)") (class "Default")
      (node (ref "SPI_OPEN8_1") (pin "2") (pinfunction "2_2") (pintype "passive"))
    )
    (net (code "379") (name "unconnected-(SPI_OPEN8_1-Pad3)") (class "Default")
      (node (ref "SPI_OPEN8_1") (pin "3") (pinfunction "3_3") (pintype "passive"))
    )
    (net (code "380") (name "unconnected-(SPI_OPEN8_1-Pad4)") (class "Default")
      (node (ref "SPI_OPEN8_1") (pin "4") (pinfunction "4_4") (pintype "passive"))
    )
    (net (code "381") (name "unconnected-(SPI_OPEN8_1-Pad5)") (class "Default")
      (node (ref "SPI_OPEN8_1") (pin "5") (pinfunction "5_5") (pintype "passive"))
    )
    (net (code "382") (name "unconnected-(SPI_OPEN8_1-Pad6)") (class "Default")
      (node (ref "SPI_OPEN8_1") (pin "6") (pinfunction "6_6") (pintype "passive"))
    )
    (net (code "383") (name "unconnected-(SPI_OPEN8_1-Pad7)") (class "Default")
      (node (ref "SPI_OPEN8_1") (pin "7") (pinfunction "7_7") (pintype "passive"))
    )
    (net (code "384") (name "unconnected-(SPI_OPEN8_1-Pad8)") (class "Default")
      (node (ref "SPI_OPEN8_1") (pin "8") (pinfunction "8_8") (pintype "passive"))
    )
    (net (code "385") (name "unconnected-(SPI_OPEN8_1-Pad9)") (class "Default")
      (node (ref "SPI_OPEN8_1") (pin "9") (pinfunction "9_9") (pintype "passive"))
    )
    (net (code "386") (name "unconnected-(SPI_OPEN8_1-Pad10)") (class "Default")
      (node (ref "SPI_OPEN8_1") (pin "10") (pinfunction "10_10") (pintype "passive"))
    )
    (net (code "387") (name "unconnected-(SPI_OPEN8_2-Pad5)") (class "Default")
      (node (ref "SPI_OPEN8_2") (pin "5") (pinfunction "5_5") (pintype "passive"))
    )
    (net (code "388") (name "unconnected-(SPI_OPEN8_2-Pad6)") (class "Default")
      (node (ref "SPI_OPEN8_2") (pin "6") (pinfunction "6_6") (pintype "passive"))
    )
    (net (code "389") (name "unconnected-(SPI_OPEN8_2-Pad7)") (class "Default")
      (node (ref "SPI_OPEN8_2") (pin "7") (pinfunction "7_7") (pintype "passive"))
    )
    (net (code "390") (name "unconnected-(SPI_OPEN8_2-Pad8)") (class "Default")
      (node (ref "SPI_OPEN8_2") (pin "8") (pinfunction "8_8") (pintype "passive"))
    )
    (net (code "391") (name "unconnected-(SPI_OPEN8_2-Pad9)") (class "Default")
      (node (ref "SPI_OPEN8_2") (pin "9") (pinfunction "9_9") (pintype "passive"))
    )
    (net (code "392") (name "unconnected-(SPI_SERV_1-Pad5)") (class "Default")
      (node (ref "SPI_SERV_1") (pin "5") (pinfunction "5_5") (pintype "passive"))
    )
    (net (code "393") (name "unconnected-(SPI_SERV_1-Pad6)") (class "Default")
      (node (ref "SPI_SERV_1") (pin "6") (pinfunction "6_6") (pintype "passive"))
    )
    (net (code "394") (name "unconnected-(SPI_SERV_1-Pad7)") (class "Default")
      (node (ref "SPI_SERV_1") (pin "7") (pinfunction "7_7") (pintype "passive"))
    )
    (net (code "395") (name "unconnected-(SPI_SERV_1-Pad8)") (class "Default")
      (node (ref "SPI_SERV_1") (pin "8") (pinfunction "8_8") (pintype "passive"))
    )
    (net (code "396") (name "unconnected-(SPI_SERV_1-Pad9)") (class "Default")
      (node (ref "SPI_SERV_1") (pin "9") (pinfunction "9_9") (pintype "passive"))
    )
    (net (code "397") (name "unconnected-(SPI_SERV_2-Pad1)") (class "Default")
      (node (ref "SPI_SERV_2") (pin "1") (pinfunction "1_1") (pintype "passive"))
    )
    (net (code "398") (name "unconnected-(SPI_SERV_2-Pad2)") (class "Default")
      (node (ref "SPI_SERV_2") (pin "2") (pinfunction "2_2") (pintype "passive"))
    )
    (net (code "399") (name "unconnected-(SPI_SERV_2-Pad3)") (class "Default")
      (node (ref "SPI_SERV_2") (pin "3") (pinfunction "3_3") (pintype "passive"))
    )
    (net (code "400") (name "unconnected-(SPI_SERV_2-Pad4)") (class "Default")
      (node (ref "SPI_SERV_2") (pin "4") (pinfunction "4_4") (pintype "passive"))
    )
    (net (code "401") (name "unconnected-(SPI_SERV_2-Pad5)") (class "Default")
      (node (ref "SPI_SERV_2") (pin "5") (pinfunction "5_5") (pintype "passive"))
    )
    (net (code "402") (name "unconnected-(SPI_SERV_2-Pad6)") (class "Default")
      (node (ref "SPI_SERV_2") (pin "6") (pinfunction "6_6") (pintype "passive"))
    )
    (net (code "403") (name "unconnected-(SPI_SERV_2-Pad7)") (class "Default")
      (node (ref "SPI_SERV_2") (pin "7") (pinfunction "7_7") (pintype "passive"))
    )
    (net (code "404") (name "unconnected-(SPI_SERV_2-Pad8)") (class "Default")
      (node (ref "SPI_SERV_2") (pin "8") (pinfunction "8_8") (pintype "passive"))
    )
    (net (code "405") (name "unconnected-(SPI_SERV_2-Pad9)") (class "Default")
      (node (ref "SPI_SERV_2") (pin "9") (pinfunction "9_9") (pintype "passive"))
    )
    (net (code "406") (name "unconnected-(SPI_SERV_2-Pad10)") (class "Default")
      (node (ref "SPI_SERV_2") (pin "10") (pinfunction "10_10") (pintype "passive"))
    )
    (net (code "407") (name "unconnected-(U$1-Pad2)") (class "Default")
      (node (ref "U$1") (pin "2") (pinfunction "2_2") (pintype "bidirectional"))
    )
    (net (code "408") (name "unconnected-(U$1-Pad41)") (class "Default")
      (node (ref "U$1") (pin "41") (pinfunction "41_41") (pintype "bidirectional"))
    )
    (net (code "409") (name "unconnected-(U$2-Pad2)") (class "Default")
      (node (ref "U$2") (pin "2") (pinfunction "2_2") (pintype "bidirectional"))
    )
    (net (code "410") (name "unconnected-(U$2-Pad41)") (class "Default")
      (node (ref "U$2") (pin "41") (pinfunction "41_41") (pintype "bidirectional"))
    )
    (net (code "411") (name "unconnected-(U$3-Pad2)") (class "Default")
      (node (ref "U$3") (pin "2") (pinfunction "2_2") (pintype "bidirectional"))
    )
    (net (code "412") (name "unconnected-(U$3-Pad41)") (class "Default")
      (node (ref "U$3") (pin "41") (pinfunction "41_41") (pintype "bidirectional"))
    )
    (net (code "413") (name "unconnected-(U$4-Pad2)") (class "Default")
      (node (ref "U$4") (pin "2") (pinfunction "2_2") (pintype "bidirectional"))
    )
    (net (code "414") (name "unconnected-(U$4-Pad41)") (class "Default")
      (node (ref "U$4") (pin "41") (pinfunction "41_41") (pintype "bidirectional"))
    )
    (net (code "415") (name "unconnected-(USB-UART_OPEN8_2-Pad1)") (class "Default")
      (node (ref "USB-UART_OPEN8_2") (pin "1") (pinfunction "1_1") (pintype "passive"))
    )
    (net (code "416") (name "unconnected-(USB-UART_OPEN8_2-Pad3)") (class "Default")
      (node (ref "USB-UART_OPEN8_2") (pin "3") (pinfunction "3_3") (pintype "passive"))
    )
    (net (code "417") (name "unconnected-(USB-UART_OPEN8_2-Pad4)") (class "Default")
      (node (ref "USB-UART_OPEN8_2") (pin "4") (pinfunction "4_4") (pintype "passive"))
    )
    (net (code "418") (name "unconnected-(USB-UART_SERV_2-Pad1)") (class "Default")
      (node (ref "USB-UART_SERV_2") (pin "1") (pinfunction "1_1") (pintype "passive"))
    )
    (net (code "419") (name "unconnected-(USB-UART_SERV_2-Pad3)") (class "Default")
      (node (ref "USB-UART_SERV_2") (pin "3") (pinfunction "3_3") (pintype "passive"))
    )
    (net (code "420") (name "unconnected-(USB-UART_SERV_2-Pad4)") (class "Default")
      (node (ref "USB-UART_SERV_2") (pin "4") (pinfunction "4_4") (pintype "passive"))
    )
  )
)
